# 16REG_2a.net
KiCad netlist of a schematic drawn in EAGLE
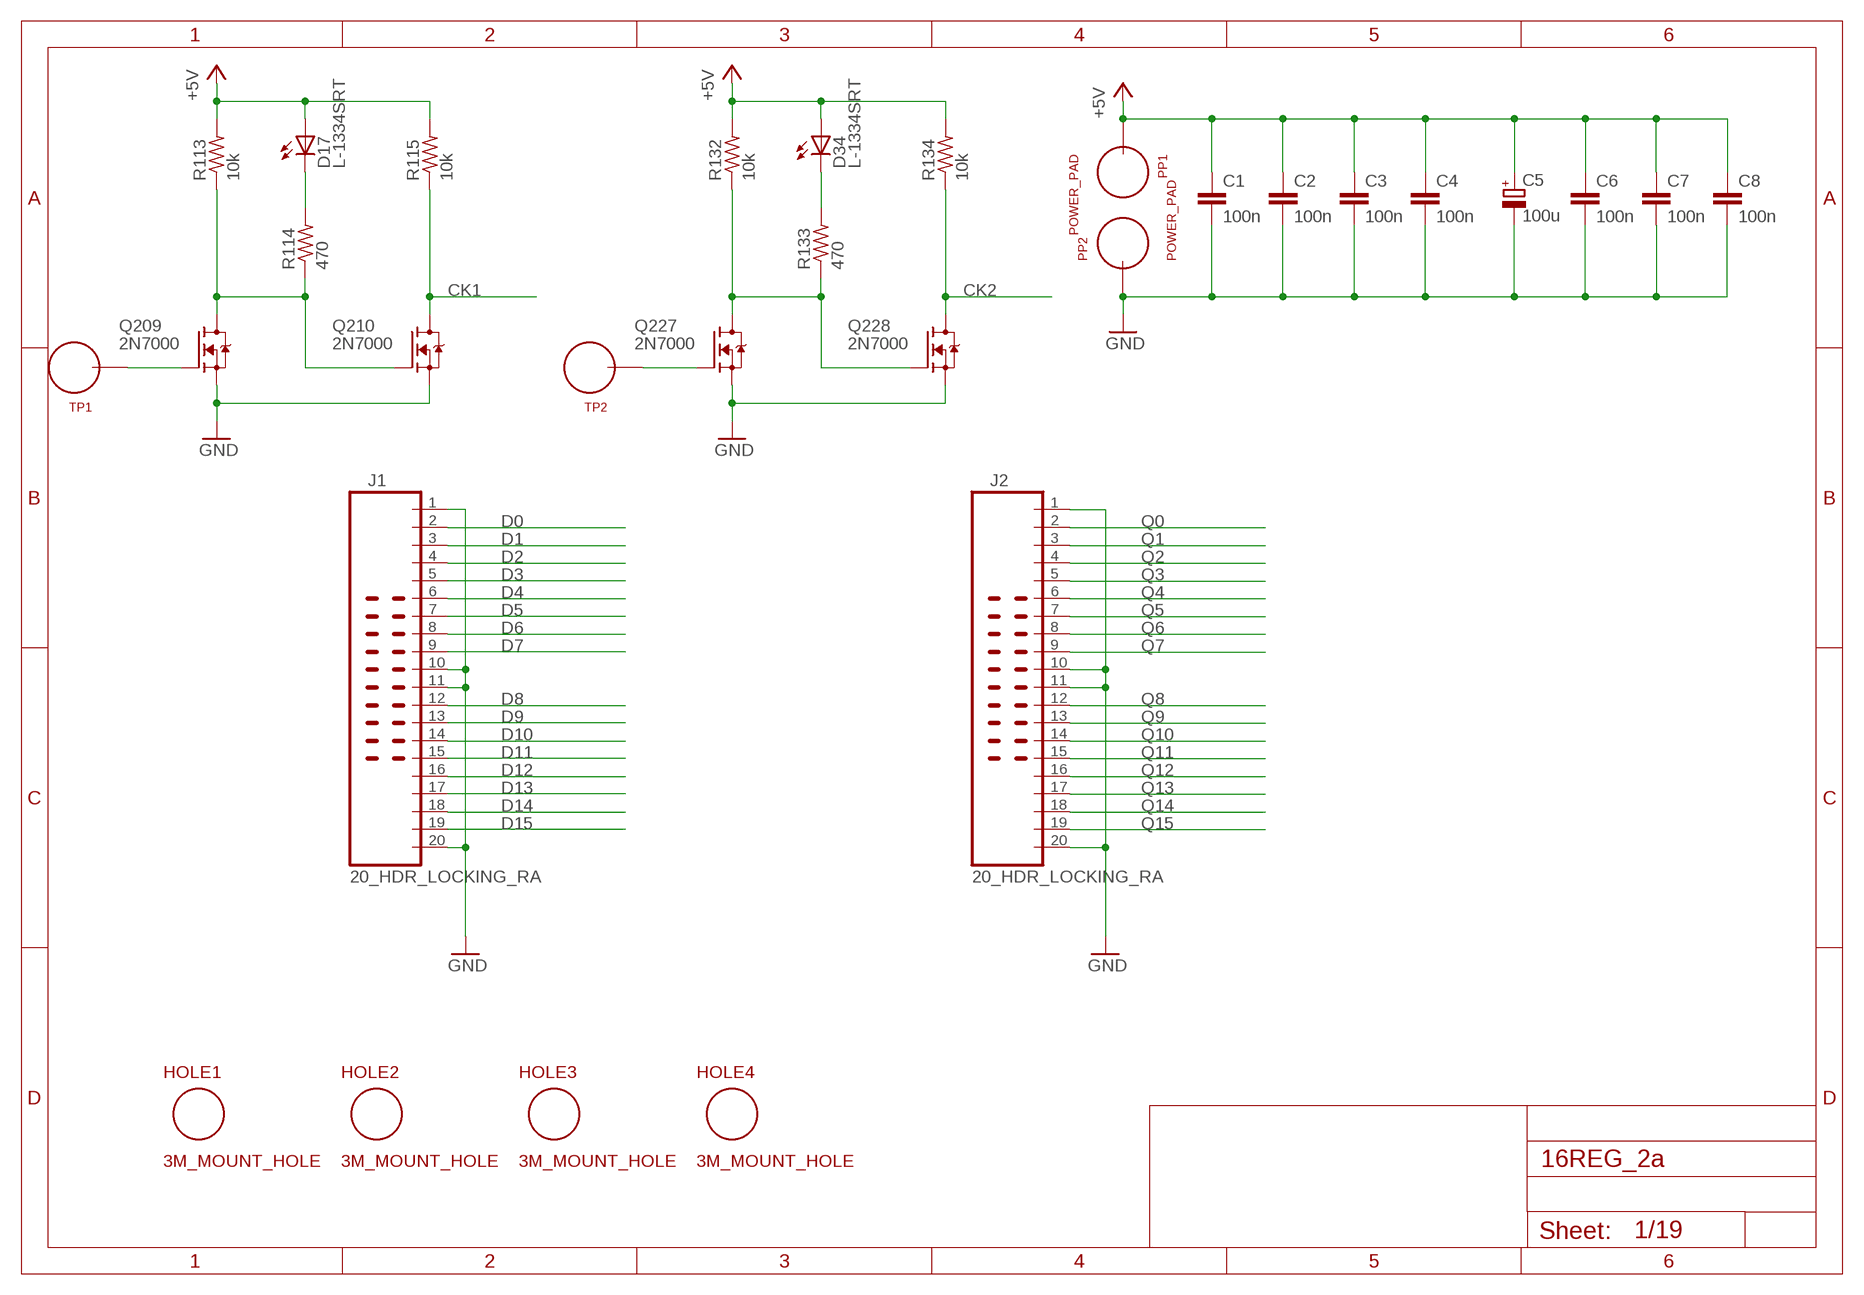
[diagram p0: schematic, sheet 1]
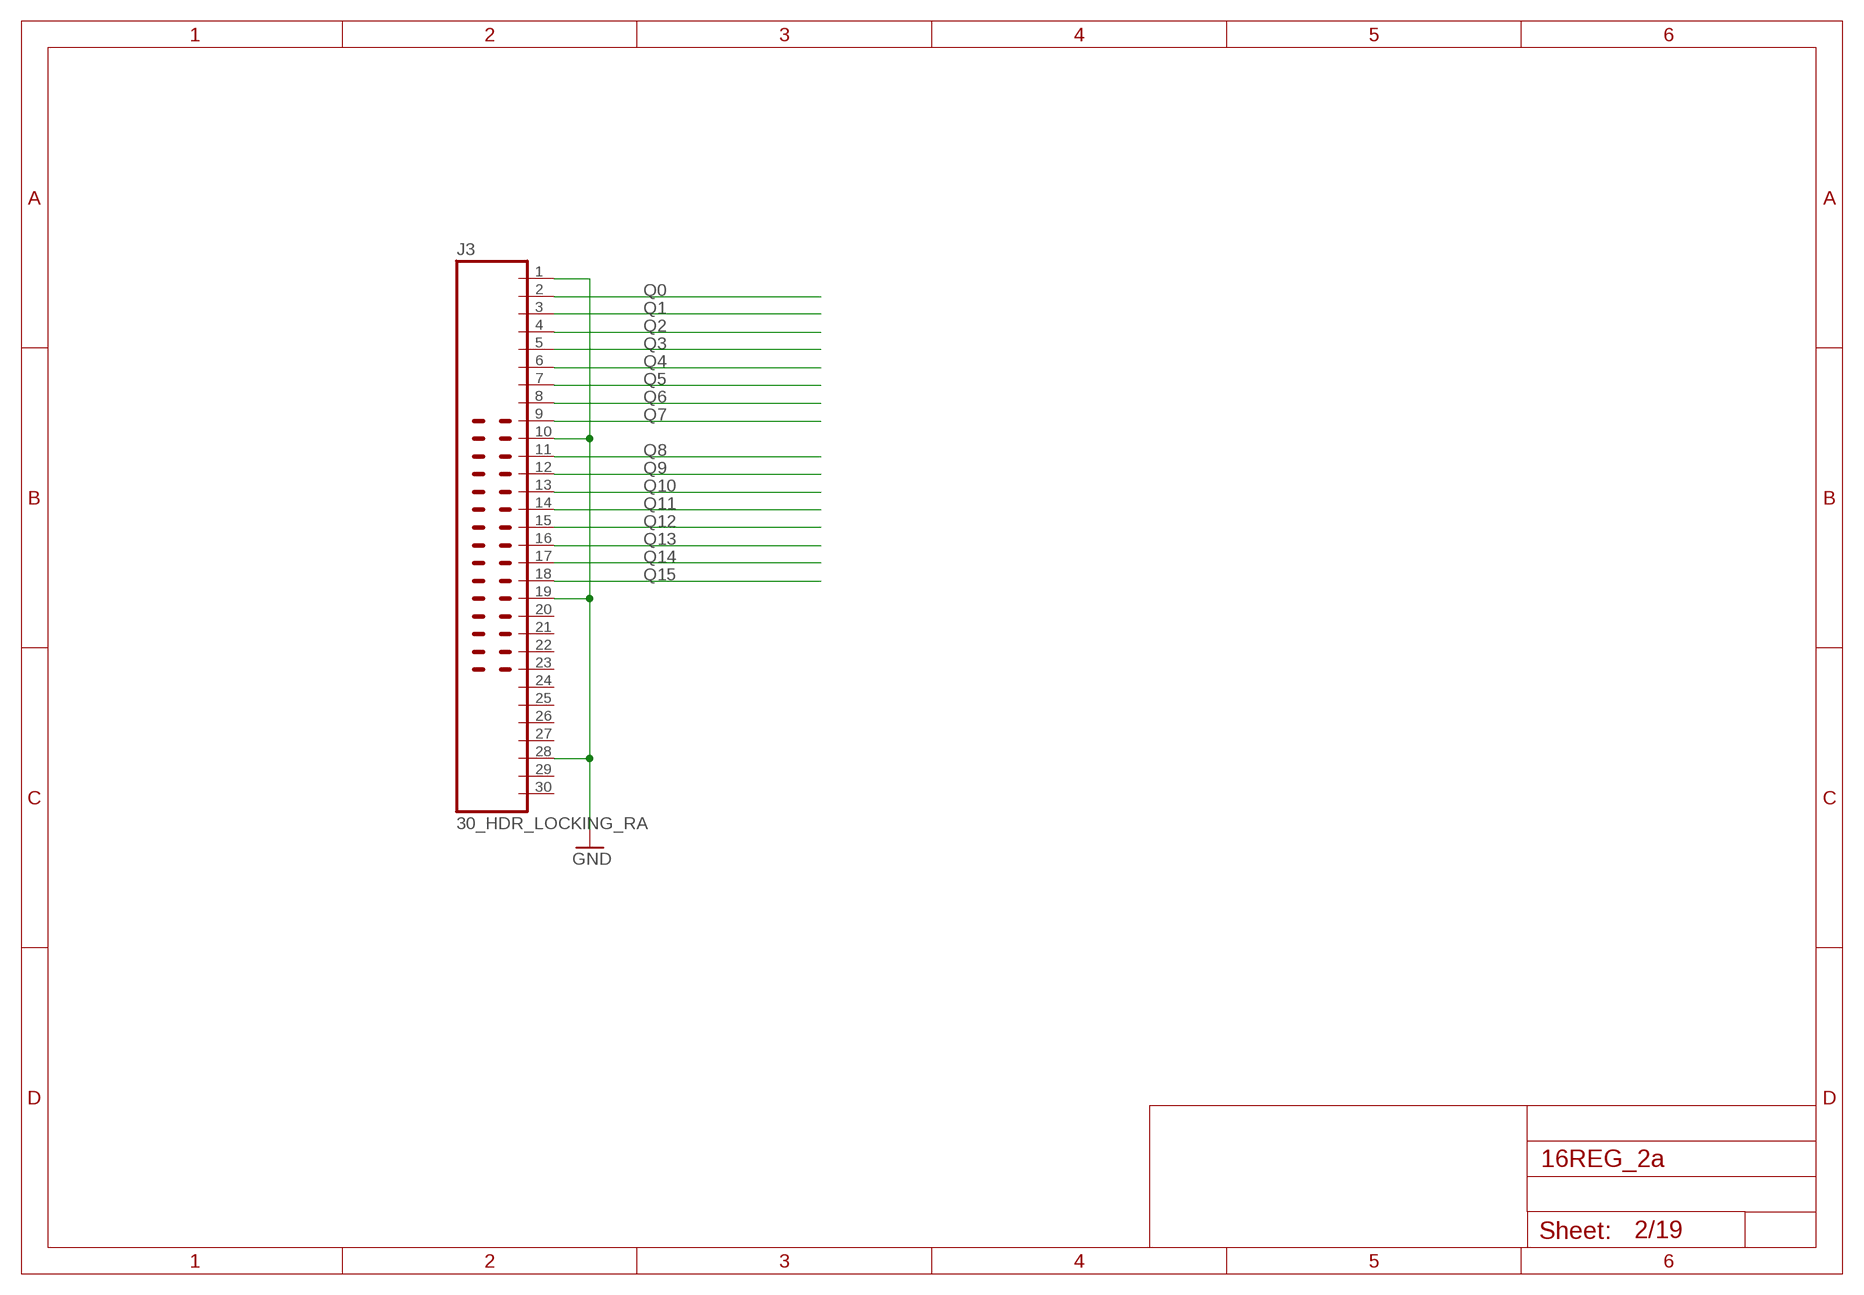
[diagram p1: schematic, sheet 2]
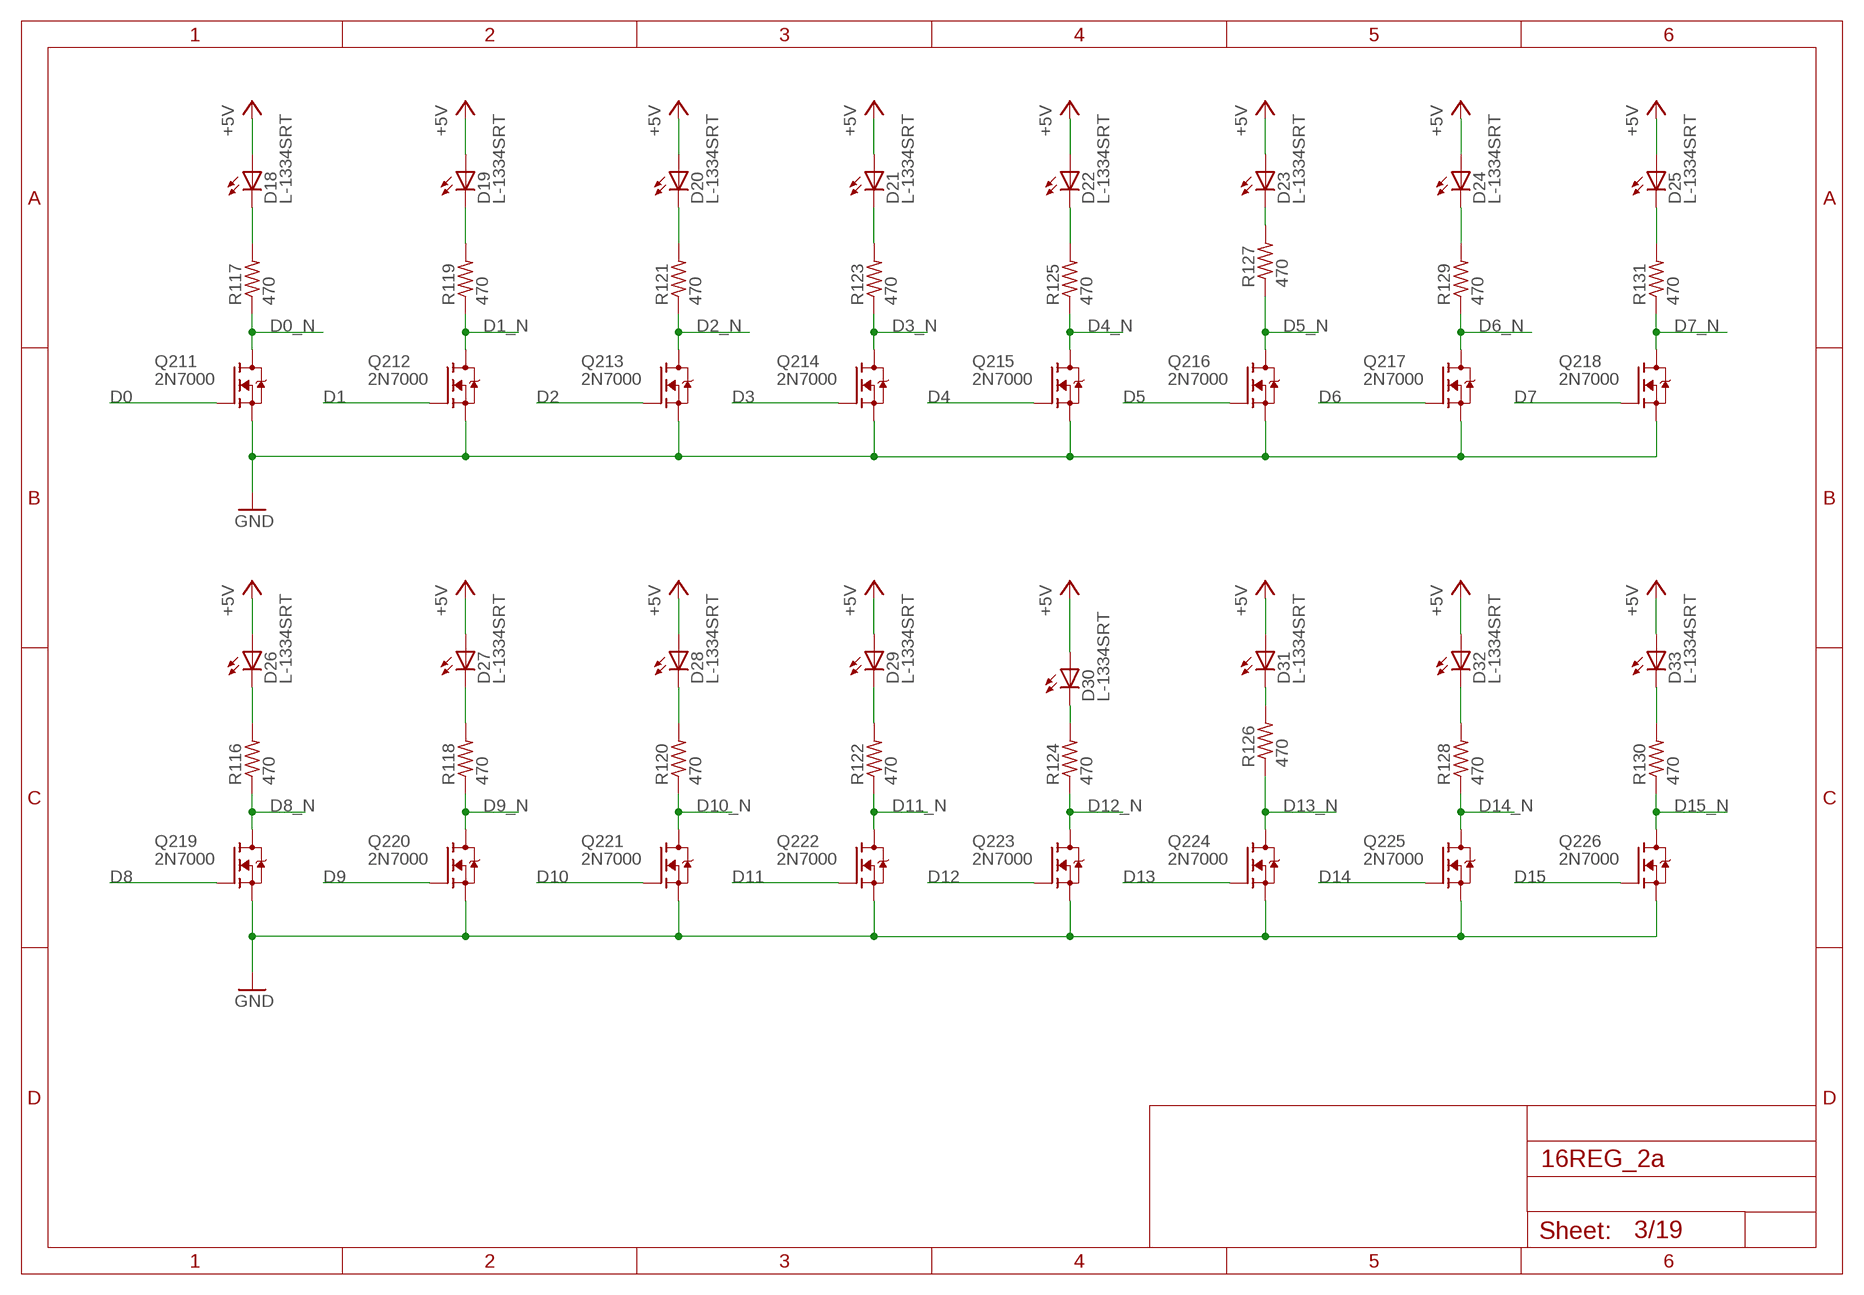
[diagram p2: schematic, sheet 3]
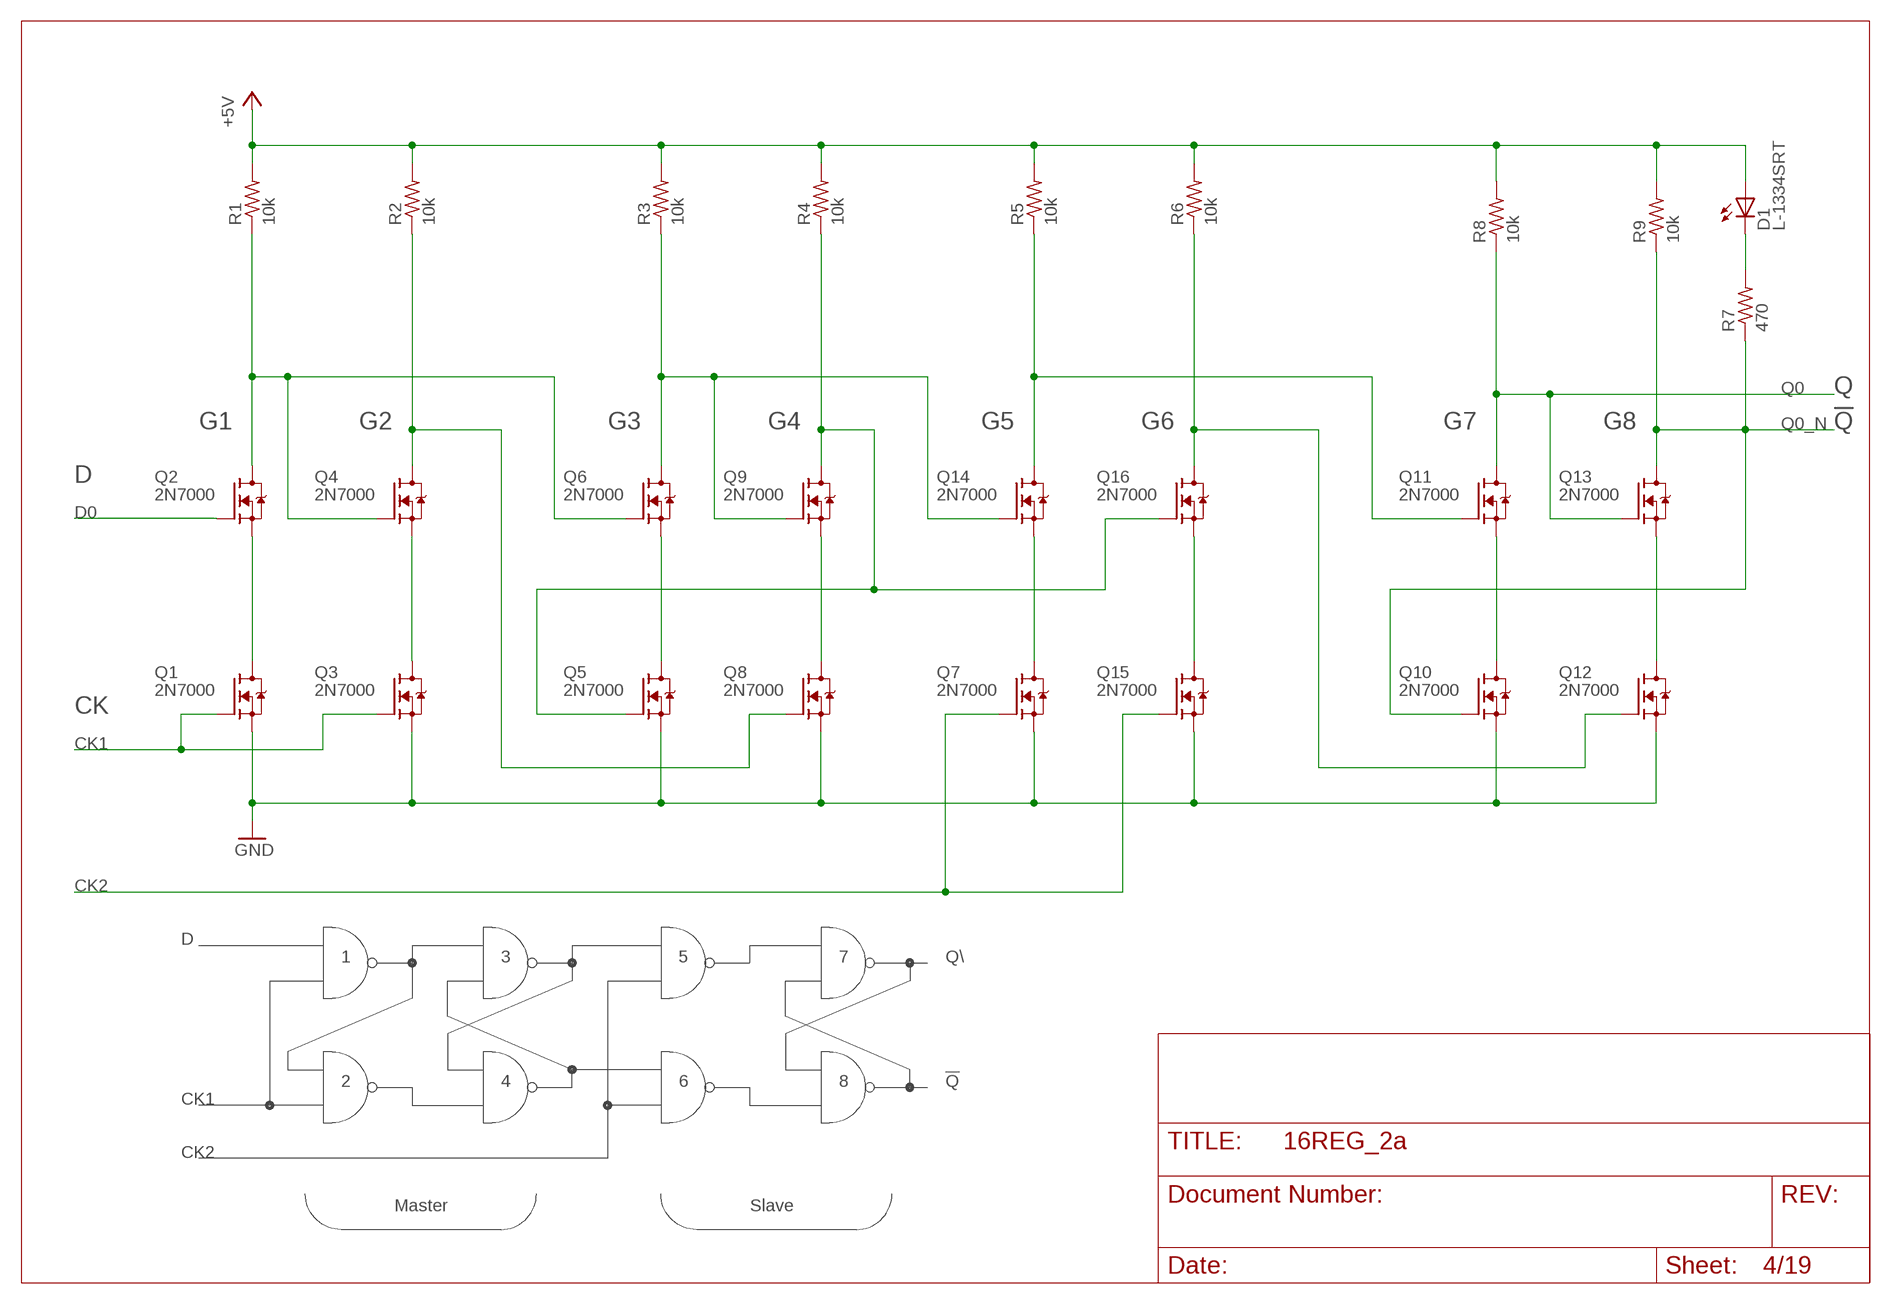
[diagram p3: schematic, sheet 4]
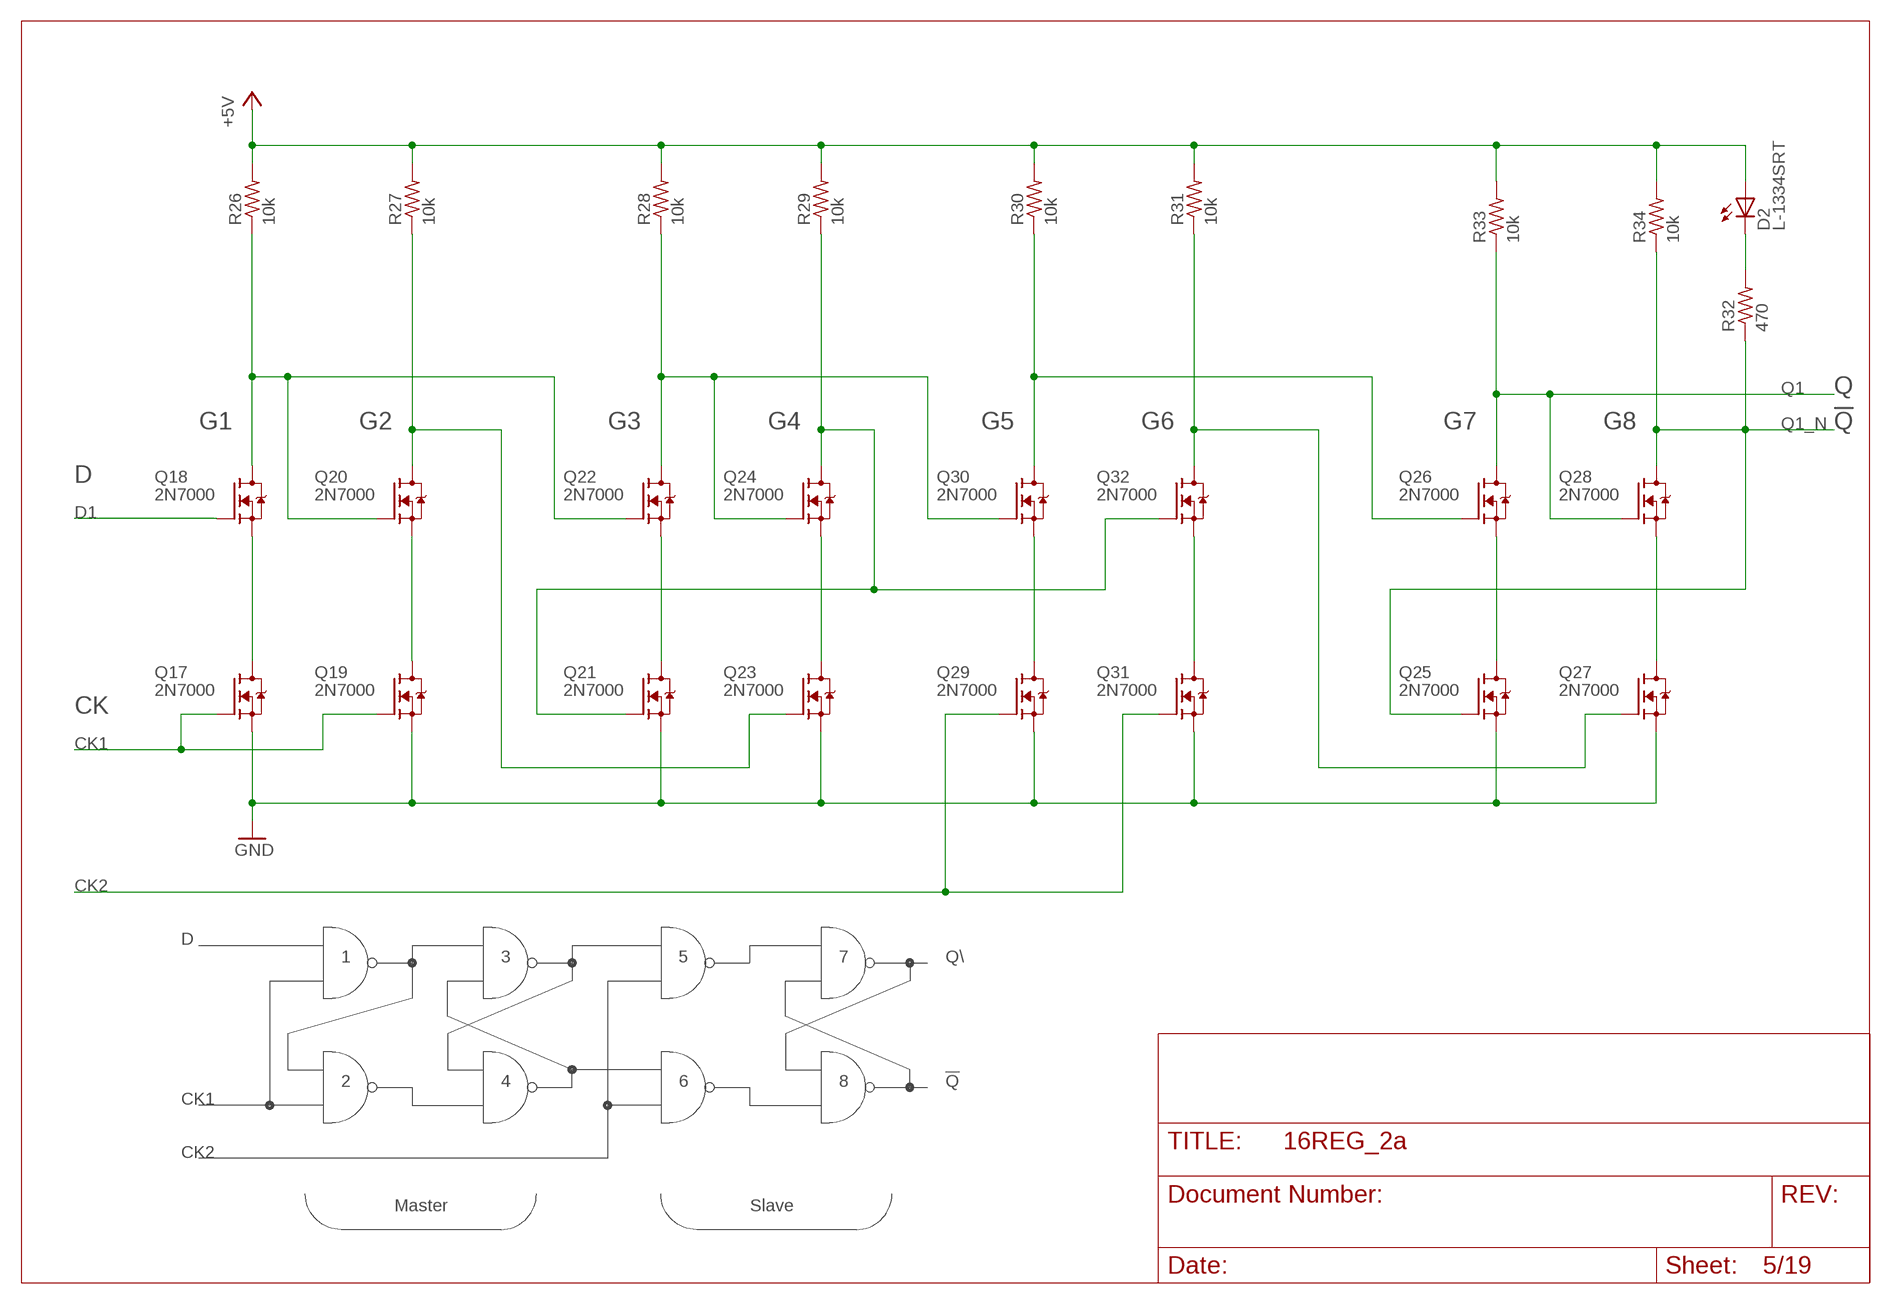
[diagram p4: schematic, sheet 5]
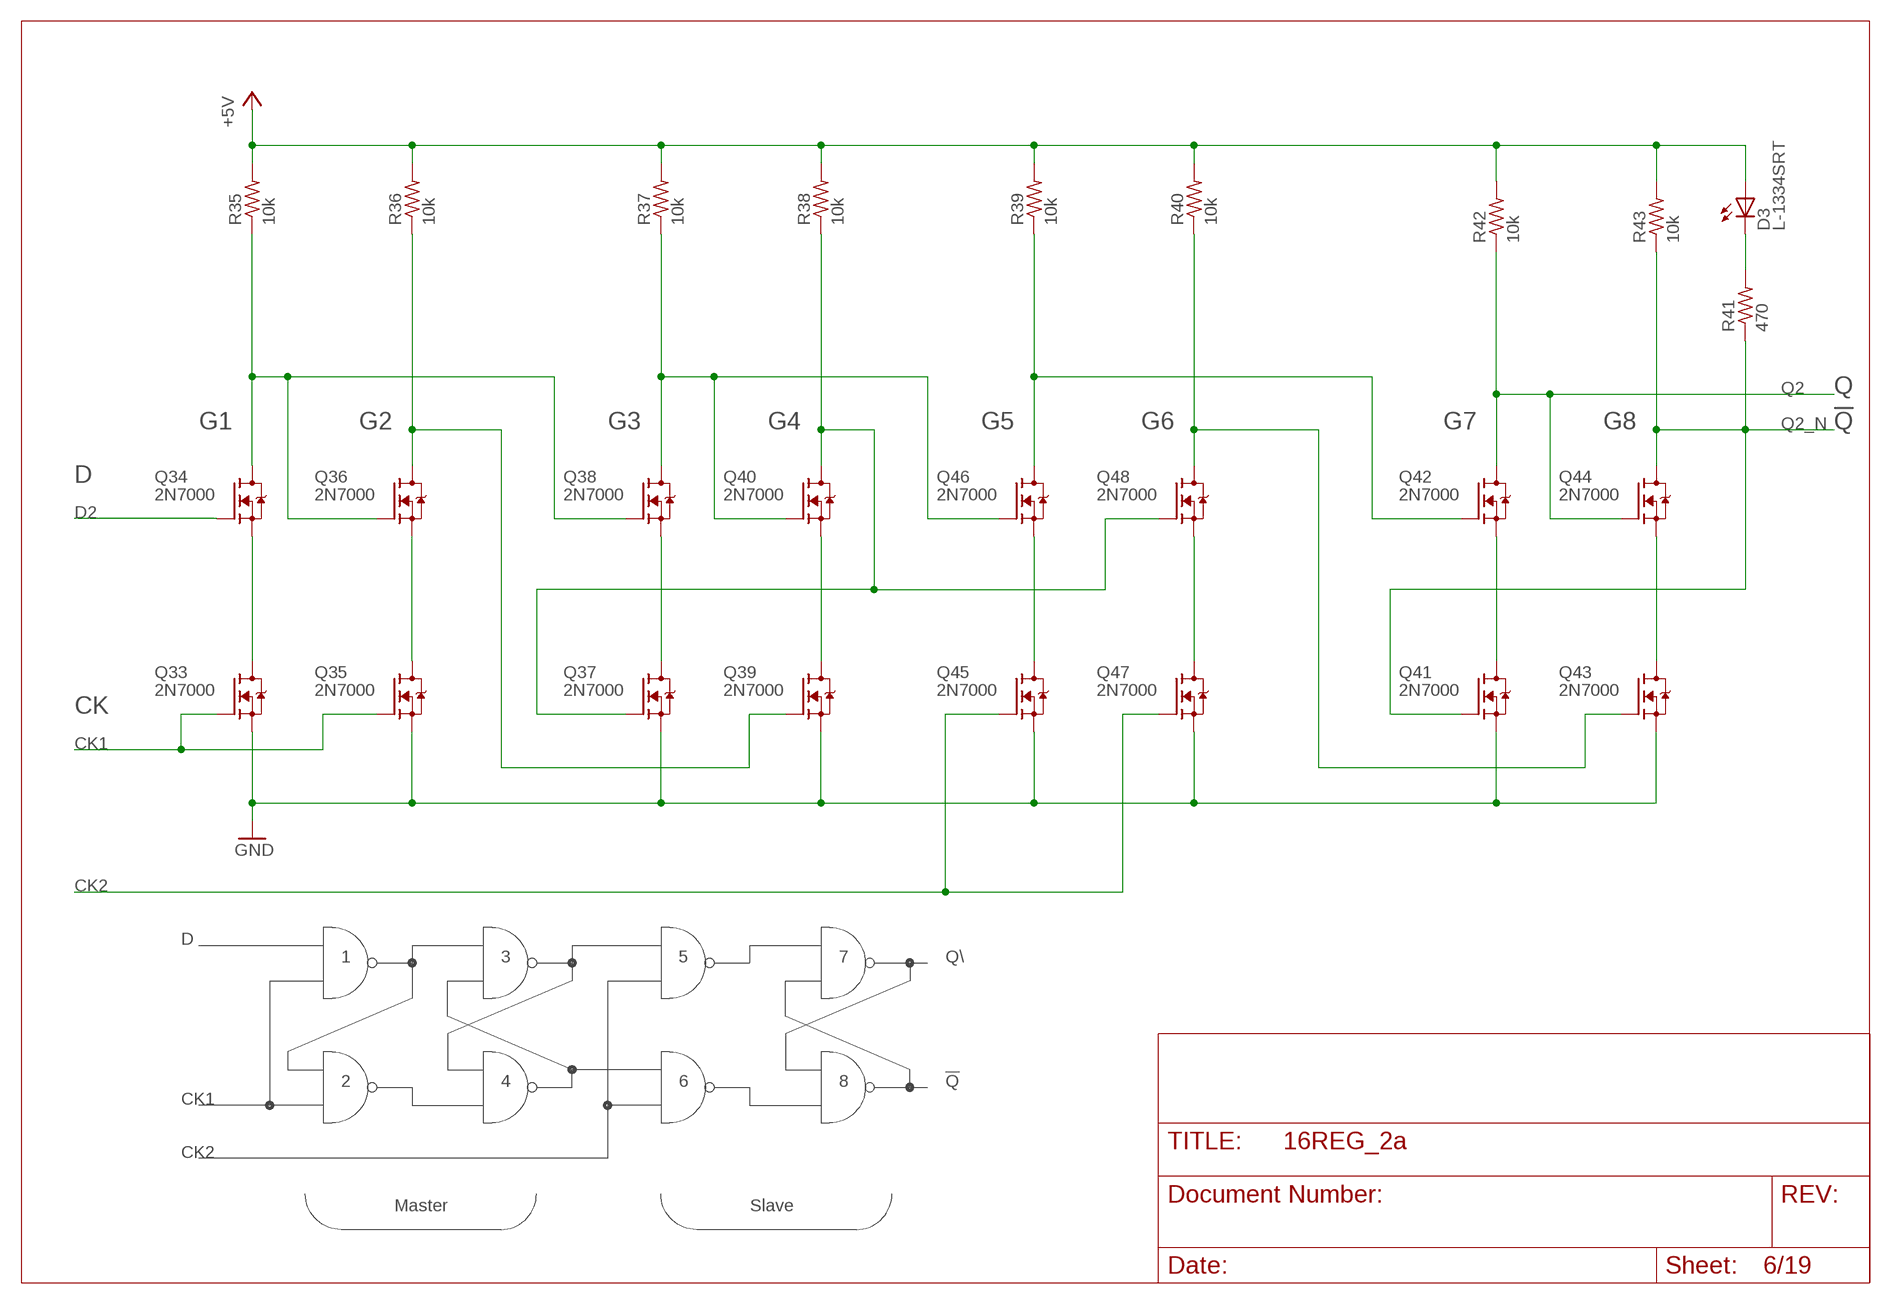
[diagram p5: schematic, sheet 6]
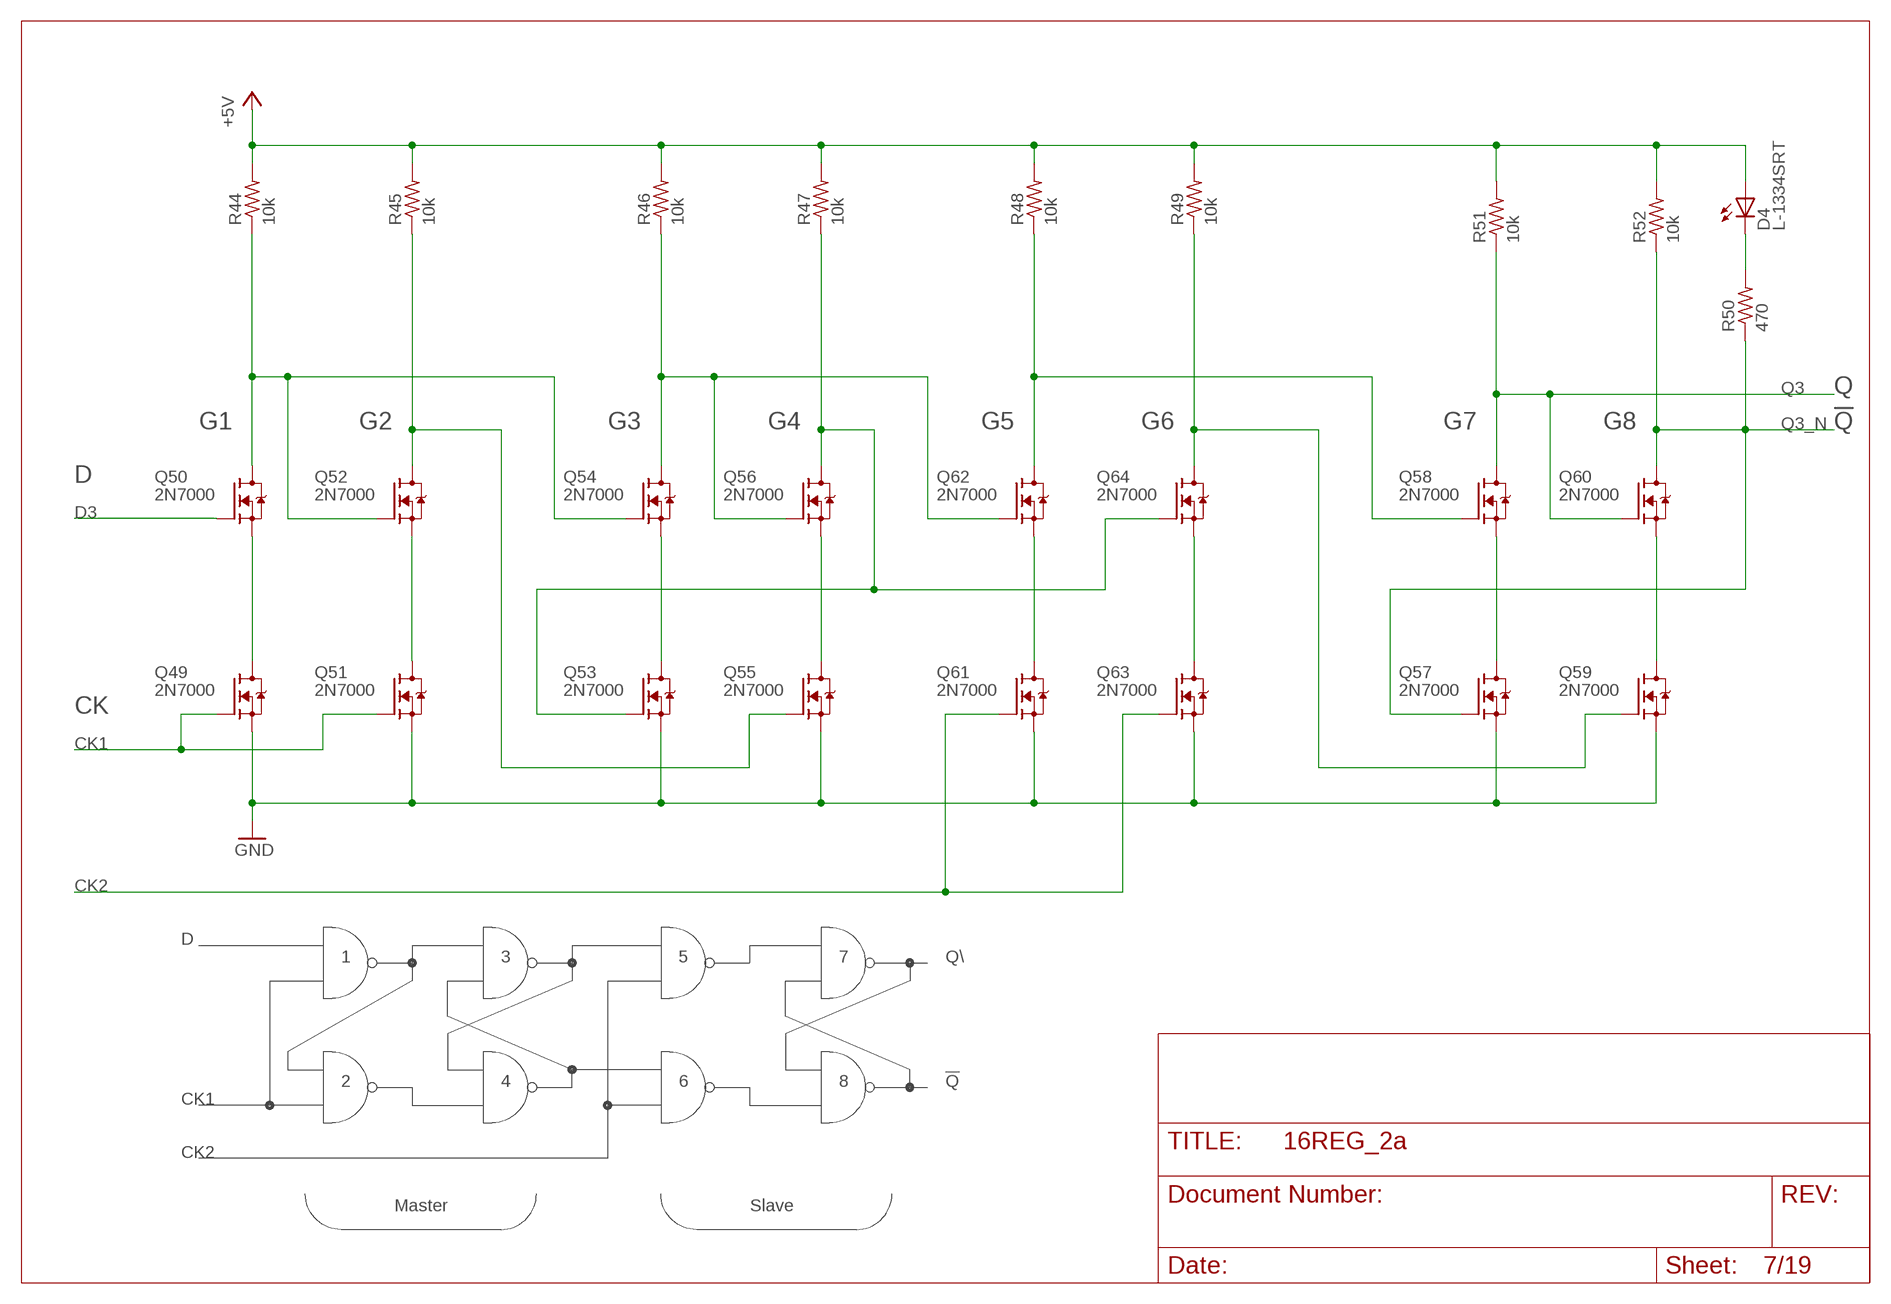
[diagram p6: schematic, sheet 7]
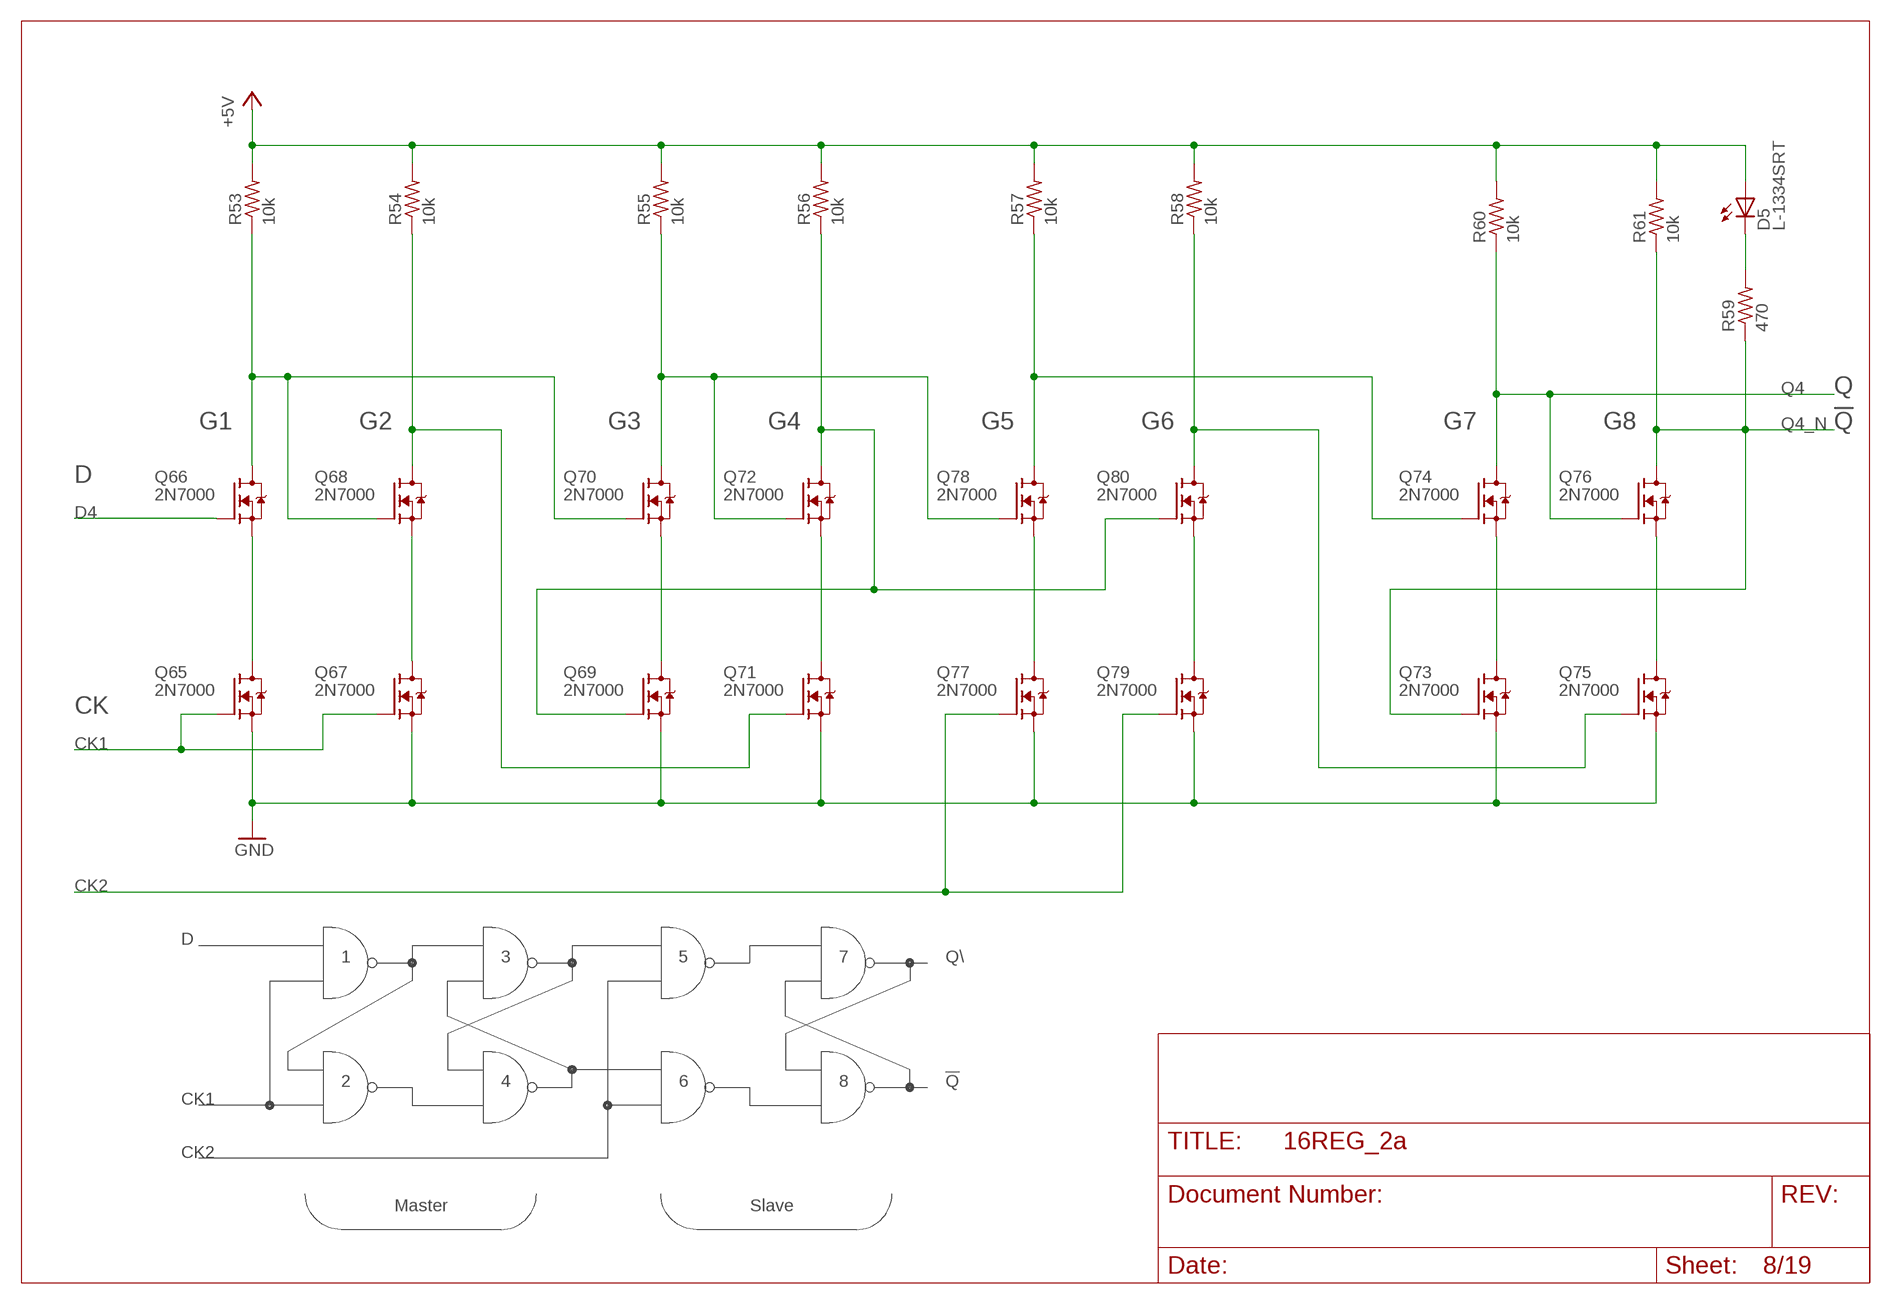
[diagram p7: schematic, sheet 8]
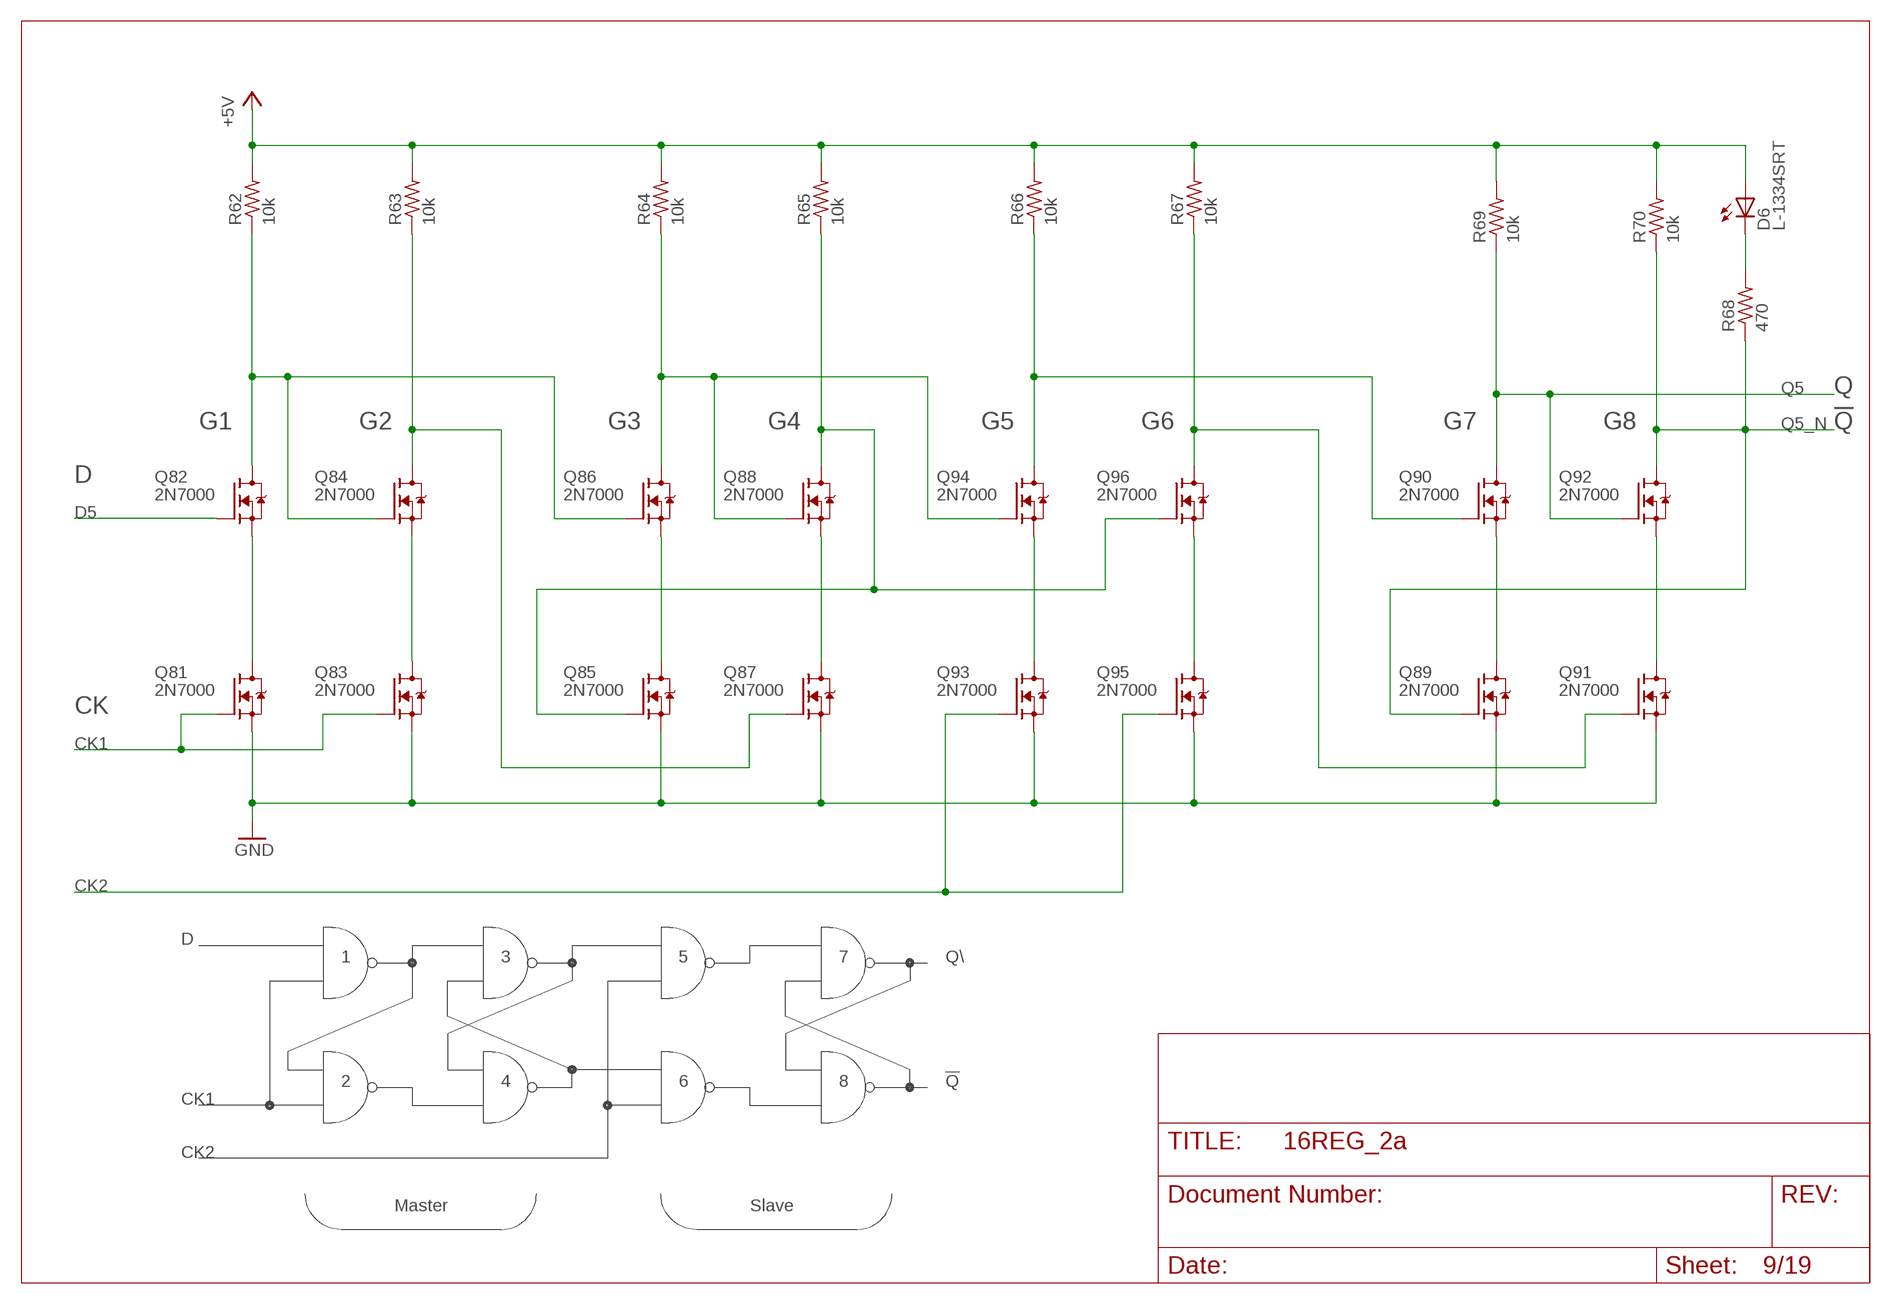
[diagram p8: schematic, sheet 9]
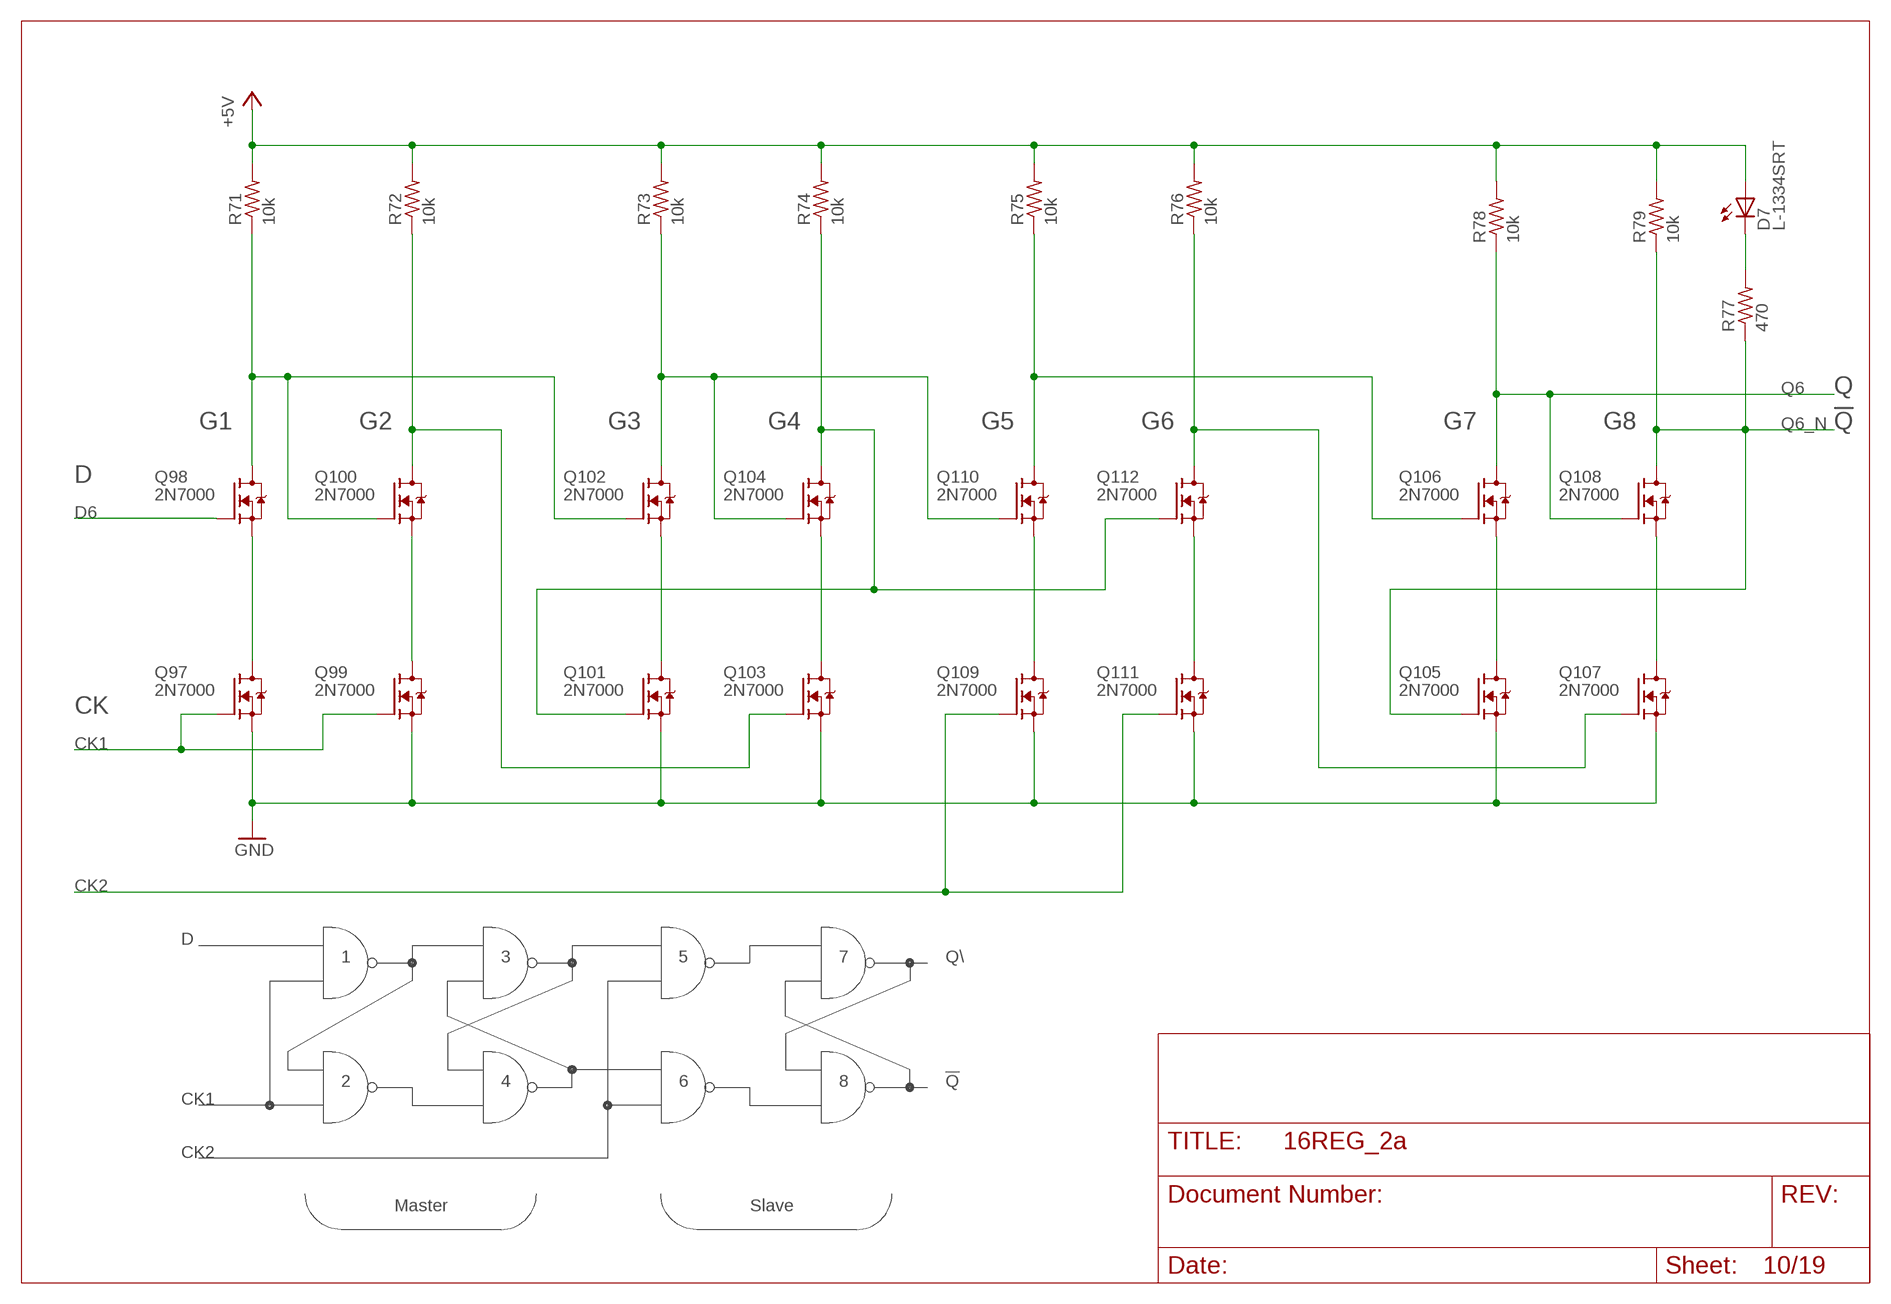
[diagram p9: schematic, sheet 10]
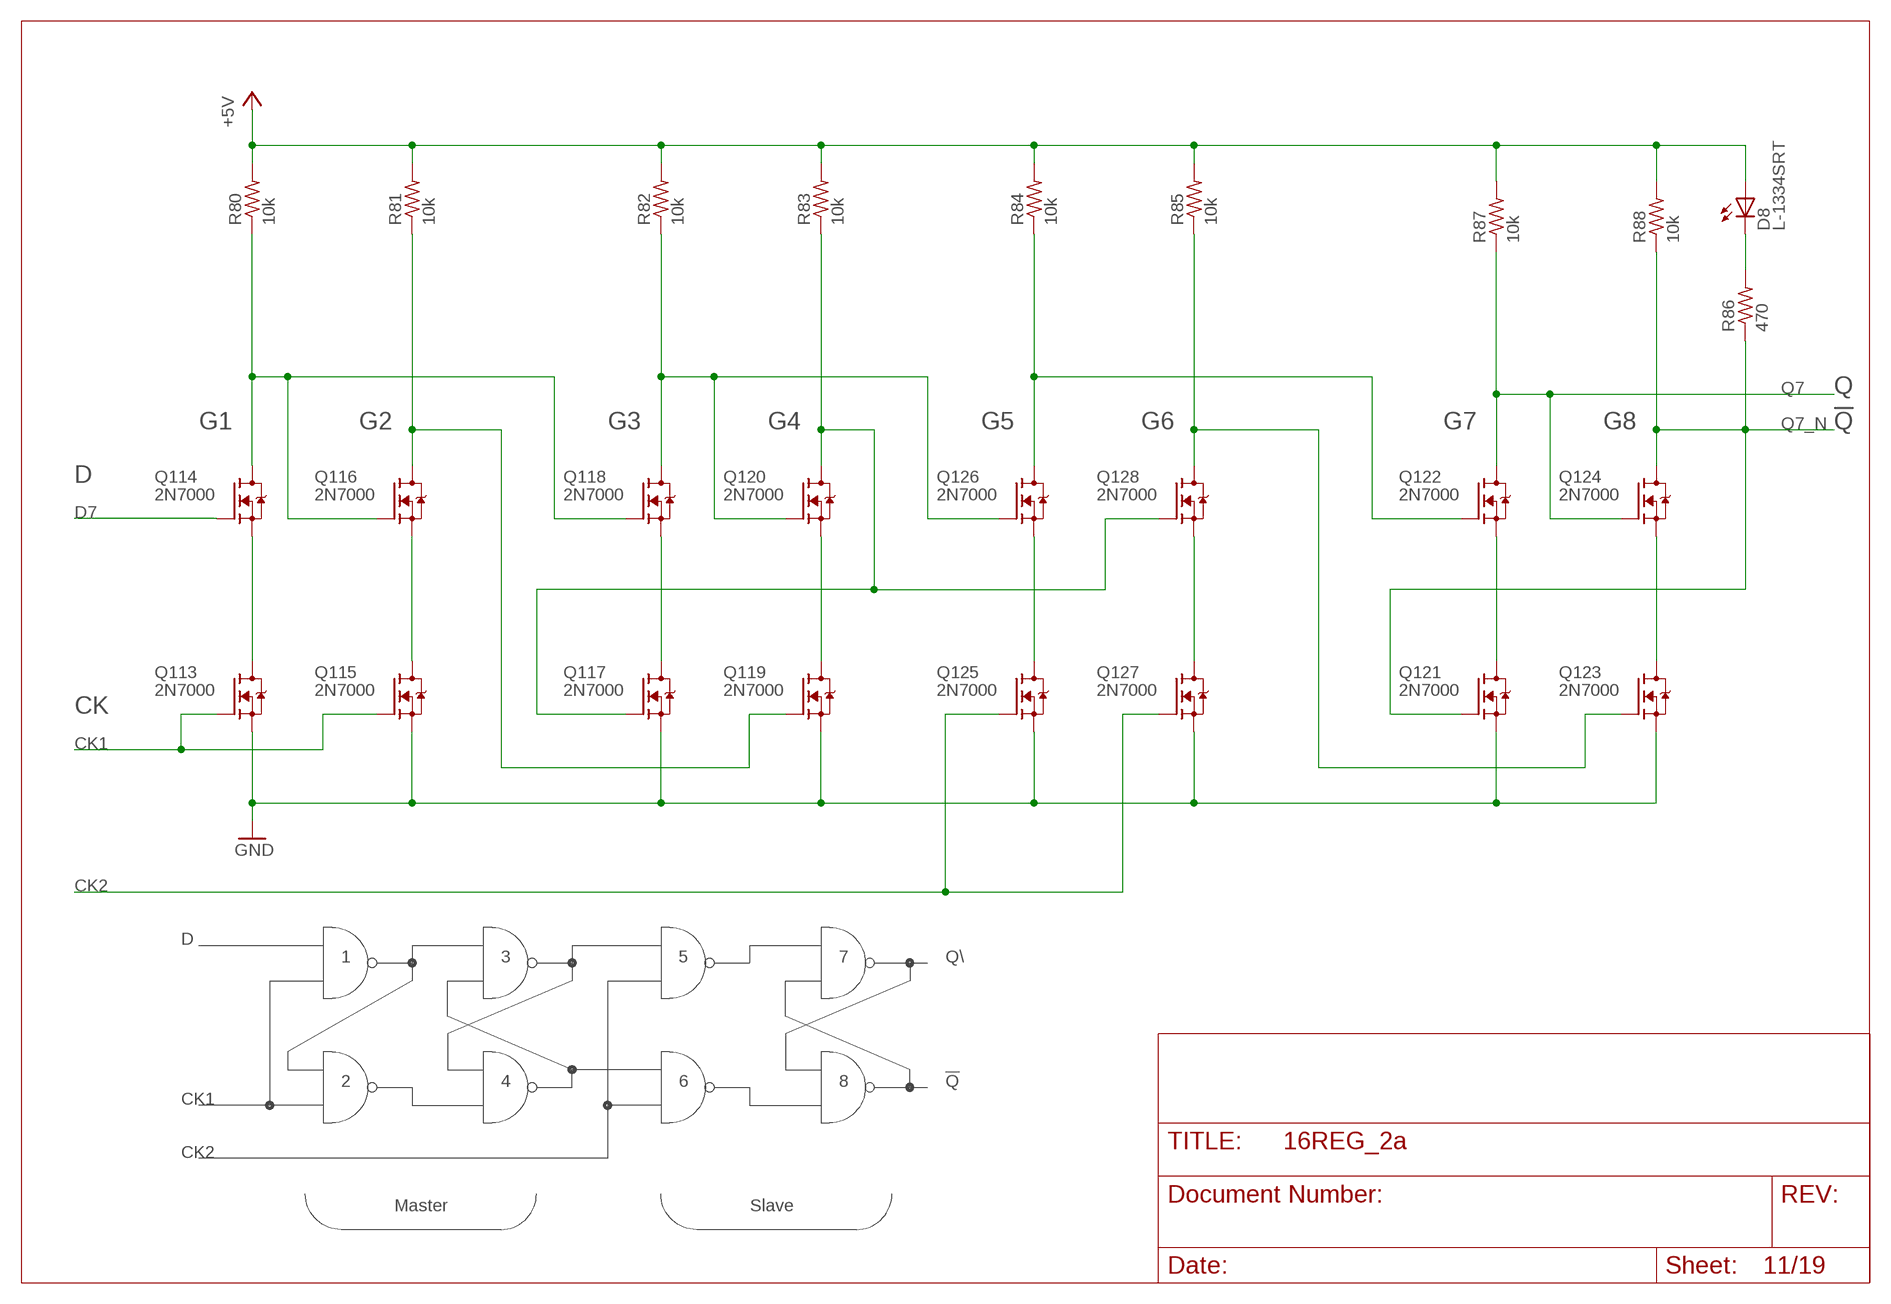
[diagram p10: schematic, sheet 11]
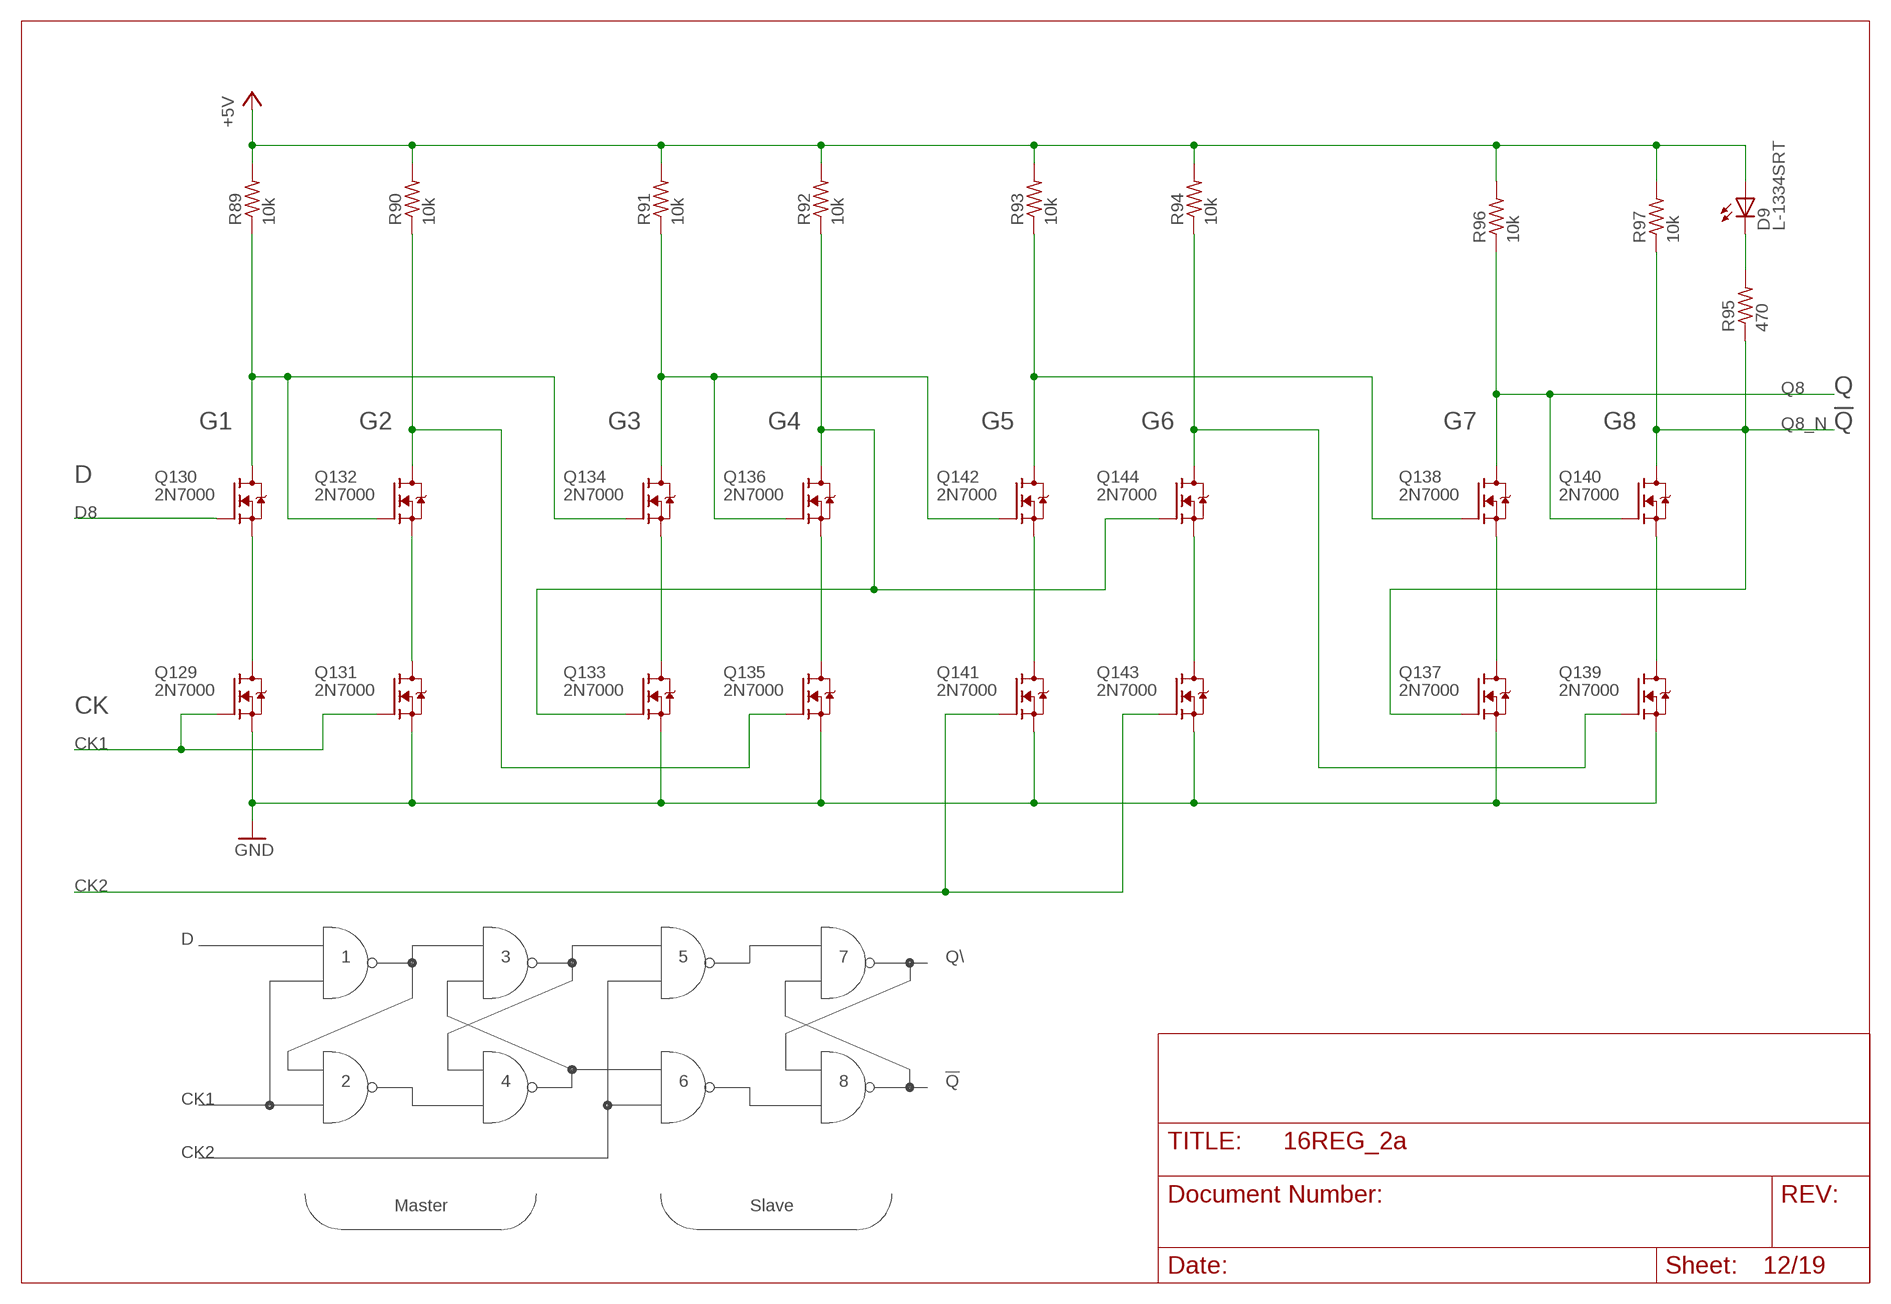
[diagram p11: schematic, sheet 12]
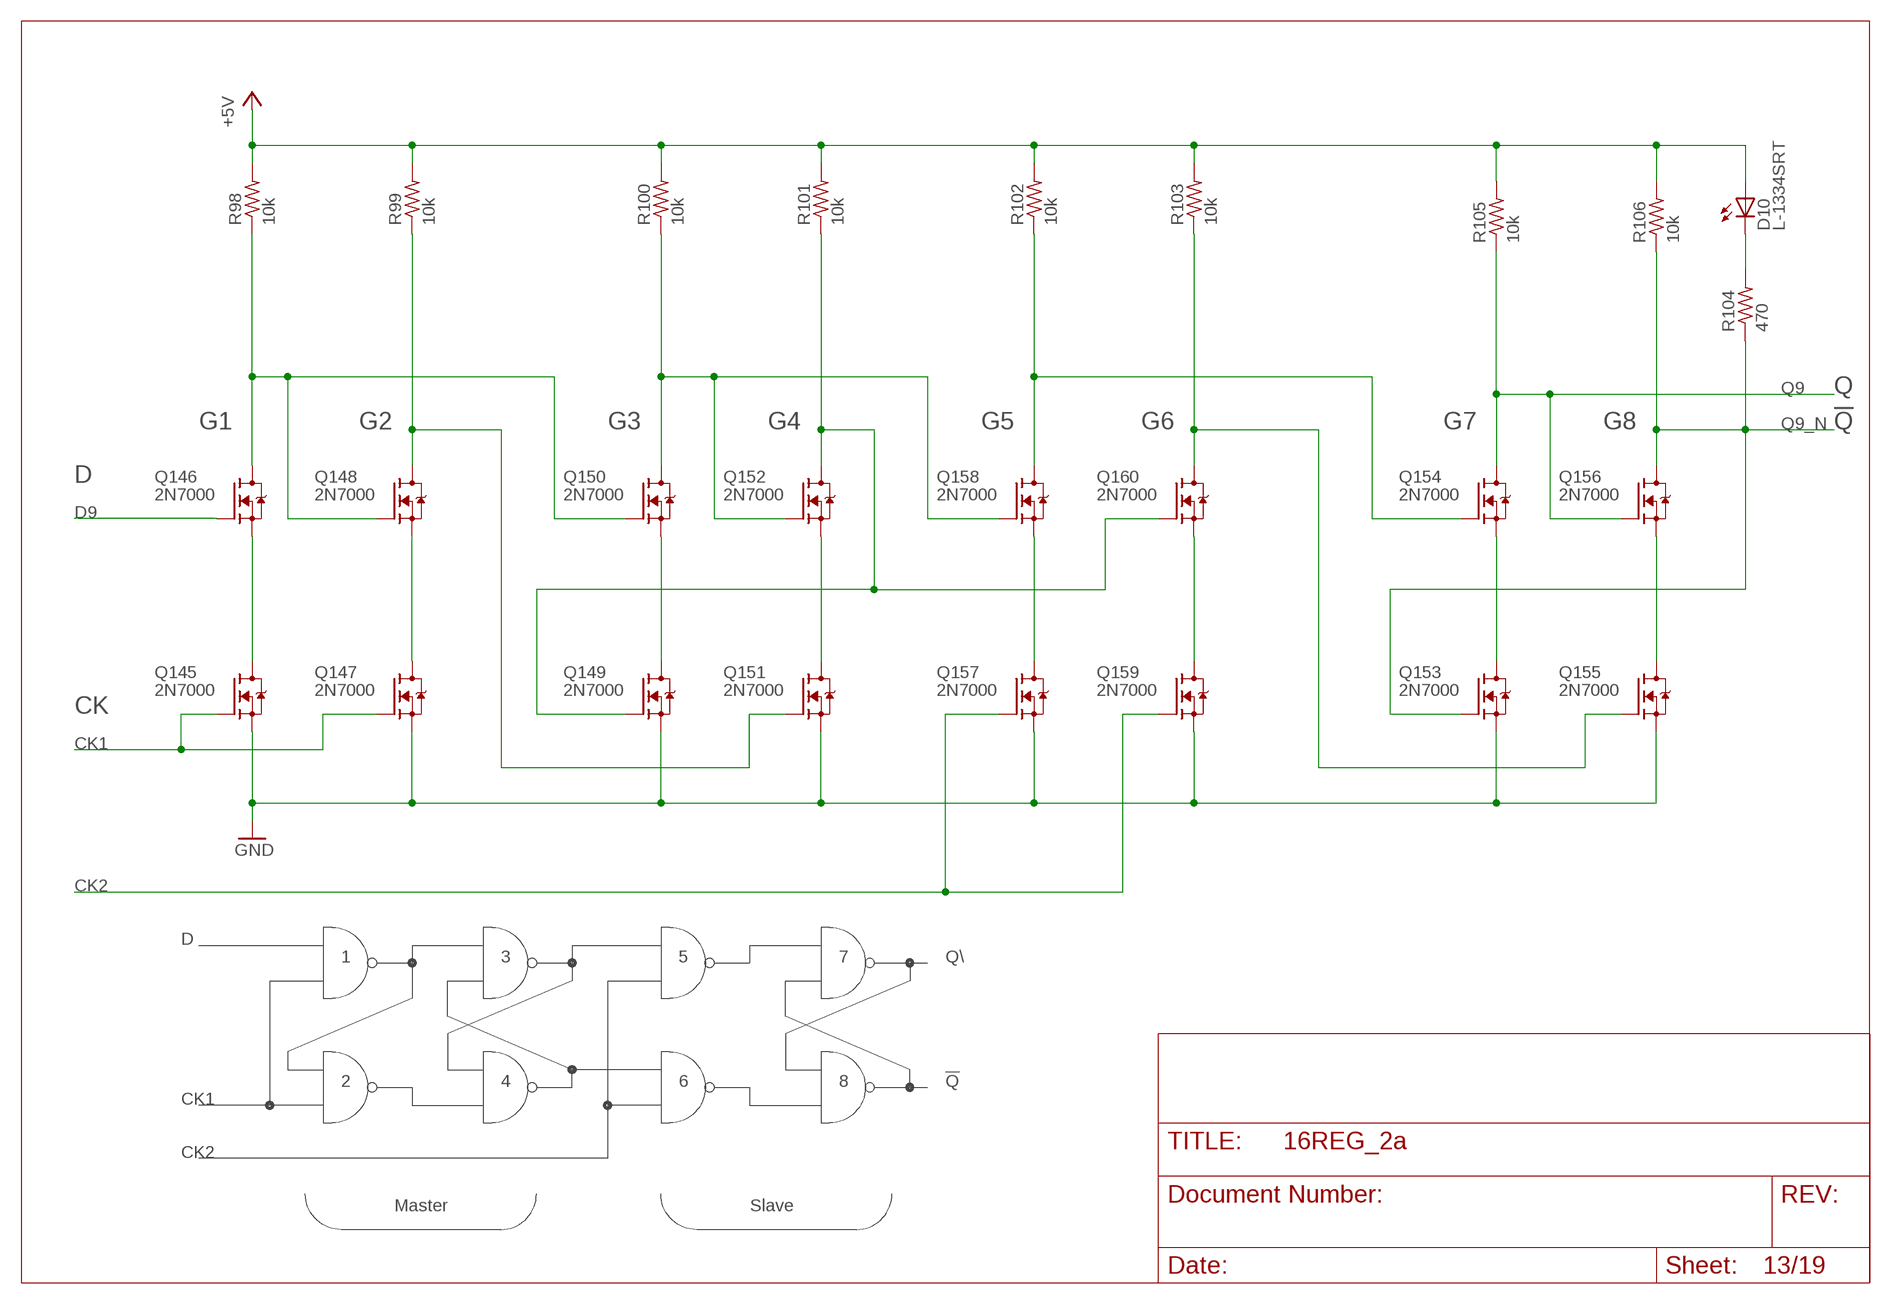
[diagram p12: schematic, sheet 13]
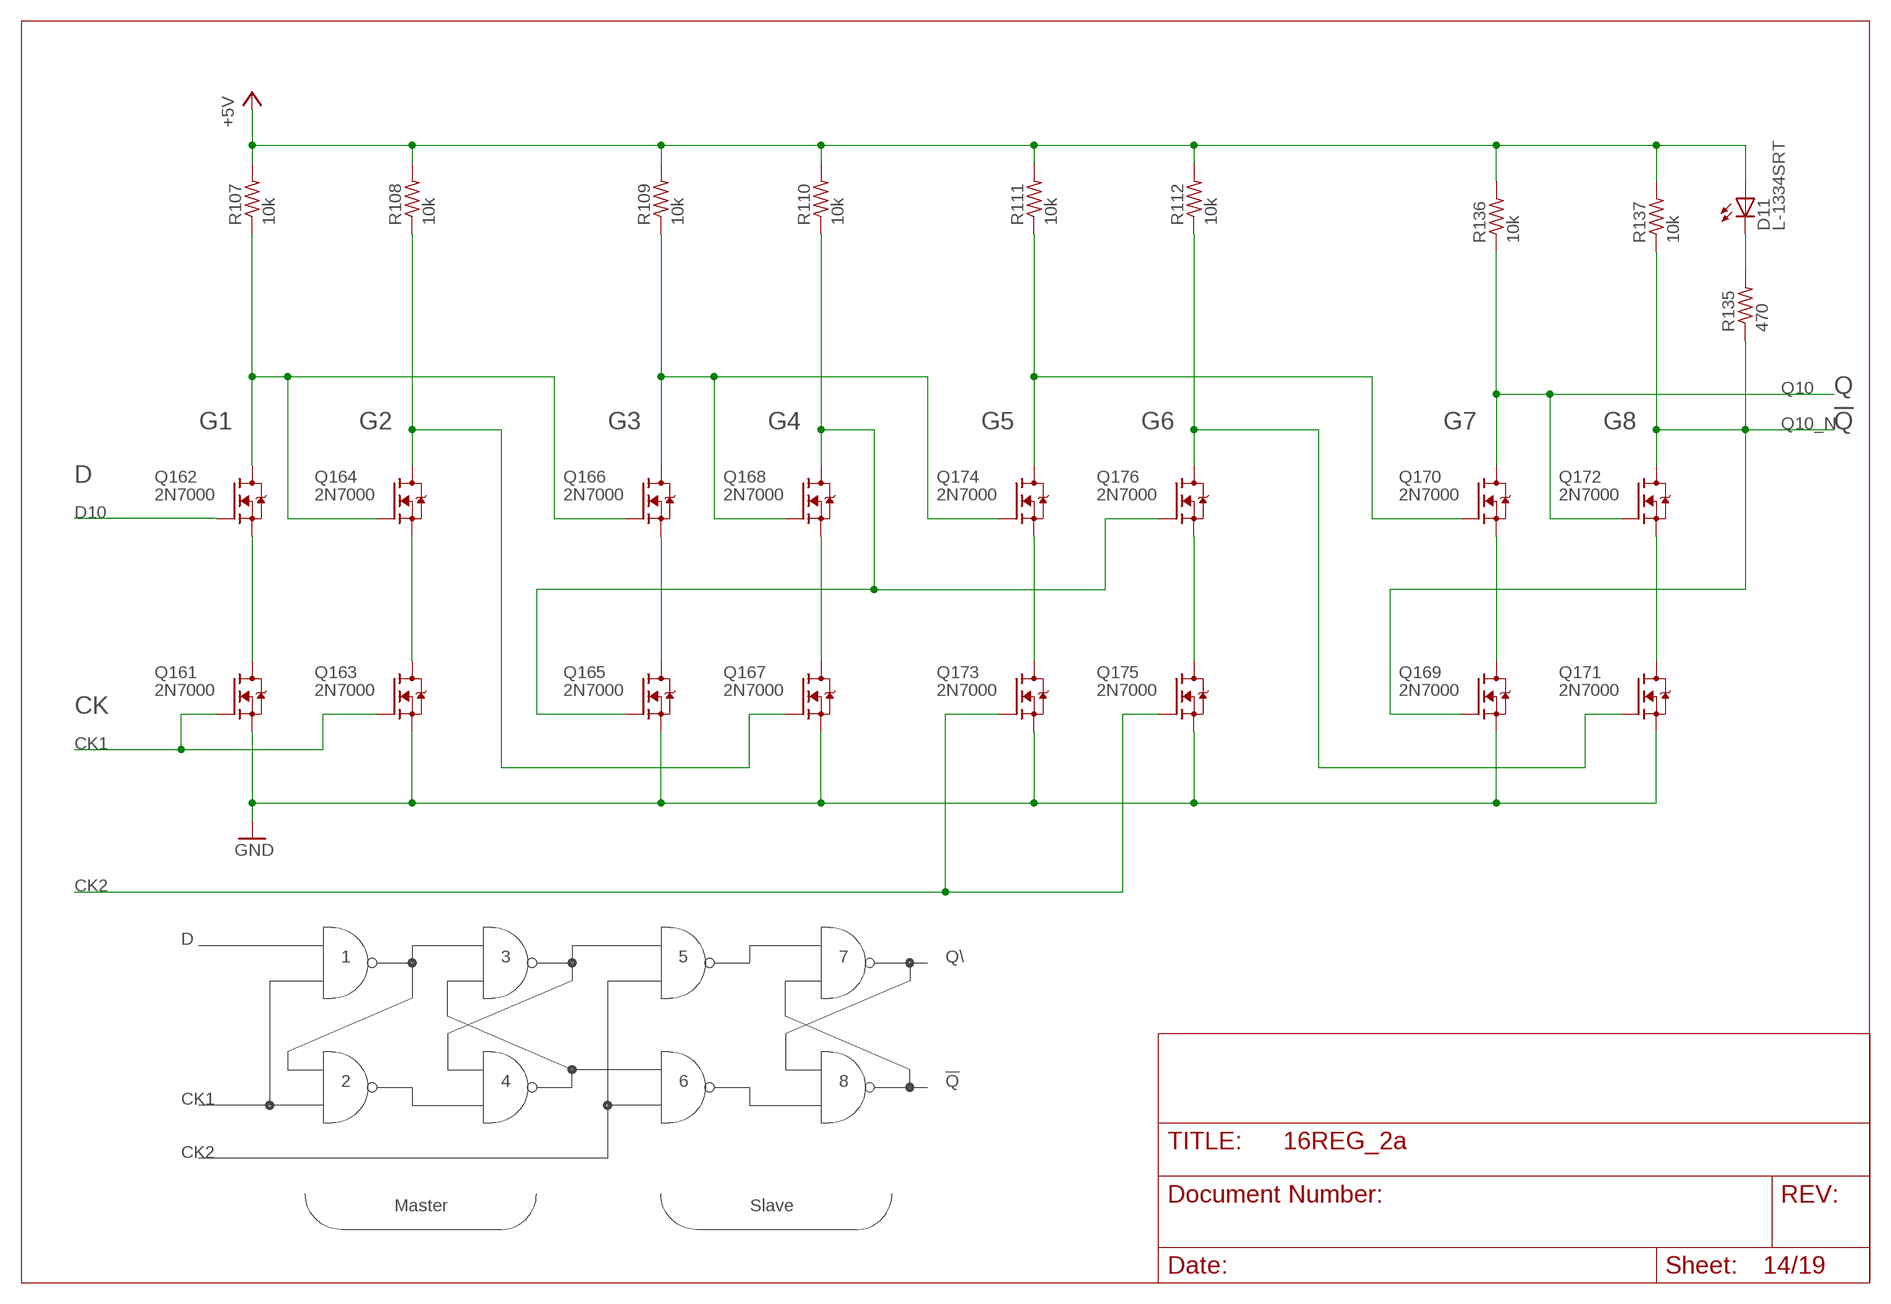
[diagram p13: schematic, sheet 14]
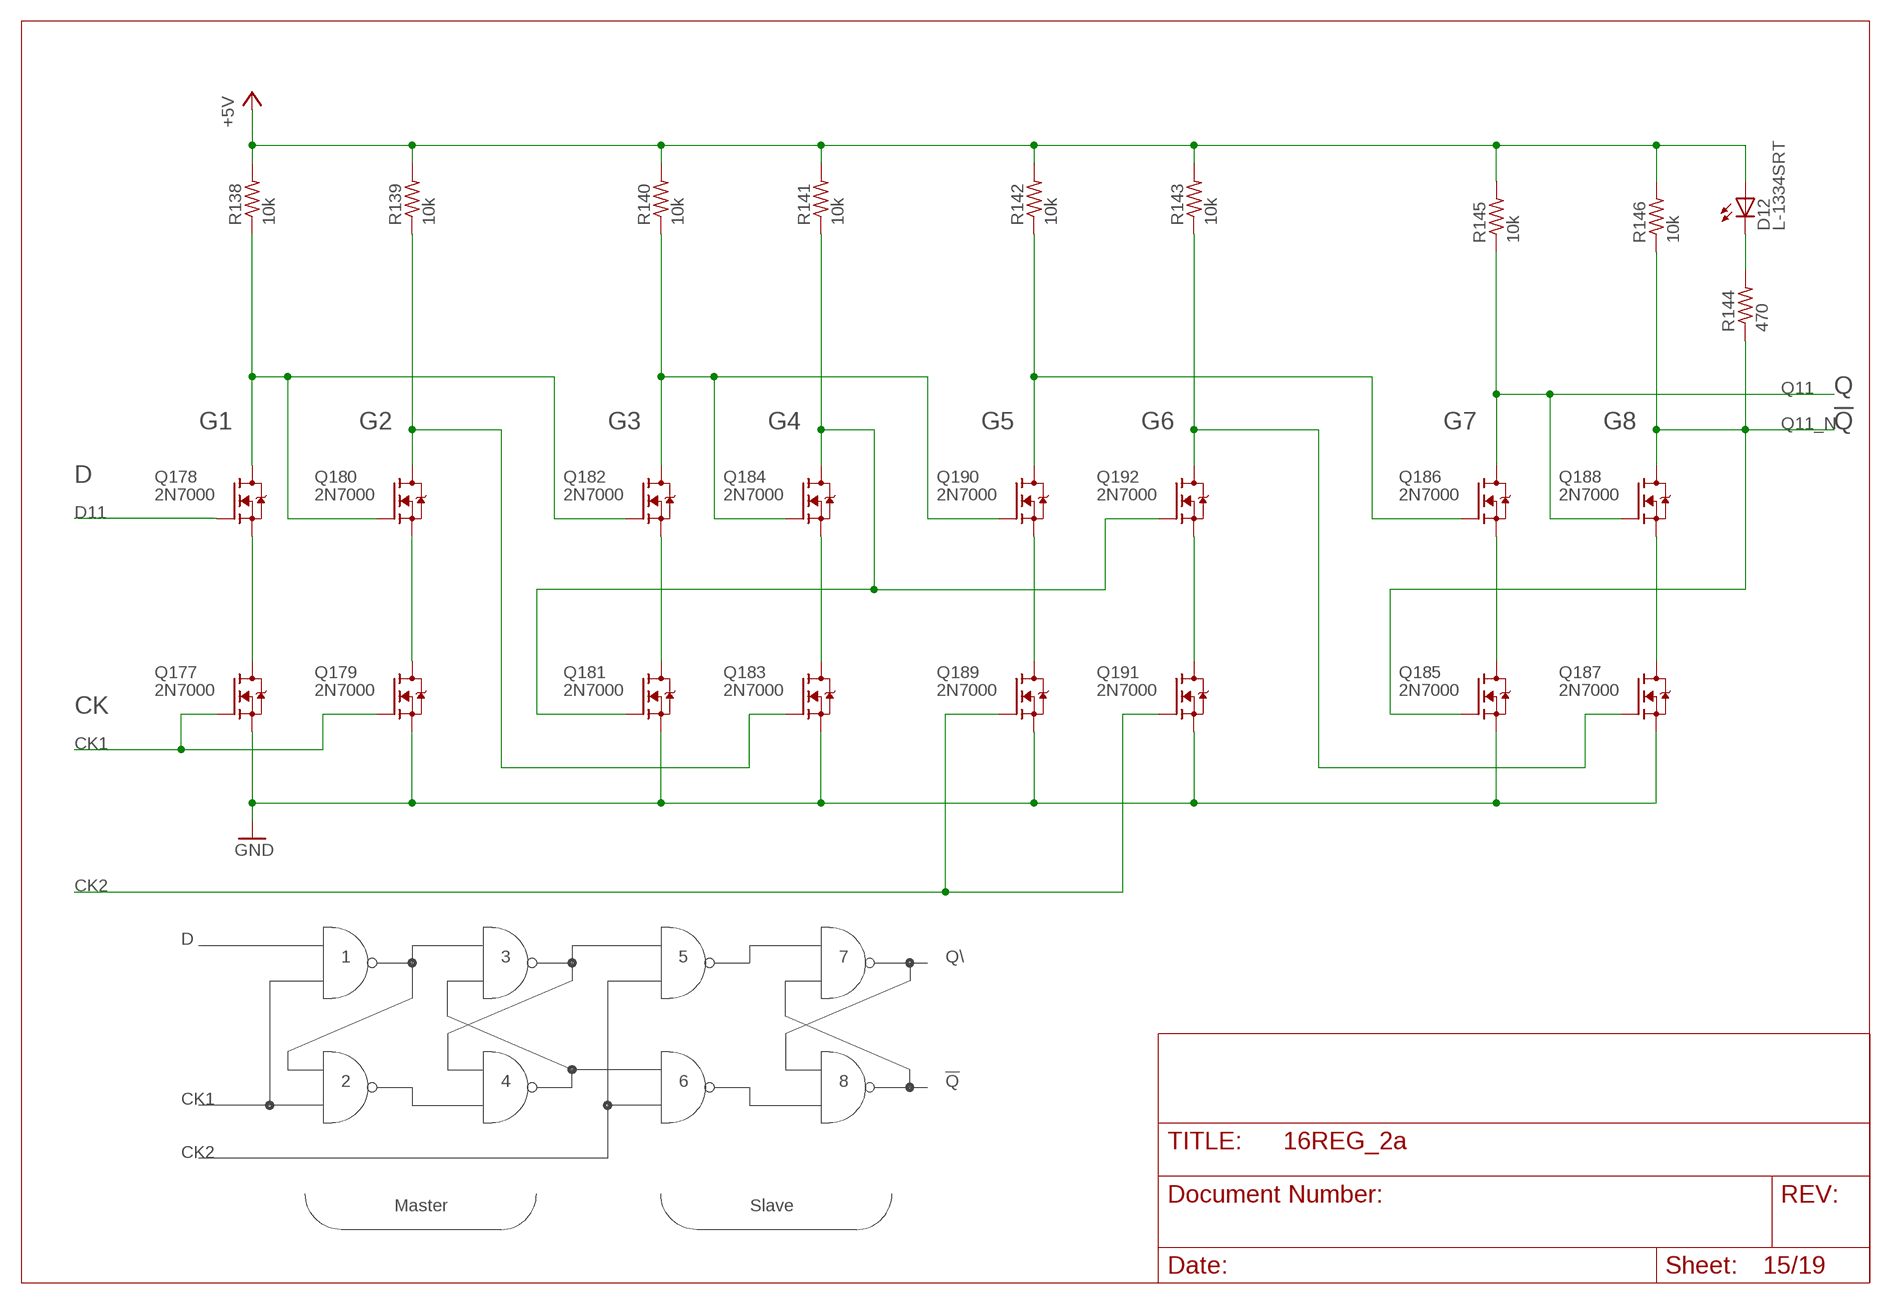
[diagram p14: schematic, sheet 15]
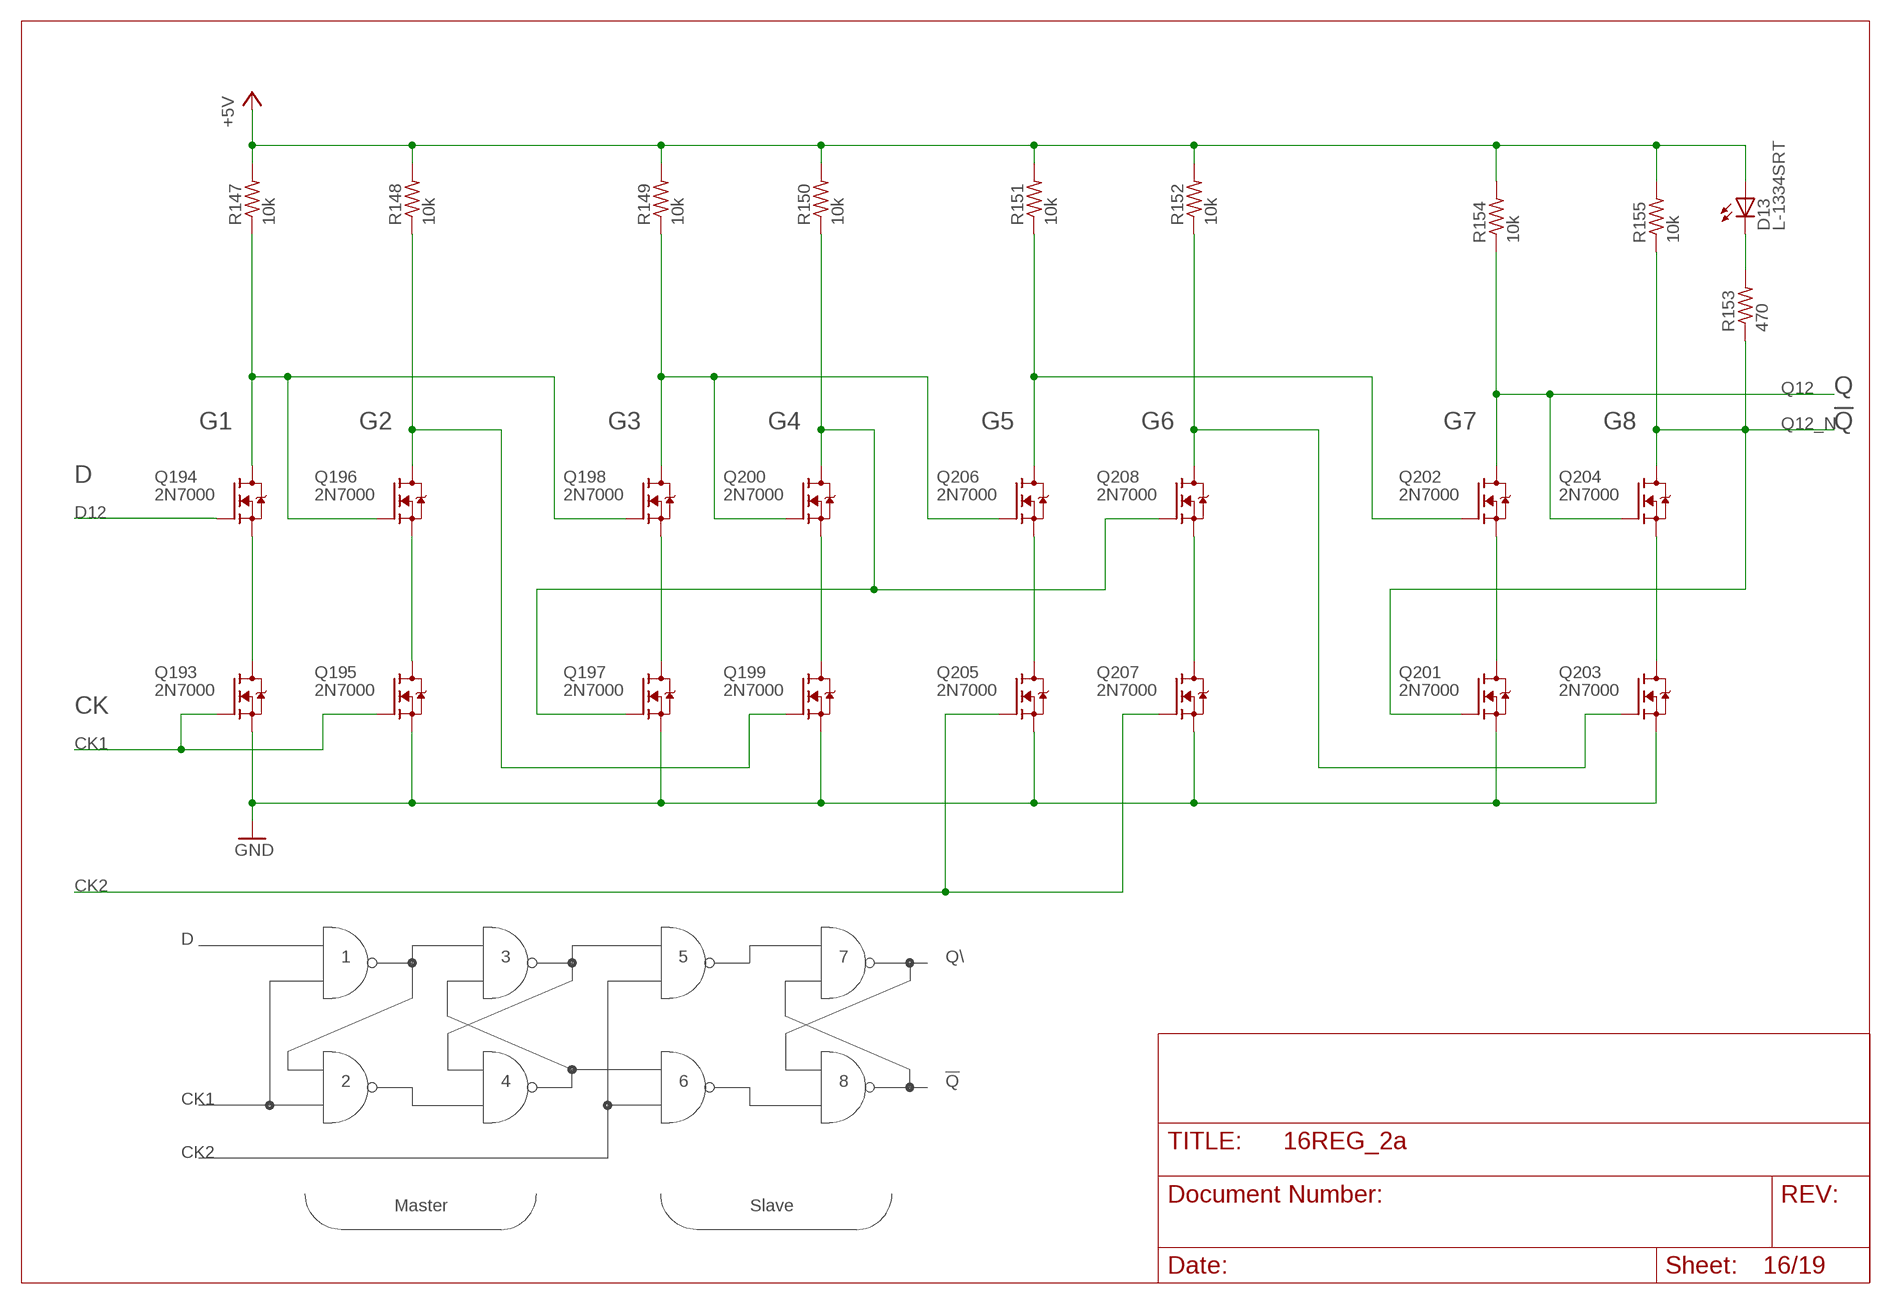
[diagram p15: schematic, sheet 16]
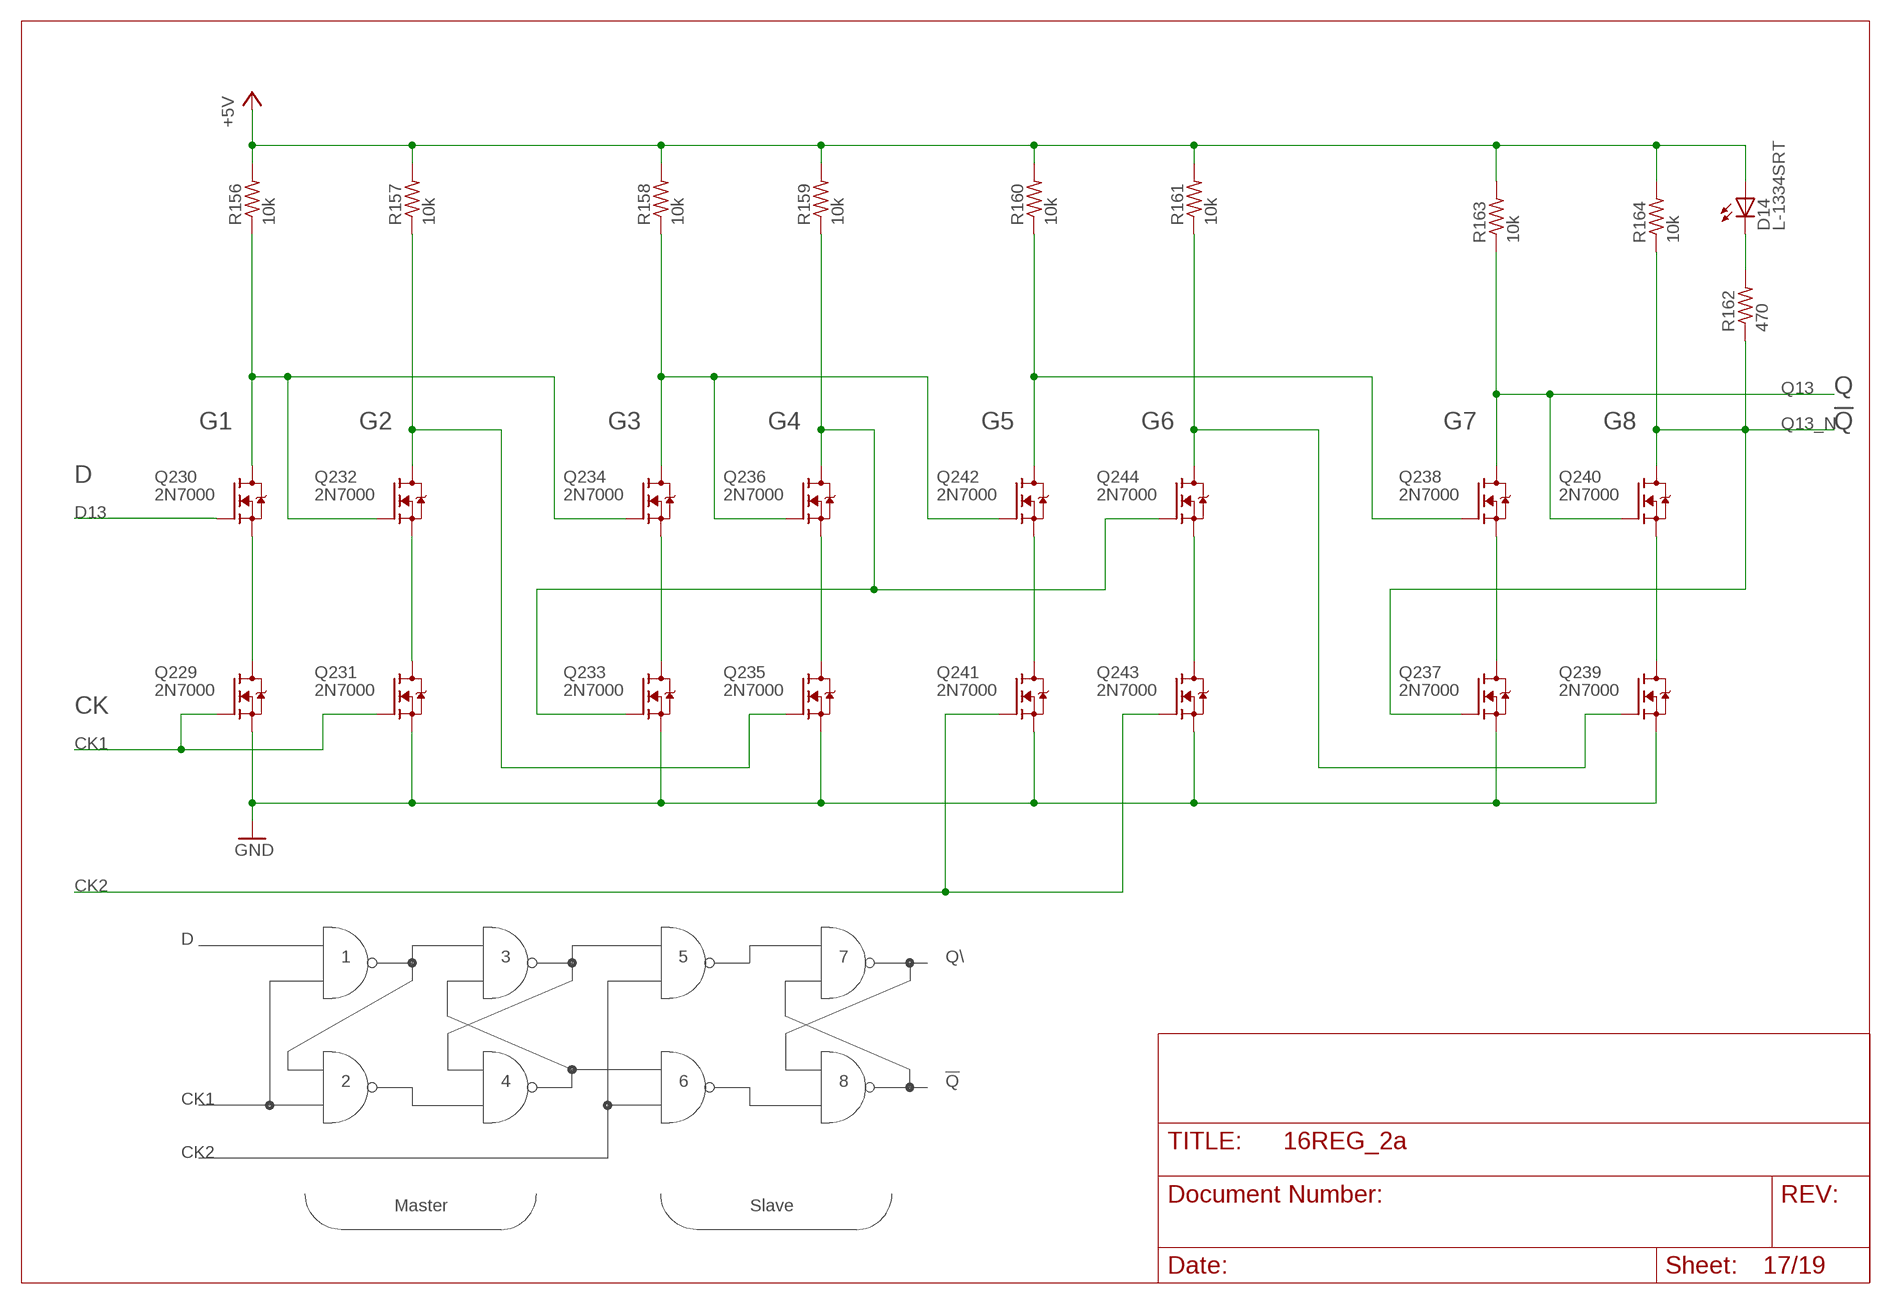
[diagram p16: schematic, sheet 17]
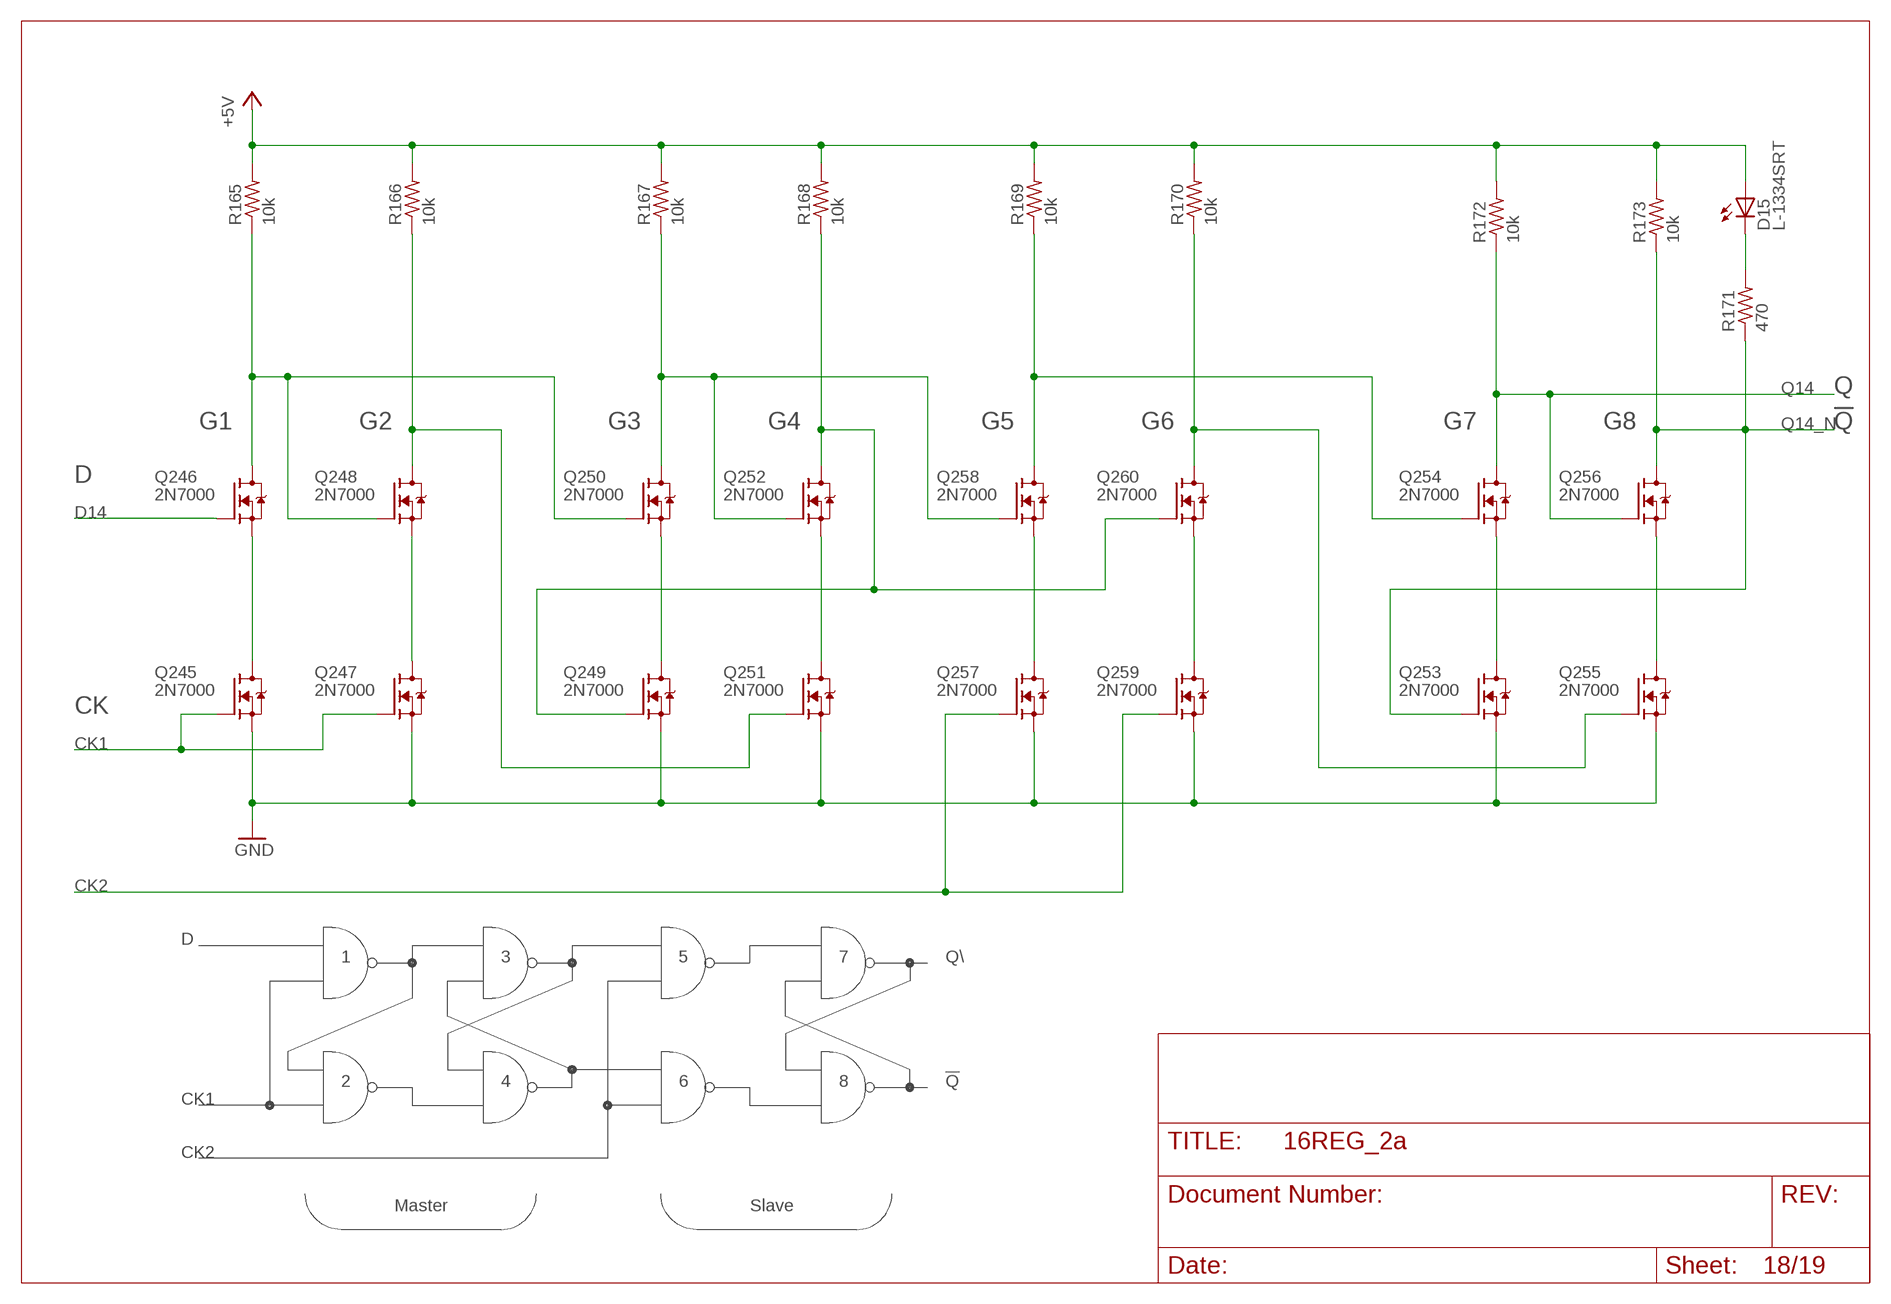
[diagram p17: schematic, sheet 18]
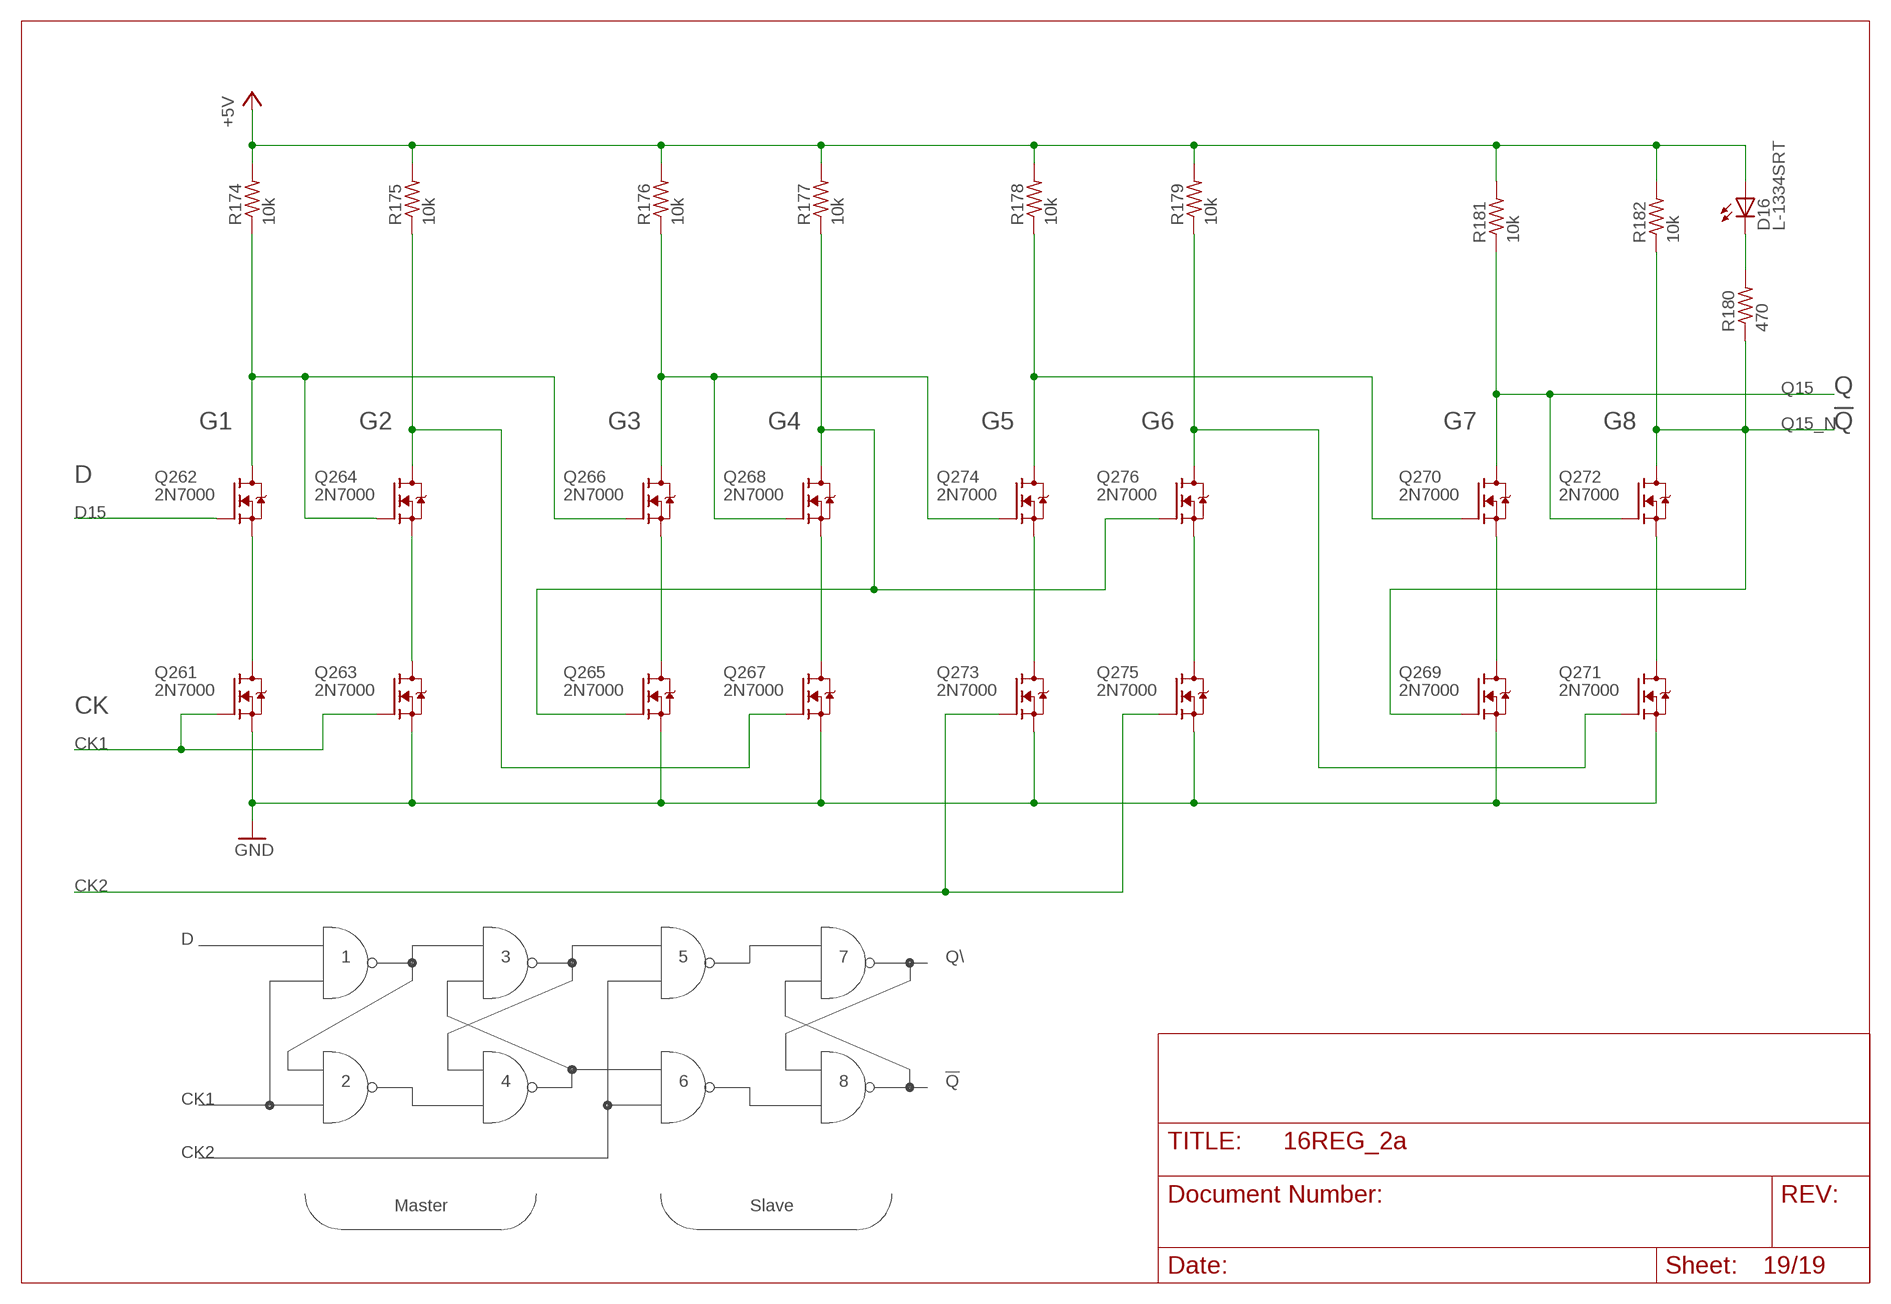
[diagram p18: schematic, sheet 19]

(export (version "E")
  (design (tool "Eeschema 10.0.6"))
  (components
    (comp (ref "D2")
      (value "L-1334SRT")
      (footprint "eagle-import:LED3MM")
      (libsource (lib "eagle-import") (part "L-1334SRT"))
    )
    (comp (ref "Q17")
      (value "2N7000")
      (footprint "eagle-import:TO92-DGS")
      (libsource (lib "eagle-import") (part "2N7000"))
    )
    (comp (ref "Q18")
      (value "2N7000")
      (footprint "eagle-import:TO92-DGS")
      (libsource (lib "eagle-import") (part "2N7000"))
    )
    (comp (ref "Q19")
      (value "2N7000")
      (footprint "eagle-import:TO92-DGS")
      (libsource (lib "eagle-import") (part "2N7000"))
    )
    (comp (ref "Q20")
      (value "2N7000")
      (footprint "eagle-import:TO92-DGS")
      (libsource (lib "eagle-import") (part "2N7000"))
    )
    (comp (ref "Q21")
      (value "2N7000")
      (footprint "eagle-import:TO92-DGS")
      (libsource (lib "eagle-import") (part "2N7000"))
    )
    (comp (ref "Q22")
      (value "2N7000")
      (footprint "eagle-import:TO92-DGS")
      (libsource (lib "eagle-import") (part "2N7000"))
    )
    (comp (ref "Q23")
      (value "2N7000")
      (footprint "eagle-import:TO92-DGS")
      (libsource (lib "eagle-import") (part "2N7000"))
    )
    (comp (ref "Q24")
      (value "2N7000")
      (footprint "eagle-import:TO92-DGS")
      (libsource (lib "eagle-import") (part "2N7000"))
    )
    (comp (ref "Q25")
      (value "2N7000")
      (footprint "eagle-import:TO92-DGS")
      (libsource (lib "eagle-import") (part "2N7000"))
    )
    (comp (ref "Q26")
      (value "2N7000")
      (footprint "eagle-import:TO92-DGS")
      (libsource (lib "eagle-import") (part "2N7000"))
    )
    (comp (ref "Q27")
      (value "2N7000")
      (footprint "eagle-import:TO92-DGS")
      (libsource (lib "eagle-import") (part "2N7000"))
    )
    (comp (ref "Q28")
      (value "2N7000")
      (footprint "eagle-import:TO92-DGS")
      (libsource (lib "eagle-import") (part "2N7000"))
    )
    (comp (ref "Q29")
      (value "2N7000")
      (footprint "eagle-import:TO92-DGS")
      (libsource (lib "eagle-import") (part "2N7000"))
    )
    (comp (ref "Q30")
      (value "2N7000")
      (footprint "eagle-import:TO92-DGS")
      (libsource (lib "eagle-import") (part "2N7000"))
    )
    (comp (ref "Q31")
      (value "2N7000")
      (footprint "eagle-import:TO92-DGS")
      (libsource (lib "eagle-import") (part "2N7000"))
    )
    (comp (ref "Q32")
      (value "2N7000")
      (footprint "eagle-import:TO92-DGS")
      (libsource (lib "eagle-import") (part "2N7000"))
    )
    (comp (ref "R26")
      (value "10k")
      (footprint "eagle-import:R_P2INCH")
      (libsource (lib "eagle-import") (part "R_P2INCH"))
    )
    (comp (ref "R27")
      (value "10k")
      (footprint "eagle-import:R_P2INCH")
      (libsource (lib "eagle-import") (part "R_P2INCH"))
    )
    (comp (ref "R28")
      (value "10k")
      (footprint "eagle-import:R_P2INCH")
      (libsource (lib "eagle-import") (part "R_P2INCH"))
    )
    (comp (ref "R29")
      (value "10k")
      (footprint "eagle-import:R_P2INCH")
      (libsource (lib "eagle-import") (part "R_P2INCH"))
    )
    (comp (ref "R30")
      (value "10k")
      (footprint "eagle-import:R_P2INCH")
      (libsource (lib "eagle-import") (part "R_P2INCH"))
    )
    (comp (ref "R31")
      (value "10k")
      (footprint "eagle-import:R_P2INCH")
      (libsource (lib "eagle-import") (part "R_P2INCH"))
    )
    (comp (ref "R32")
      (value "470")
      (footprint "eagle-import:R_P2INCH")
      (libsource (lib "eagle-import") (part "R_P2INCH"))
    )
    (comp (ref "R33")
      (value "10k")
      (footprint "eagle-import:R_P2INCH")
      (libsource (lib "eagle-import") (part "R_P2INCH"))
    )
    (comp (ref "R34")
      (value "10k")
      (footprint "eagle-import:R_P2INCH")
      (libsource (lib "eagle-import") (part "R_P2INCH"))
    )
    (comp (ref "D6")
      (value "L-1334SRT")
      (footprint "eagle-import:LED3MM")
      (libsource (lib "eagle-import") (part "L-1334SRT"))
    )
    (comp (ref "Q81")
      (value "2N7000")
      (footprint "eagle-import:TO92-DGS")
      (libsource (lib "eagle-import") (part "2N7000"))
    )
    (comp (ref "Q82")
      (value "2N7000")
      (footprint "eagle-import:TO92-DGS")
      (libsource (lib "eagle-import") (part "2N7000"))
    )
    (comp (ref "Q83")
      (value "2N7000")
      (footprint "eagle-import:TO92-DGS")
      (libsource (lib "eagle-import") (part "2N7000"))
    )
    (comp (ref "Q84")
      (value "2N7000")
      (footprint "eagle-import:TO92-DGS")
      (libsource (lib "eagle-import") (part "2N7000"))
    )
    (comp (ref "Q85")
      (value "2N7000")
      (footprint "eagle-import:TO92-DGS")
      (libsource (lib "eagle-import") (part "2N7000"))
    )
    (comp (ref "Q86")
      (value "2N7000")
      (footprint "eagle-import:TO92-DGS")
      (libsource (lib "eagle-import") (part "2N7000"))
    )
    (comp (ref "Q87")
      (value "2N7000")
      (footprint "eagle-import:TO92-DGS")
      (libsource (lib "eagle-import") (part "2N7000"))
    )
    (comp (ref "Q88")
      (value "2N7000")
      (footprint "eagle-import:TO92-DGS")
      (libsource (lib "eagle-import") (part "2N7000"))
    )
    (comp (ref "Q89")
      (value "2N7000")
      (footprint "eagle-import:TO92-DGS")
      (libsource (lib "eagle-import") (part "2N7000"))
    )
    (comp (ref "Q90")
      (value "2N7000")
      (footprint "eagle-import:TO92-DGS")
      (libsource (lib "eagle-import") (part "2N7000"))
    )
    (comp (ref "Q91")
      (value "2N7000")
      (footprint "eagle-import:TO92-DGS")
      (libsource (lib "eagle-import") (part "2N7000"))
    )
    (comp (ref "Q92")
      (value "2N7000")
      (footprint "eagle-import:TO92-DGS")
      (libsource (lib "eagle-import") (part "2N7000"))
    )
    (comp (ref "Q93")
      (value "2N7000")
      (footprint "eagle-import:TO92-DGS")
      (libsource (lib "eagle-import") (part "2N7000"))
    )
    (comp (ref "Q94")
      (value "2N7000")
      (footprint "eagle-import:TO92-DGS")
      (libsource (lib "eagle-import") (part "2N7000"))
    )
    (comp (ref "Q95")
      (value "2N7000")
      (footprint "eagle-import:TO92-DGS")
      (libsource (lib "eagle-import") (part "2N7000"))
    )
    (comp (ref "Q96")
      (value "2N7000")
      (footprint "eagle-import:TO92-DGS")
      (libsource (lib "eagle-import") (part "2N7000"))
    )
    (comp (ref "R62")
      (value "10k")
      (footprint "eagle-import:R_P2INCH")
      (libsource (lib "eagle-import") (part "R_P2INCH"))
    )
    (comp (ref "R63")
      (value "10k")
      (footprint "eagle-import:R_P2INCH")
      (libsource (lib "eagle-import") (part "R_P2INCH"))
    )
    (comp (ref "R64")
      (value "10k")
      (footprint "eagle-import:R_P2INCH")
      (libsource (lib "eagle-import") (part "R_P2INCH"))
    )
    (comp (ref "R65")
      (value "10k")
      (footprint "eagle-import:R_P2INCH")
      (libsource (lib "eagle-import") (part "R_P2INCH"))
    )
    (comp (ref "R66")
      (value "10k")
      (footprint "eagle-import:R_P2INCH")
      (libsource (lib "eagle-import") (part "R_P2INCH"))
    )
    (comp (ref "R67")
      (value "10k")
      (footprint "eagle-import:R_P2INCH")
      (libsource (lib "eagle-import") (part "R_P2INCH"))
    )
    (comp (ref "R68")
      (value "470")
      (footprint "eagle-import:R_P2INCH")
      (libsource (lib "eagle-import") (part "R_P2INCH"))
    )
    (comp (ref "R69")
      (value "10k")
      (footprint "eagle-import:R_P2INCH")
      (libsource (lib "eagle-import") (part "R_P2INCH"))
    )
    (comp (ref "R70")
      (value "10k")
      (footprint "eagle-import:R_P2INCH")
      (libsource (lib "eagle-import") (part "R_P2INCH"))
    )
    (comp (ref "D1")
      (value "L-1334SRT")
      (footprint "eagle-import:LED3MM")
      (libsource (lib "eagle-import") (part "L-1334SRT"))
    )
    (comp (ref "Q1")
      (value "2N7000")
      (footprint "eagle-import:TO92-DGS")
      (libsource (lib "eagle-import") (part "2N7000"))
    )
    (comp (ref "Q2")
      (value "2N7000")
      (footprint "eagle-import:TO92-DGS")
      (libsource (lib "eagle-import") (part "2N7000"))
    )
    (comp (ref "Q3")
      (value "2N7000")
      (footprint "eagle-import:TO92-DGS")
      (libsource (lib "eagle-import") (part "2N7000"))
    )
    (comp (ref "Q4")
      (value "2N7000")
      (footprint "eagle-import:TO92-DGS")
      (libsource (lib "eagle-import") (part "2N7000"))
    )
    (comp (ref "Q5")
      (value "2N7000")
      (footprint "eagle-import:TO92-DGS")
      (libsource (lib "eagle-import") (part "2N7000"))
    )
    (comp (ref "Q6")
      (value "2N7000")
      (footprint "eagle-import:TO92-DGS")
      (libsource (lib "eagle-import") (part "2N7000"))
    )
    (comp (ref "Q7")
      (value "2N7000")
      (footprint "eagle-import:TO92-DGS")
      (libsource (lib "eagle-import") (part "2N7000"))
    )
    (comp (ref "Q8")
      (value "2N7000")
      (footprint "eagle-import:TO92-DGS")
      (libsource (lib "eagle-import") (part "2N7000"))
    )
    (comp (ref "Q9")
      (value "2N7000")
      (footprint "eagle-import:TO92-DGS")
      (libsource (lib "eagle-import") (part "2N7000"))
    )
    (comp (ref "Q10")
      (value "2N7000")
      (footprint "eagle-import:TO92-DGS")
      (libsource (lib "eagle-import") (part "2N7000"))
    )
    (comp (ref "Q11")
      (value "2N7000")
      (footprint "eagle-import:TO92-DGS")
      (libsource (lib "eagle-import") (part "2N7000"))
    )
    (comp (ref "Q12")
      (value "2N7000")
      (footprint "eagle-import:TO92-DGS")
      (libsource (lib "eagle-import") (part "2N7000"))
    )
    (comp (ref "Q13")
      (value "2N7000")
      (footprint "eagle-import:TO92-DGS")
      (libsource (lib "eagle-import") (part "2N7000"))
    )
    (comp (ref "Q14")
      (value "2N7000")
      (footprint "eagle-import:TO92-DGS")
      (libsource (lib "eagle-import") (part "2N7000"))
    )
    (comp (ref "Q15")
      (value "2N7000")
      (footprint "eagle-import:TO92-DGS")
      (libsource (lib "eagle-import") (part "2N7000"))
    )
    (comp (ref "Q16")
      (value "2N7000")
      (footprint "eagle-import:TO92-DGS")
      (libsource (lib "eagle-import") (part "2N7000"))
    )
    (comp (ref "R1")
      (value "10k")
      (footprint "eagle-import:R_P2INCH")
      (libsource (lib "eagle-import") (part "R_P2INCH"))
    )
    (comp (ref "R2")
      (value "10k")
      (footprint "eagle-import:R_P2INCH")
      (libsource (lib "eagle-import") (part "R_P2INCH"))
    )
    (comp (ref "R3")
      (value "10k")
      (footprint "eagle-import:R_P2INCH")
      (libsource (lib "eagle-import") (part "R_P2INCH"))
    )
    (comp (ref "R4")
      (value "10k")
      (footprint "eagle-import:R_P2INCH")
      (libsource (lib "eagle-import") (part "R_P2INCH"))
    )
    (comp (ref "R5")
      (value "10k")
      (footprint "eagle-import:R_P2INCH")
      (libsource (lib "eagle-import") (part "R_P2INCH"))
    )
    (comp (ref "R6")
      (value "10k")
      (footprint "eagle-import:R_P2INCH")
      (libsource (lib "eagle-import") (part "R_P2INCH"))
    )
    (comp (ref "R7")
      (value "470")
      (footprint "eagle-import:R_P2INCH")
      (libsource (lib "eagle-import") (part "R_P2INCH"))
    )
    (comp (ref "R8")
      (value "10k")
      (footprint "eagle-import:R_P2INCH")
      (libsource (lib "eagle-import") (part "R_P2INCH"))
    )
    (comp (ref "R9")
      (value "10k")
      (footprint "eagle-import:R_P2INCH")
      (libsource (lib "eagle-import") (part "R_P2INCH"))
    )
    (comp (ref "D11")
      (value "L-1334SRT")
      (footprint "eagle-import:LED3MM")
      (libsource (lib "eagle-import") (part "L-1334SRT"))
    )
    (comp (ref "Q161")
      (value "2N7000")
      (footprint "eagle-import:TO92-DGS")
      (libsource (lib "eagle-import") (part "2N7000"))
    )
    (comp (ref "Q162")
      (value "2N7000")
      (footprint "eagle-import:TO92-DGS")
      (libsource (lib "eagle-import") (part "2N7000"))
    )
    (comp (ref "Q163")
      (value "2N7000")
      (footprint "eagle-import:TO92-DGS")
      (libsource (lib "eagle-import") (part "2N7000"))
    )
    (comp (ref "Q164")
      (value "2N7000")
      (footprint "eagle-import:TO92-DGS")
      (libsource (lib "eagle-import") (part "2N7000"))
    )
    (comp (ref "Q165")
      (value "2N7000")
      (footprint "eagle-import:TO92-DGS")
      (libsource (lib "eagle-import") (part "2N7000"))
    )
    (comp (ref "Q166")
      (value "2N7000")
      (footprint "eagle-import:TO92-DGS")
      (libsource (lib "eagle-import") (part "2N7000"))
    )
    (comp (ref "Q167")
      (value "2N7000")
      (footprint "eagle-import:TO92-DGS")
      (libsource (lib "eagle-import") (part "2N7000"))
    )
    (comp (ref "Q168")
      (value "2N7000")
      (footprint "eagle-import:TO92-DGS")
      (libsource (lib "eagle-import") (part "2N7000"))
    )
    (comp (ref "Q169")
      (value "2N7000")
      (footprint "eagle-import:TO92-DGS")
      (libsource (lib "eagle-import") (part "2N7000"))
    )
    (comp (ref "Q170")
      (value "2N7000")
      (footprint "eagle-import:TO92-DGS")
      (libsource (lib "eagle-import") (part "2N7000"))
    )
    (comp (ref "Q171")
      (value "2N7000")
      (footprint "eagle-import:TO92-DGS")
      (libsource (lib "eagle-import") (part "2N7000"))
    )
    (comp (ref "Q172")
      (value "2N7000")
      (footprint "eagle-import:TO92-DGS")
      (libsource (lib "eagle-import") (part "2N7000"))
    )
    (comp (ref "Q173")
      (value "2N7000")
      (footprint "eagle-import:TO92-DGS")
      (libsource (lib "eagle-import") (part "2N7000"))
    )
    (comp (ref "Q174")
      (value "2N7000")
      (footprint "eagle-import:TO92-DGS")
      (libsource (lib "eagle-import") (part "2N7000"))
    )
    (comp (ref "Q175")
      (value "2N7000")
      (footprint "eagle-import:TO92-DGS")
      (libsource (lib "eagle-import") (part "2N7000"))
    )
    (comp (ref "Q176")
      (value "2N7000")
      (footprint "eagle-import:TO92-DGS")
      (libsource (lib "eagle-import") (part "2N7000"))
    )
    (comp (ref "R107")
      (value "10k")
      (footprint "eagle-import:R_P2INCH")
      (libsource (lib "eagle-import") (part "R_P2INCH"))
    )
    (comp (ref "R108")
      (value "10k")
      (footprint "eagle-import:R_P2INCH")
      (libsource (lib "eagle-import") (part "R_P2INCH"))
    )
    (comp (ref "R109")
      (value "10k")
      (footprint "eagle-import:R_P2INCH")
      (libsource (lib "eagle-import") (part "R_P2INCH"))
    )
    (comp (ref "R110")
      (value "10k")
      (footprint "eagle-import:R_P2INCH")
      (libsource (lib "eagle-import") (part "R_P2INCH"))
    )
    (comp (ref "R111")
      (value "10k")
      (footprint "eagle-import:R_P2INCH")
      (libsource (lib "eagle-import") (part "R_P2INCH"))
    )
    (comp (ref "R112")
      (value "10k")
      (footprint "eagle-import:R_P2INCH")
      (libsource (lib "eagle-import") (part "R_P2INCH"))
    )
    (comp (ref "R135")
      (value "470")
      (footprint "eagle-import:R_P2INCH")
      (libsource (lib "eagle-import") (part "R_P2INCH"))
    )
    (comp (ref "R136")
      (value "10k")
      (footprint "eagle-import:R_P2INCH")
      (libsource (lib "eagle-import") (part "R_P2INCH"))
    )
    (comp (ref "R137")
      (value "10k")
      (footprint "eagle-import:R_P2INCH")
      (libsource (lib "eagle-import") (part "R_P2INCH"))
    )
    (comp (ref "D8")
      (value "L-1334SRT")
      (footprint "eagle-import:LED3MM")
      (libsource (lib "eagle-import") (part "L-1334SRT"))
    )
    (comp (ref "Q113")
      (value "2N7000")
      (footprint "eagle-import:TO92-DGS")
      (libsource (lib "eagle-import") (part "2N7000"))
    )
    (comp (ref "Q114")
      (value "2N7000")
      (footprint "eagle-import:TO92-DGS")
      (libsource (lib "eagle-import") (part "2N7000"))
    )
    (comp (ref "Q115")
      (value "2N7000")
      (footprint "eagle-import:TO92-DGS")
      (libsource (lib "eagle-import") (part "2N7000"))
    )
    (comp (ref "Q116")
      (value "2N7000")
      (footprint "eagle-import:TO92-DGS")
      (libsource (lib "eagle-import") (part "2N7000"))
    )
    (comp (ref "Q117")
      (value "2N7000")
      (footprint "eagle-import:TO92-DGS")
      (libsource (lib "eagle-import") (part "2N7000"))
    )
    (comp (ref "Q118")
      (value "2N7000")
      (footprint "eagle-import:TO92-DGS")
      (libsource (lib "eagle-import") (part "2N7000"))
    )
    (comp (ref "Q119")
      (value "2N7000")
      (footprint "eagle-import:TO92-DGS")
      (libsource (lib "eagle-import") (part "2N7000"))
    )
    (comp (ref "Q120")
      (value "2N7000")
      (footprint "eagle-import:TO92-DGS")
      (libsource (lib "eagle-import") (part "2N7000"))
    )
    (comp (ref "Q121")
      (value "2N7000")
      (footprint "eagle-import:TO92-DGS")
      (libsource (lib "eagle-import") (part "2N7000"))
    )
    (comp (ref "Q122")
      (value "2N7000")
      (footprint "eagle-import:TO92-DGS")
      (libsource (lib "eagle-import") (part "2N7000"))
    )
    (comp (ref "Q123")
      (value "2N7000")
      (footprint "eagle-import:TO92-DGS")
      (libsource (lib "eagle-import") (part "2N7000"))
    )
    (comp (ref "Q124")
      (value "2N7000")
      (footprint "eagle-import:TO92-DGS")
      (libsource (lib "eagle-import") (part "2N7000"))
    )
    (comp (ref "Q125")
      (value "2N7000")
      (footprint "eagle-import:TO92-DGS")
      (libsource (lib "eagle-import") (part "2N7000"))
    )
    (comp (ref "Q126")
      (value "2N7000")
      (footprint "eagle-import:TO92-DGS")
      (libsource (lib "eagle-import") (part "2N7000"))
    )
    (comp (ref "Q127")
      (value "2N7000")
      (footprint "eagle-import:TO92-DGS")
      (libsource (lib "eagle-import") (part "2N7000"))
    )
    (comp (ref "Q128")
      (value "2N7000")
      (footprint "eagle-import:TO92-DGS")
      (libsource (lib "eagle-import") (part "2N7000"))
    )
    (comp (ref "R80")
      (value "10k")
      (footprint "eagle-import:R_P2INCH")
      (libsource (lib "eagle-import") (part "R_P2INCH"))
    )
    (comp (ref "R81")
      (value "10k")
      (footprint "eagle-import:R_P2INCH")
      (libsource (lib "eagle-import") (part "R_P2INCH"))
    )
    (comp (ref "R82")
      (value "10k")
      (footprint "eagle-import:R_P2INCH")
      (libsource (lib "eagle-import") (part "R_P2INCH"))
    )
    (comp (ref "R83")
      (value "10k")
      (footprint "eagle-import:R_P2INCH")
      (libsource (lib "eagle-import") (part "R_P2INCH"))
    )
    (comp (ref "R84")
      (value "10k")
      (footprint "eagle-import:R_P2INCH")
      (libsource (lib "eagle-import") (part "R_P2INCH"))
    )
    (comp (ref "R85")
      (value "10k")
      (footprint "eagle-import:R_P2INCH")
      (libsource (lib "eagle-import") (part "R_P2INCH"))
    )
    (comp (ref "R86")
      (value "470")
      (footprint "eagle-import:R_P2INCH")
      (libsource (lib "eagle-import") (part "R_P2INCH"))
    )
    (comp (ref "R87")
      (value "10k")
      (footprint "eagle-import:R_P2INCH")
      (libsource (lib "eagle-import") (part "R_P2INCH"))
    )
    (comp (ref "R88")
      (value "10k")
      (footprint "eagle-import:R_P2INCH")
      (libsource (lib "eagle-import") (part "R_P2INCH"))
    )
    (comp (ref "D3")
      (value "L-1334SRT")
      (footprint "eagle-import:LED3MM")
      (libsource (lib "eagle-import") (part "L-1334SRT"))
    )
    (comp (ref "Q33")
      (value "2N7000")
      (footprint "eagle-import:TO92-DGS")
      (libsource (lib "eagle-import") (part "2N7000"))
    )
    (comp (ref "Q34")
      (value "2N7000")
      (footprint "eagle-import:TO92-DGS")
      (libsource (lib "eagle-import") (part "2N7000"))
    )
    (comp (ref "Q35")
      (value "2N7000")
      (footprint "eagle-import:TO92-DGS")
      (libsource (lib "eagle-import") (part "2N7000"))
    )
    (comp (ref "Q36")
      (value "2N7000")
      (footprint "eagle-import:TO92-DGS")
      (libsource (lib "eagle-import") (part "2N7000"))
    )
    (comp (ref "Q37")
      (value "2N7000")
      (footprint "eagle-import:TO92-DGS")
      (libsource (lib "eagle-import") (part "2N7000"))
    )
    (comp (ref "Q38")
      (value "2N7000")
      (footprint "eagle-import:TO92-DGS")
      (libsource (lib "eagle-import") (part "2N7000"))
    )
    (comp (ref "Q39")
      (value "2N7000")
      (footprint "eagle-import:TO92-DGS")
      (libsource (lib "eagle-import") (part "2N7000"))
    )
    (comp (ref "Q40")
      (value "2N7000")
      (footprint "eagle-import:TO92-DGS")
      (libsource (lib "eagle-import") (part "2N7000"))
    )
    (comp (ref "Q41")
      (value "2N7000")
      (footprint "eagle-import:TO92-DGS")
      (libsource (lib "eagle-import") (part "2N7000"))
    )
    (comp (ref "Q42")
      (value "2N7000")
      (footprint "eagle-import:TO92-DGS")
      (libsource (lib "eagle-import") (part "2N7000"))
    )
    (comp (ref "Q43")
      (value "2N7000")
      (footprint "eagle-import:TO92-DGS")
      (libsource (lib "eagle-import") (part "2N7000"))
    )
    (comp (ref "Q44")
      (value "2N7000")
      (footprint "eagle-import:TO92-DGS")
      (libsource (lib "eagle-import") (part "2N7000"))
    )
    (comp (ref "Q45")
      (value "2N7000")
      (footprint "eagle-import:TO92-DGS")
      (libsource (lib "eagle-import") (part "2N7000"))
    )
    (comp (ref "Q46")
      (value "2N7000")
      (footprint "eagle-import:TO92-DGS")
      (libsource (lib "eagle-import") (part "2N7000"))
    )
    (comp (ref "Q47")
      (value "2N7000")
      (footprint "eagle-import:TO92-DGS")
      (libsource (lib "eagle-import") (part "2N7000"))
    )
    (comp (ref "Q48")
      (value "2N7000")
      (footprint "eagle-import:TO92-DGS")
      (libsource (lib "eagle-import") (part "2N7000"))
    )
    (comp (ref "R35")
      (value "10k")
      (footprint "eagle-import:R_P2INCH")
      (libsource (lib "eagle-import") (part "R_P2INCH"))
    )
    (comp (ref "R36")
      (value "10k")
      (footprint "eagle-import:R_P2INCH")
      (libsource (lib "eagle-import") (part "R_P2INCH"))
    )
    (comp (ref "R37")
      (value "10k")
      (footprint "eagle-import:R_P2INCH")
      (libsource (lib "eagle-import") (part "R_P2INCH"))
    )
    (comp (ref "R38")
      (value "10k")
      (footprint "eagle-import:R_P2INCH")
      (libsource (lib "eagle-import") (part "R_P2INCH"))
    )
    (comp (ref "R39")
      (value "10k")
      (footprint "eagle-import:R_P2INCH")
      (libsource (lib "eagle-import") (part "R_P2INCH"))
    )
    (comp (ref "R40")
      (value "10k")
      (footprint "eagle-import:R_P2INCH")
      (libsource (lib "eagle-import") (part "R_P2INCH"))
    )
    (comp (ref "R41")
      (value "470")
      (footprint "eagle-import:R_P2INCH")
      (libsource (lib "eagle-import") (part "R_P2INCH"))
    )
    (comp (ref "R42")
      (value "10k")
      (footprint "eagle-import:R_P2INCH")
      (libsource (lib "eagle-import") (part "R_P2INCH"))
    )
    (comp (ref "R43")
      (value "10k")
      (footprint "eagle-import:R_P2INCH")
      (libsource (lib "eagle-import") (part "R_P2INCH"))
    )
    (comp (ref "C1")
      (value "100n")
      (footprint "eagle-import:CAP_P2INCH")
      (libsource (lib "eagle-import") (part "C_P2INCH"))
    )
    (comp (ref "C2")
      (value "100n")
      (footprint "eagle-import:CAP_P2INCH")
      (libsource (lib "eagle-import") (part "C_P2INCH"))
    )
    (comp (ref "C3")
      (value "100n")
      (footprint "eagle-import:CAP_P2INCH")
      (libsource (lib "eagle-import") (part "C_P2INCH"))
    )
    (comp (ref "C4")
      (value "100n")
      (footprint "eagle-import:CAP_P2INCH")
      (libsource (lib "eagle-import") (part "C_P2INCH"))
    )
    (comp (ref "C5")
      (value "100u")
      (footprint "eagle-import:POLARISED_CAP_2P5")
      (libsource (lib "eagle-import") (part "POLARISED_CAP_2P5"))
    )
    (comp (ref "C6")
      (value "100n")
      (footprint "eagle-import:CAP_P2INCH")
      (libsource (lib "eagle-import") (part "C_P2INCH"))
    )
    (comp (ref "C7")
      (value "100n")
      (footprint "eagle-import:CAP_P2INCH")
      (libsource (lib "eagle-import") (part "C_P2INCH"))
    )
    (comp (ref "C8")
      (value "100n")
      (footprint "eagle-import:CAP_P2INCH")
      (libsource (lib "eagle-import") (part "C_P2INCH"))
    )
    (comp (ref "D17")
      (value "L-1334SRT")
      (footprint "eagle-import:LED3MM")
      (libsource (lib "eagle-import") (part "L-1334SRT"))
    )
    (comp (ref "D34")
      (value "L-1334SRT")
      (footprint "eagle-import:LED3MM")
      (libsource (lib "eagle-import") (part "L-1334SRT"))
    )
    (comp (ref "HOLE1")
      (value "3M_MOUNT_HOLE")
      (footprint "eagle-import:3M_HOLE")
      (libsource (lib "eagle-import") (part "3M_MOUNT_HOLE"))
    )
    (comp (ref "HOLE2")
      (value "3M_MOUNT_HOLE")
      (footprint "eagle-import:3M_HOLE")
      (libsource (lib "eagle-import") (part "3M_MOUNT_HOLE"))
    )
    (comp (ref "HOLE3")
      (value "3M_MOUNT_HOLE")
      (footprint "eagle-import:3M_HOLE")
      (libsource (lib "eagle-import") (part "3M_MOUNT_HOLE"))
    )
    (comp (ref "HOLE4")
      (value "3M_MOUNT_HOLE")
      (footprint "eagle-import:3M_HOLE")
      (libsource (lib "eagle-import") (part "3M_MOUNT_HOLE"))
    )
    (comp (ref "J1")
      (value "20_HDR_LOCKING_RA")
      (footprint "eagle-import:20_HDR_LOCKING_RA")
      (libsource (lib "eagle-import") (part "20_HDR_LOCKING_RA"))
    )
    (comp (ref "J2")
      (value "20_HDR_LOCKING_RA")
      (footprint "eagle-import:20_HDR_LOCKING_RA")
      (libsource (lib "eagle-import") (part "20_HDR_LOCKING_RA"))
    )
    (comp (ref "PP1")
      (value "POWER_PAD")
      (footprint "eagle-import:POWER_PAD")
      (libsource (lib "eagle-import") (part "POWER_PAD"))
    )
    (comp (ref "PP2")
      (value "POWER_PAD")
      (footprint "eagle-import:POWER_PAD")
      (libsource (lib "eagle-import") (part "POWER_PAD"))
    )
    (comp (ref "Q209")
      (value "2N7000")
      (footprint "eagle-import:TO92-DGS")
      (libsource (lib "eagle-import") (part "2N7000"))
    )
    (comp (ref "Q210")
      (value "2N7000")
      (footprint "eagle-import:TO92-DGS")
      (libsource (lib "eagle-import") (part "2N7000"))
    )
    (comp (ref "Q227")
      (value "2N7000")
      (footprint "eagle-import:TO92-DGS")
      (libsource (lib "eagle-import") (part "2N7000"))
    )
    (comp (ref "Q228")
      (value "2N7000")
      (footprint "eagle-import:TO92-DGS")
      (libsource (lib "eagle-import") (part "2N7000"))
    )
    (comp (ref "R113")
      (value "10k")
      (footprint "eagle-import:R_P2INCH")
      (libsource (lib "eagle-import") (part "R_P2INCH"))
    )
    (comp (ref "R114")
      (value "470")
      (footprint "eagle-import:R_P2INCH")
      (libsource (lib "eagle-import") (part "R_P2INCH"))
    )
    (comp (ref "R115")
      (value "10k")
      (footprint "eagle-import:R_P2INCH")
      (libsource (lib "eagle-import") (part "R_P2INCH"))
    )
    (comp (ref "R132")
      (value "10k")
      (footprint "eagle-import:R_P2INCH")
      (libsource (lib "eagle-import") (part "R_P2INCH"))
    )
    (comp (ref "R133")
      (value "470")
      (footprint "eagle-import:R_P2INCH")
      (libsource (lib "eagle-import") (part "R_P2INCH"))
    )
    (comp (ref "R134")
      (value "10k")
      (footprint "eagle-import:R_P2INCH")
      (libsource (lib "eagle-import") (part "R_P2INCH"))
    )
    (comp (ref "TP1")
      (value "TEST_LOOP")
      (footprint "eagle-import:TEST_LOOP")
      (libsource (lib "eagle-import") (part "TEST_LOOP"))
    )
    (comp (ref "TP2")
      (value "TEST_LOOP")
      (footprint "eagle-import:TEST_LOOP")
      (libsource (lib "eagle-import") (part "TEST_LOOP"))
    )
    (comp (ref "D10")
      (value "L-1334SRT")
      (footprint "eagle-import:LED3MM")
      (libsource (lib "eagle-import") (part "L-1334SRT"))
    )
    (comp (ref "Q145")
      (value "2N7000")
      (footprint "eagle-import:TO92-DGS")
      (libsource (lib "eagle-import") (part "2N7000"))
    )
    (comp (ref "Q146")
      (value "2N7000")
      (footprint "eagle-import:TO92-DGS")
      (libsource (lib "eagle-import") (part "2N7000"))
    )
    (comp (ref "Q147")
      (value "2N7000")
      (footprint "eagle-import:TO92-DGS")
      (libsource (lib "eagle-import") (part "2N7000"))
    )
    (comp (ref "Q148")
      (value "2N7000")
      (footprint "eagle-import:TO92-DGS")
      (libsource (lib "eagle-import") (part "2N7000"))
    )
    (comp (ref "Q149")
      (value "2N7000")
      (footprint "eagle-import:TO92-DGS")
      (libsource (lib "eagle-import") (part "2N7000"))
    )
    (comp (ref "Q150")
      (value "2N7000")
      (footprint "eagle-import:TO92-DGS")
      (libsource (lib "eagle-import") (part "2N7000"))
    )
    (comp (ref "Q151")
      (value "2N7000")
      (footprint "eagle-import:TO92-DGS")
      (libsource (lib "eagle-import") (part "2N7000"))
    )
    (comp (ref "Q152")
      (value "2N7000")
      (footprint "eagle-import:TO92-DGS")
      (libsource (lib "eagle-import") (part "2N7000"))
    )
    (comp (ref "Q153")
      (value "2N7000")
      (footprint "eagle-import:TO92-DGS")
      (libsource (lib "eagle-import") (part "2N7000"))
    )
    (comp (ref "Q154")
      (value "2N7000")
      (footprint "eagle-import:TO92-DGS")
      (libsource (lib "eagle-import") (part "2N7000"))
    )
    (comp (ref "Q155")
      (value "2N7000")
      (footprint "eagle-import:TO92-DGS")
      (libsource (lib "eagle-import") (part "2N7000"))
    )
    (comp (ref "Q156")
      (value "2N7000")
      (footprint "eagle-import:TO92-DGS")
      (libsource (lib "eagle-import") (part "2N7000"))
    )
    (comp (ref "Q157")
      (value "2N7000")
      (footprint "eagle-import:TO92-DGS")
      (libsource (lib "eagle-import") (part "2N7000"))
    )
    (comp (ref "Q158")
      (value "2N7000")
      (footprint "eagle-import:TO92-DGS")
      (libsource (lib "eagle-import") (part "2N7000"))
    )
    (comp (ref "Q159")
      (value "2N7000")
      (footprint "eagle-import:TO92-DGS")
      (libsource (lib "eagle-import") (part "2N7000"))
    )
    (comp (ref "Q160")
      (value "2N7000")
      (footprint "eagle-import:TO92-DGS")
      (libsource (lib "eagle-import") (part "2N7000"))
    )
    (comp (ref "R98")
      (value "10k")
      (footprint "eagle-import:R_P2INCH")
      (libsource (lib "eagle-import") (part "R_P2INCH"))
    )
    (comp (ref "R99")
      (value "10k")
      (footprint "eagle-import:R_P2INCH")
      (libsource (lib "eagle-import") (part "R_P2INCH"))
    )
    (comp (ref "R100")
      (value "10k")
      (footprint "eagle-import:R_P2INCH")
      (libsource (lib "eagle-import") (part "R_P2INCH"))
    )
    (comp (ref "R101")
      (value "10k")
      (footprint "eagle-import:R_P2INCH")
      (libsource (lib "eagle-import") (part "R_P2INCH"))
    )
    (comp (ref "R102")
      (value "10k")
      (footprint "eagle-import:R_P2INCH")
      (libsource (lib "eagle-import") (part "R_P2INCH"))
    )
    (comp (ref "R103")
      (value "10k")
      (footprint "eagle-import:R_P2INCH")
      (libsource (lib "eagle-import") (part "R_P2INCH"))
    )
    (comp (ref "R104")
      (value "470")
      (footprint "eagle-import:R_P2INCH")
      (libsource (lib "eagle-import") (part "R_P2INCH"))
    )
    (comp (ref "R105")
      (value "10k")
      (footprint "eagle-import:R_P2INCH")
      (libsource (lib "eagle-import") (part "R_P2INCH"))
    )
    (comp (ref "R106")
      (value "10k")
      (footprint "eagle-import:R_P2INCH")
      (libsource (lib "eagle-import") (part "R_P2INCH"))
    )
    (comp (ref "D7")
      (value "L-1334SRT")
      (footprint "eagle-import:LED3MM")
      (libsource (lib "eagle-import") (part "L-1334SRT"))
    )
    (comp (ref "Q97")
      (value "2N7000")
      (footprint "eagle-import:TO92-DGS")
      (libsource (lib "eagle-import") (part "2N7000"))
    )
    (comp (ref "Q98")
      (value "2N7000")
      (footprint "eagle-import:TO92-DGS")
      (libsource (lib "eagle-import") (part "2N7000"))
    )
    (comp (ref "Q99")
      (value "2N7000")
      (footprint "eagle-import:TO92-DGS")
      (libsource (lib "eagle-import") (part "2N7000"))
    )
    (comp (ref "Q100")
      (value "2N7000")
      (footprint "eagle-import:TO92-DGS")
      (libsource (lib "eagle-import") (part "2N7000"))
    )
    (comp (ref "Q101")
      (value "2N7000")
      (footprint "eagle-import:TO92-DGS")
      (libsource (lib "eagle-import") (part "2N7000"))
    )
    (comp (ref "Q102")
      (value "2N7000")
      (footprint "eagle-import:TO92-DGS")
      (libsource (lib "eagle-import") (part "2N7000"))
    )
    (comp (ref "Q103")
      (value "2N7000")
      (footprint "eagle-import:TO92-DGS")
      (libsource (lib "eagle-import") (part "2N7000"))
    )
    (comp (ref "Q104")
      (value "2N7000")
      (footprint "eagle-import:TO92-DGS")
      (libsource (lib "eagle-import") (part "2N7000"))
    )
    (comp (ref "Q105")
      (value "2N7000")
      (footprint "eagle-import:TO92-DGS")
      (libsource (lib "eagle-import") (part "2N7000"))
    )
    (comp (ref "Q106")
      (value "2N7000")
      (footprint "eagle-import:TO92-DGS")
      (libsource (lib "eagle-import") (part "2N7000"))
    )
    (comp (ref "Q107")
      (value "2N7000")
      (footprint "eagle-import:TO92-DGS")
      (libsource (lib "eagle-import") (part "2N7000"))
    )
    (comp (ref "Q108")
      (value "2N7000")
      (footprint "eagle-import:TO92-DGS")
      (libsource (lib "eagle-import") (part "2N7000"))
    )
    (comp (ref "Q109")
      (value "2N7000")
      (footprint "eagle-import:TO92-DGS")
      (libsource (lib "eagle-import") (part "2N7000"))
    )
    (comp (ref "Q110")
      (value "2N7000")
      (footprint "eagle-import:TO92-DGS")
      (libsource (lib "eagle-import") (part "2N7000"))
    )
    (comp (ref "Q111")
      (value "2N7000")
      (footprint "eagle-import:TO92-DGS")
      (libsource (lib "eagle-import") (part "2N7000"))
    )
    (comp (ref "Q112")
      (value "2N7000")
      (footprint "eagle-import:TO92-DGS")
      (libsource (lib "eagle-import") (part "2N7000"))
    )
    (comp (ref "R71")
      (value "10k")
      (footprint "eagle-import:R_P2INCH")
      (libsource (lib "eagle-import") (part "R_P2INCH"))
    )
    (comp (ref "R72")
      (value "10k")
      (footprint "eagle-import:R_P2INCH")
      (libsource (lib "eagle-import") (part "R_P2INCH"))
    )
    (comp (ref "R73")
      (value "10k")
      (footprint "eagle-import:R_P2INCH")
      (libsource (lib "eagle-import") (part "R_P2INCH"))
    )
    (comp (ref "R74")
      (value "10k")
      (footprint "eagle-import:R_P2INCH")
      (libsource (lib "eagle-import") (part "R_P2INCH"))
    )
    (comp (ref "R75")
      (value "10k")
      (footprint "eagle-import:R_P2INCH")
      (libsource (lib "eagle-import") (part "R_P2INCH"))
    )
    (comp (ref "R76")
      (value "10k")
      (footprint "eagle-import:R_P2INCH")
      (libsource (lib "eagle-import") (part "R_P2INCH"))
    )
    (comp (ref "R77")
      (value "470")
      (footprint "eagle-import:R_P2INCH")
      (libsource (lib "eagle-import") (part "R_P2INCH"))
    )
    (comp (ref "R78")
      (value "10k")
      (footprint "eagle-import:R_P2INCH")
      (libsource (lib "eagle-import") (part "R_P2INCH"))
    )
    (comp (ref "R79")
      (value "10k")
      (footprint "eagle-import:R_P2INCH")
      (libsource (lib "eagle-import") (part "R_P2INCH"))
    )
    (comp (ref "D16")
      (value "L-1334SRT")
      (footprint "eagle-import:LED3MM")
      (libsource (lib "eagle-import") (part "L-1334SRT"))
    )
    (comp (ref "Q261")
      (value "2N7000")
      (footprint "eagle-import:TO92-DGS")
      (libsource (lib "eagle-import") (part "2N7000"))
    )
    (comp (ref "Q262")
      (value "2N7000")
      (footprint "eagle-import:TO92-DGS")
      (libsource (lib "eagle-import") (part "2N7000"))
    )
    (comp (ref "Q263")
      (value "2N7000")
      (footprint "eagle-import:TO92-DGS")
      (libsource (lib "eagle-import") (part "2N7000"))
    )
    (comp (ref "Q264")
      (value "2N7000")
      (footprint "eagle-import:TO92-DGS")
      (libsource (lib "eagle-import") (part "2N7000"))
    )
    (comp (ref "Q265")
      (value "2N7000")
      (footprint "eagle-import:TO92-DGS")
      (libsource (lib "eagle-import") (part "2N7000"))
    )
    (comp (ref "Q266")
      (value "2N7000")
      (footprint "eagle-import:TO92-DGS")
      (libsource (lib "eagle-import") (part "2N7000"))
    )
    (comp (ref "Q267")
      (value "2N7000")
      (footprint "eagle-import:TO92-DGS")
      (libsource (lib "eagle-import") (part "2N7000"))
    )
    (comp (ref "Q268")
      (value "2N7000")
      (footprint "eagle-import:TO92-DGS")
      (libsource (lib "eagle-import") (part "2N7000"))
    )
    (comp (ref "Q269")
      (value "2N7000")
      (footprint "eagle-import:TO92-DGS")
      (libsource (lib "eagle-import") (part "2N7000"))
    )
    (comp (ref "Q270")
      (value "2N7000")
      (footprint "eagle-import:TO92-DGS")
      (libsource (lib "eagle-import") (part "2N7000"))
    )
    (comp (ref "Q271")
      (value "2N7000")
      (footprint "eagle-import:TO92-DGS")
      (libsource (lib "eagle-import") (part "2N7000"))
    )
    (comp (ref "Q272")
      (value "2N7000")
      (footprint "eagle-import:TO92-DGS")
      (libsource (lib "eagle-import") (part "2N7000"))
    )
    (comp (ref "Q273")
      (value "2N7000")
      (footprint "eagle-import:TO92-DGS")
      (libsource (lib "eagle-import") (part "2N7000"))
    )
    (comp (ref "Q274")
      (value "2N7000")
      (footprint "eagle-import:TO92-DGS")
      (libsource (lib "eagle-import") (part "2N7000"))
    )
    (comp (ref "Q275")
      (value "2N7000")
      (footprint "eagle-import:TO92-DGS")
      (libsource (lib "eagle-import") (part "2N7000"))
    )
    (comp (ref "Q276")
      (value "2N7000")
      (footprint "eagle-import:TO92-DGS")
      (libsource (lib "eagle-import") (part "2N7000"))
    )
    (comp (ref "R174")
      (value "10k")
      (footprint "eagle-import:R_P2INCH")
      (libsource (lib "eagle-import") (part "R_P2INCH"))
    )
    (comp (ref "R175")
      (value "10k")
      (footprint "eagle-import:R_P2INCH")
      (libsource (lib "eagle-import") (part "R_P2INCH"))
    )
    (comp (ref "R176")
      (value "10k")
      (footprint "eagle-import:R_P2INCH")
      (libsource (lib "eagle-import") (part "R_P2INCH"))
    )
    (comp (ref "R177")
      (value "10k")
      (footprint "eagle-import:R_P2INCH")
      (libsource (lib "eagle-import") (part "R_P2INCH"))
    )
    (comp (ref "R178")
      (value "10k")
      (footprint "eagle-import:R_P2INCH")
      (libsource (lib "eagle-import") (part "R_P2INCH"))
    )
    (comp (ref "R179")
      (value "10k")
      (footprint "eagle-import:R_P2INCH")
      (libsource (lib "eagle-import") (part "R_P2INCH"))
    )
    (comp (ref "R180")
      (value "470")
      (footprint "eagle-import:R_P2INCH")
      (libsource (lib "eagle-import") (part "R_P2INCH"))
    )
    (comp (ref "R181")
      (value "10k")
      (footprint "eagle-import:R_P2INCH")
      (libsource (lib "eagle-import") (part "R_P2INCH"))
    )
    (comp (ref "R182")
      (value "10k")
      (footprint "eagle-import:R_P2INCH")
      (libsource (lib "eagle-import") (part "R_P2INCH"))
    )
    (comp (ref "D18")
      (value "L-1334SRT")
      (footprint "eagle-import:LED3MM")
      (libsource (lib "eagle-import") (part "L-1334SRT"))
    )
    (comp (ref "D19")
      (value "L-1334SRT")
      (footprint "eagle-import:LED3MM")
      (libsource (lib "eagle-import") (part "L-1334SRT"))
    )
    (comp (ref "D20")
      (value "L-1334SRT")
      (footprint "eagle-import:LED3MM")
      (libsource (lib "eagle-import") (part "L-1334SRT"))
    )
    (comp (ref "D21")
      (value "L-1334SRT")
      (footprint "eagle-import:LED3MM")
      (libsource (lib "eagle-import") (part "L-1334SRT"))
    )
    (comp (ref "D22")
      (value "L-1334SRT")
      (footprint "eagle-import:LED3MM")
      (libsource (lib "eagle-import") (part "L-1334SRT"))
    )
    (comp (ref "D23")
      (value "L-1334SRT")
      (footprint "eagle-import:LED3MM")
      (libsource (lib "eagle-import") (part "L-1334SRT"))
    )
    (comp (ref "D24")
      (value "L-1334SRT")
      (footprint "eagle-import:LED3MM")
      (libsource (lib "eagle-import") (part "L-1334SRT"))
    )
    (comp (ref "D25")
      (value "L-1334SRT")
      (footprint "eagle-import:LED3MM")
      (libsource (lib "eagle-import") (part "L-1334SRT"))
    )
    (comp (ref "D26")
      (value "L-1334SRT")
      (footprint "eagle-import:LED3MM")
      (libsource (lib "eagle-import") (part "L-1334SRT"))
    )
    (comp (ref "D27")
      (value "L-1334SRT")
      (footprint "eagle-import:LED3MM")
      (libsource (lib "eagle-import") (part "L-1334SRT"))
    )
    (comp (ref "D28")
      (value "L-1334SRT")
      (footprint "eagle-import:LED3MM")
      (libsource (lib "eagle-import") (part "L-1334SRT"))
    )
    (comp (ref "D29")
      (value "L-1334SRT")
      (footprint "eagle-import:LED3MM")
      (libsource (lib "eagle-import") (part "L-1334SRT"))
    )
    (comp (ref "D30")
      (value "L-1334SRT")
      (footprint "eagle-import:LED3MM")
      (libsource (lib "eagle-import") (part "L-1334SRT"))
    )
    (comp (ref "D31")
      (value "L-1334SRT")
      (footprint "eagle-import:LED3MM")
      (libsource (lib "eagle-import") (part "L-1334SRT"))
    )
    (comp (ref "D32")
      (value "L-1334SRT")
      (footprint "eagle-import:LED3MM")
      (libsource (lib "eagle-import") (part "L-1334SRT"))
    )
    (comp (ref "D33")
      (value "L-1334SRT")
      (footprint "eagle-import:LED3MM")
      (libsource (lib "eagle-import") (part "L-1334SRT"))
    )
    (comp (ref "Q211")
      (value "2N7000")
      (footprint "eagle-import:TO92-DGS")
      (libsource (lib "eagle-import") (part "2N7000"))
    )
    (comp (ref "Q212")
      (value "2N7000")
      (footprint "eagle-import:TO92-DGS")
      (libsource (lib "eagle-import") (part "2N7000"))
    )
    (comp (ref "Q213")
      (value "2N7000")
      (footprint "eagle-import:TO92-DGS")
      (libsource (lib "eagle-import") (part "2N7000"))
    )
    (comp (ref "Q214")
      (value "2N7000")
      (footprint "eagle-import:TO92-DGS")
      (libsource (lib "eagle-import") (part "2N7000"))
    )
    (comp (ref "Q215")
      (value "2N7000")
      (footprint "eagle-import:TO92-DGS")
      (libsource (lib "eagle-import") (part "2N7000"))
    )
    (comp (ref "Q216")
      (value "2N7000")
      (footprint "eagle-import:TO92-DGS")
      (libsource (lib "eagle-import") (part "2N7000"))
    )
    (comp (ref "Q217")
      (value "2N7000")
      (footprint "eagle-import:TO92-DGS")
      (libsource (lib "eagle-import") (part "2N7000"))
    )
    (comp (ref "Q218")
      (value "2N7000")
      (footprint "eagle-import:TO92-DGS")
      (libsource (lib "eagle-import") (part "2N7000"))
    )
    (comp (ref "Q219")
      (value "2N7000")
      (footprint "eagle-import:TO92-DGS")
      (libsource (lib "eagle-import") (part "2N7000"))
    )
    (comp (ref "Q220")
      (value "2N7000")
      (footprint "eagle-import:TO92-DGS")
      (libsource (lib "eagle-import") (part "2N7000"))
    )
    (comp (ref "Q221")
      (value "2N7000")
      (footprint "eagle-import:TO92-DGS")
      (libsource (lib "eagle-import") (part "2N7000"))
    )
    (comp (ref "Q222")
      (value "2N7000")
      (footprint "eagle-import:TO92-DGS")
      (libsource (lib "eagle-import") (part "2N7000"))
    )
    (comp (ref "Q223")
      (value "2N7000")
      (footprint "eagle-import:TO92-DGS")
      (libsource (lib "eagle-import") (part "2N7000"))
    )
    (comp (ref "Q224")
      (value "2N7000")
      (footprint "eagle-import:TO92-DGS")
      (libsource (lib "eagle-import") (part "2N7000"))
    )
    (comp (ref "Q225")
      (value "2N7000")
      (footprint "eagle-import:TO92-DGS")
      (libsource (lib "eagle-import") (part "2N7000"))
    )
    (comp (ref "Q226")
      (value "2N7000")
      (footprint "eagle-import:TO92-DGS")
      (libsource (lib "eagle-import") (part "2N7000"))
    )
    (comp (ref "R116")
      (value "470")
      (footprint "eagle-import:R_P2INCH")
      (libsource (lib "eagle-import") (part "R_P2INCH"))
    )
    (comp (ref "R117")
      (value "470")
      (footprint "eagle-import:R_P2INCH")
      (libsource (lib "eagle-import") (part "R_P2INCH"))
    )
    (comp (ref "R118")
      (value "470")
      (footprint "eagle-import:R_P2INCH")
      (libsource (lib "eagle-import") (part "R_P2INCH"))
    )
    (comp (ref "R119")
      (value "470")
      (footprint "eagle-import:R_P2INCH")
      (libsource (lib "eagle-import") (part "R_P2INCH"))
    )
    (comp (ref "R120")
      (value "470")
      (footprint "eagle-import:R_P2INCH")
      (libsource (lib "eagle-import") (part "R_P2INCH"))
    )
    (comp (ref "R121")
      (value "470")
      (footprint "eagle-import:R_P2INCH")
      (libsource (lib "eagle-import") (part "R_P2INCH"))
    )
    (comp (ref "R122")
      (value "470")
      (footprint "eagle-import:R_P2INCH")
      (libsource (lib "eagle-import") (part "R_P2INCH"))
    )
    (comp (ref "R123")
      (value "470")
      (footprint "eagle-import:R_P2INCH")
      (libsource (lib "eagle-import") (part "R_P2INCH"))
    )
    (comp (ref "R124")
      (value "470")
      (footprint "eagle-import:R_P2INCH")
      (libsource (lib "eagle-import") (part "R_P2INCH"))
    )
    (comp (ref "R125")
      (value "470")
      (footprint "eagle-import:R_P2INCH")
      (libsource (lib "eagle-import") (part "R_P2INCH"))
    )
    (comp (ref "R126")
      (value "470")
      (footprint "eagle-import:R_P2INCH")
      (libsource (lib "eagle-import") (part "R_P2INCH"))
    )
    (comp (ref "R127")
      (value "470")
      (footprint "eagle-import:R_P2INCH")
      (libsource (lib "eagle-import") (part "R_P2INCH"))
    )
    (comp (ref "R128")
      (value "470")
      (footprint "eagle-import:R_P2INCH")
      (libsource (lib "eagle-import") (part "R_P2INCH"))
    )
    (comp (ref "R129")
      (value "470")
      (footprint "eagle-import:R_P2INCH")
      (libsource (lib "eagle-import") (part "R_P2INCH"))
    )
    (comp (ref "R130")
      (value "470")
      (footprint "eagle-import:R_P2INCH")
      (libsource (lib "eagle-import") (part "R_P2INCH"))
    )
    (comp (ref "R131")
      (value "470")
      (footprint "eagle-import:R_P2INCH")
      (libsource (lib "eagle-import") (part "R_P2INCH"))
    )
    (comp (ref "D13")
      (value "L-1334SRT")
      (footprint "eagle-import:LED3MM")
      (libsource (lib "eagle-import") (part "L-1334SRT"))
    )
    (comp (ref "Q193")
      (value "2N7000")
      (footprint "eagle-import:TO92-DGS")
      (libsource (lib "eagle-import") (part "2N7000"))
    )
    (comp (ref "Q194")
      (value "2N7000")
      (footprint "eagle-import:TO92-DGS")
      (libsource (lib "eagle-import") (part "2N7000"))
    )
    (comp (ref "Q195")
      (value "2N7000")
      (footprint "eagle-import:TO92-DGS")
      (libsource (lib "eagle-import") (part "2N7000"))
    )
    (comp (ref "Q196")
      (value "2N7000")
      (footprint "eagle-import:TO92-DGS")
      (libsource (lib "eagle-import") (part "2N7000"))
    )
    (comp (ref "Q197")
      (value "2N7000")
      (footprint "eagle-import:TO92-DGS")
      (libsource (lib "eagle-import") (part "2N7000"))
    )
    (comp (ref "Q198")
      (value "2N7000")
      (footprint "eagle-import:TO92-DGS")
      (libsource (lib "eagle-import") (part "2N7000"))
    )
    (comp (ref "Q199")
      (value "2N7000")
      (footprint "eagle-import:TO92-DGS")
      (libsource (lib "eagle-import") (part "2N7000"))
    )
    (comp (ref "Q200")
      (value "2N7000")
      (footprint "eagle-import:TO92-DGS")
      (libsource (lib "eagle-import") (part "2N7000"))
    )
    (comp (ref "Q201")
      (value "2N7000")
      (footprint "eagle-import:TO92-DGS")
      (libsource (lib "eagle-import") (part "2N7000"))
    )
    (comp (ref "Q202")
      (value "2N7000")
      (footprint "eagle-import:TO92-DGS")
      (libsource (lib "eagle-import") (part "2N7000"))
    )
    (comp (ref "Q203")
      (value "2N7000")
      (footprint "eagle-import:TO92-DGS")
      (libsource (lib "eagle-import") (part "2N7000"))
    )
    (comp (ref "Q204")
      (value "2N7000")
      (footprint "eagle-import:TO92-DGS")
      (libsource (lib "eagle-import") (part "2N7000"))
    )
    (comp (ref "Q205")
      (value "2N7000")
      (footprint "eagle-import:TO92-DGS")
      (libsource (lib "eagle-import") (part "2N7000"))
    )
    (comp (ref "Q206")
      (value "2N7000")
      (footprint "eagle-import:TO92-DGS")
      (libsource (lib "eagle-import") (part "2N7000"))
    )
    (comp (ref "Q207")
      (value "2N7000")
      (footprint "eagle-import:TO92-DGS")
      (libsource (lib "eagle-import") (part "2N7000"))
    )
    (comp (ref "Q208")
      (value "2N7000")
      (footprint "eagle-import:TO92-DGS")
      (libsource (lib "eagle-import") (part "2N7000"))
    )
    (comp (ref "R147")
      (value "10k")
      (footprint "eagle-import:R_P2INCH")
      (libsource (lib "eagle-import") (part "R_P2INCH"))
    )
    (comp (ref "R148")
      (value "10k")
      (footprint "eagle-import:R_P2INCH")
      (libsource (lib "eagle-import") (part "R_P2INCH"))
    )
    (comp (ref "R149")
      (value "10k")
      (footprint "eagle-import:R_P2INCH")
      (libsource (lib "eagle-import") (part "R_P2INCH"))
    )
    (comp (ref "R150")
      (value "10k")
      (footprint "eagle-import:R_P2INCH")
      (libsource (lib "eagle-import") (part "R_P2INCH"))
    )
    (comp (ref "R151")
      (value "10k")
      (footprint "eagle-import:R_P2INCH")
      (libsource (lib "eagle-import") (part "R_P2INCH"))
    )
    (comp (ref "R152")
      (value "10k")
      (footprint "eagle-import:R_P2INCH")
      (libsource (lib "eagle-import") (part "R_P2INCH"))
    )
    (comp (ref "R153")
      (value "470")
      (footprint "eagle-import:R_P2INCH")
      (libsource (lib "eagle-import") (part "R_P2INCH"))
    )
    (comp (ref "R154")
      (value "10k")
      (footprint "eagle-import:R_P2INCH")
      (libsource (lib "eagle-import") (part "R_P2INCH"))
    )
    (comp (ref "R155")
      (value "10k")
      (footprint "eagle-import:R_P2INCH")
      (libsource (lib "eagle-import") (part "R_P2INCH"))
    )
    (comp (ref "D12")
      (value "L-1334SRT")
      (footprint "eagle-import:LED3MM")
      (libsource (lib "eagle-import") (part "L-1334SRT"))
    )
    (comp (ref "Q177")
      (value "2N7000")
      (footprint "eagle-import:TO92-DGS")
      (libsource (lib "eagle-import") (part "2N7000"))
    )
    (comp (ref "Q178")
      (value "2N7000")
      (footprint "eagle-import:TO92-DGS")
      (libsource (lib "eagle-import") (part "2N7000"))
    )
    (comp (ref "Q179")
      (value "2N7000")
      (footprint "eagle-import:TO92-DGS")
      (libsource (lib "eagle-import") (part "2N7000"))
    )
    (comp (ref "Q180")
      (value "2N7000")
      (footprint "eagle-import:TO92-DGS")
      (libsource (lib "eagle-import") (part "2N7000"))
    )
    (comp (ref "Q181")
      (value "2N7000")
      (footprint "eagle-import:TO92-DGS")
      (libsource (lib "eagle-import") (part "2N7000"))
    )
    (comp (ref "Q182")
      (value "2N7000")
      (footprint "eagle-import:TO92-DGS")
      (libsource (lib "eagle-import") (part "2N7000"))
    )
    (comp (ref "Q183")
      (value "2N7000")
      (footprint "eagle-import:TO92-DGS")
      (libsource (lib "eagle-import") (part "2N7000"))
    )
    (comp (ref "Q184")
      (value "2N7000")
      (footprint "eagle-import:TO92-DGS")
      (libsource (lib "eagle-import") (part "2N7000"))
    )
    (comp (ref "Q185")
      (value "2N7000")
      (footprint "eagle-import:TO92-DGS")
      (libsource (lib "eagle-import") (part "2N7000"))
    )
    (comp (ref "Q186")
      (value "2N7000")
      (footprint "eagle-import:TO92-DGS")
      (libsource (lib "eagle-import") (part "2N7000"))
    )
    (comp (ref "Q187")
      (value "2N7000")
      (footprint "eagle-import:TO92-DGS")
      (libsource (lib "eagle-import") (part "2N7000"))
    )
    (comp (ref "Q188")
      (value "2N7000")
      (footprint "eagle-import:TO92-DGS")
      (libsource (lib "eagle-import") (part "2N7000"))
    )
    (comp (ref "Q189")
      (value "2N7000")
      (footprint "eagle-import:TO92-DGS")
      (libsource (lib "eagle-import") (part "2N7000"))
    )
    (comp (ref "Q190")
      (value "2N7000")
      (footprint "eagle-import:TO92-DGS")
      (libsource (lib "eagle-import") (part "2N7000"))
    )
    (comp (ref "Q191")
      (value "2N7000")
      (footprint "eagle-import:TO92-DGS")
      (libsource (lib "eagle-import") (part "2N7000"))
    )
    (comp (ref "Q192")
      (value "2N7000")
      (footprint "eagle-import:TO92-DGS")
      (libsource (lib "eagle-import") (part "2N7000"))
    )
    (comp (ref "R138")
      (value "10k")
      (footprint "eagle-import:R_P2INCH")
      (libsource (lib "eagle-import") (part "R_P2INCH"))
    )
    (comp (ref "R139")
      (value "10k")
      (footprint "eagle-import:R_P2INCH")
      (libsource (lib "eagle-import") (part "R_P2INCH"))
    )
    (comp (ref "R140")
      (value "10k")
      (footprint "eagle-import:R_P2INCH")
      (libsource (lib "eagle-import") (part "R_P2INCH"))
    )
    (comp (ref "R141")
      (value "10k")
      (footprint "eagle-import:R_P2INCH")
      (libsource (lib "eagle-import") (part "R_P2INCH"))
    )
    (comp (ref "R142")
      (value "10k")
      (footprint "eagle-import:R_P2INCH")
      (libsource (lib "eagle-import") (part "R_P2INCH"))
    )
    (comp (ref "R143")
      (value "10k")
      (footprint "eagle-import:R_P2INCH")
      (libsource (lib "eagle-import") (part "R_P2INCH"))
    )
    (comp (ref "R144")
      (value "470")
      (footprint "eagle-import:R_P2INCH")
      (libsource (lib "eagle-import") (part "R_P2INCH"))
    )
    (comp (ref "R145")
      (value "10k")
      (footprint "eagle-import:R_P2INCH")
      (libsource (lib "eagle-import") (part "R_P2INCH"))
    )
    (comp (ref "R146")
      (value "10k")
      (footprint "eagle-import:R_P2INCH")
      (libsource (lib "eagle-import") (part "R_P2INCH"))
    )
    (comp (ref "D9")
      (value "L-1334SRT")
      (footprint "eagle-import:LED3MM")
      (libsource (lib "eagle-import") (part "L-1334SRT"))
    )
    (comp (ref "Q129")
      (value "2N7000")
      (footprint "eagle-import:TO92-DGS")
      (libsource (lib "eagle-import") (part "2N7000"))
    )
    (comp (ref "Q130")
      (value "2N7000")
      (footprint "eagle-import:TO92-DGS")
      (libsource (lib "eagle-import") (part "2N7000"))
    )
    (comp (ref "Q131")
      (value "2N7000")
      (footprint "eagle-import:TO92-DGS")
      (libsource (lib "eagle-import") (part "2N7000"))
    )
    (comp (ref "Q132")
      (value "2N7000")
      (footprint "eagle-import:TO92-DGS")
      (libsource (lib "eagle-import") (part "2N7000"))
    )
    (comp (ref "Q133")
      (value "2N7000")
      (footprint "eagle-import:TO92-DGS")
      (libsource (lib "eagle-import") (part "2N7000"))
    )
    (comp (ref "Q134")
      (value "2N7000")
      (footprint "eagle-import:TO92-DGS")
      (libsource (lib "eagle-import") (part "2N7000"))
    )
    (comp (ref "Q135")
      (value "2N7000")
      (footprint "eagle-import:TO92-DGS")
      (libsource (lib "eagle-import") (part "2N7000"))
    )
    (comp (ref "Q136")
      (value "2N7000")
      (footprint "eagle-import:TO92-DGS")
      (libsource (lib "eagle-import") (part "2N7000"))
    )
    (comp (ref "Q137")
      (value "2N7000")
      (footprint "eagle-import:TO92-DGS")
      (libsource (lib "eagle-import") (part "2N7000"))
    )
    (comp (ref "Q138")
      (value "2N7000")
      (footprint "eagle-import:TO92-DGS")
      (libsource (lib "eagle-import") (part "2N7000"))
    )
    (comp (ref "Q139")
      (value "2N7000")
      (footprint "eagle-import:TO92-DGS")
      (libsource (lib "eagle-import") (part "2N7000"))
    )
    (comp (ref "Q140")
      (value "2N7000")
      (footprint "eagle-import:TO92-DGS")
      (libsource (lib "eagle-import") (part "2N7000"))
    )
    (comp (ref "Q141")
      (value "2N7000")
      (footprint "eagle-import:TO92-DGS")
      (libsource (lib "eagle-import") (part "2N7000"))
    )
    (comp (ref "Q142")
      (value "2N7000")
      (footprint "eagle-import:TO92-DGS")
      (libsource (lib "eagle-import") (part "2N7000"))
    )
    (comp (ref "Q143")
      (value "2N7000")
      (footprint "eagle-import:TO92-DGS")
      (libsource (lib "eagle-import") (part "2N7000"))
    )
    (comp (ref "Q144")
      (value "2N7000")
      (footprint "eagle-import:TO92-DGS")
      (libsource (lib "eagle-import") (part "2N7000"))
    )
    (comp (ref "R89")
      (value "10k")
      (footprint "eagle-import:R_P2INCH")
      (libsource (lib "eagle-import") (part "R_P2INCH"))
    )
    (comp (ref "R90")
      (value "10k")
      (footprint "eagle-import:R_P2INCH")
      (libsource (lib "eagle-import") (part "R_P2INCH"))
    )
    (comp (ref "R91")
      (value "10k")
      (footprint "eagle-import:R_P2INCH")
      (libsource (lib "eagle-import") (part "R_P2INCH"))
    )
    (comp (ref "R92")
      (value "10k")
      (footprint "eagle-import:R_P2INCH")
      (libsource (lib "eagle-import") (part "R_P2INCH"))
    )
    (comp (ref "R93")
      (value "10k")
      (footprint "eagle-import:R_P2INCH")
      (libsource (lib "eagle-import") (part "R_P2INCH"))
    )
    (comp (ref "R94")
      (value "10k")
      (footprint "eagle-import:R_P2INCH")
      (libsource (lib "eagle-import") (part "R_P2INCH"))
    )
    (comp (ref "R95")
      (value "470")
      (footprint "eagle-import:R_P2INCH")
      (libsource (lib "eagle-import") (part "R_P2INCH"))
    )
    (comp (ref "R96")
      (value "10k")
      (footprint "eagle-import:R_P2INCH")
      (libsource (lib "eagle-import") (part "R_P2INCH"))
    )
    (comp (ref "R97")
      (value "10k")
      (footprint "eagle-import:R_P2INCH")
      (libsource (lib "eagle-import") (part "R_P2INCH"))
    )
    (comp (ref "D4")
      (value "L-1334SRT")
      (footprint "eagle-import:LED3MM")
      (libsource (lib "eagle-import") (part "L-1334SRT"))
    )
    (comp (ref "Q49")
      (value "2N7000")
      (footprint "eagle-import:TO92-DGS")
      (libsource (lib "eagle-import") (part "2N7000"))
    )
    (comp (ref "Q50")
      (value "2N7000")
      (footprint "eagle-import:TO92-DGS")
      (libsource (lib "eagle-import") (part "2N7000"))
    )
    (comp (ref "Q51")
      (value "2N7000")
      (footprint "eagle-import:TO92-DGS")
      (libsource (lib "eagle-import") (part "2N7000"))
    )
    (comp (ref "Q52")
      (value "2N7000")
      (footprint "eagle-import:TO92-DGS")
      (libsource (lib "eagle-import") (part "2N7000"))
    )
    (comp (ref "Q53")
      (value "2N7000")
      (footprint "eagle-import:TO92-DGS")
      (libsource (lib "eagle-import") (part "2N7000"))
    )
    (comp (ref "Q54")
      (value "2N7000")
      (footprint "eagle-import:TO92-DGS")
      (libsource (lib "eagle-import") (part "2N7000"))
    )
    (comp (ref "Q55")
      (value "2N7000")
      (footprint "eagle-import:TO92-DGS")
      (libsource (lib "eagle-import") (part "2N7000"))
    )
    (comp (ref "Q56")
      (value "2N7000")
      (footprint "eagle-import:TO92-DGS")
      (libsource (lib "eagle-import") (part "2N7000"))
    )
    (comp (ref "Q57")
      (value "2N7000")
      (footprint "eagle-import:TO92-DGS")
      (libsource (lib "eagle-import") (part "2N7000"))
    )
    (comp (ref "Q58")
      (value "2N7000")
      (footprint "eagle-import:TO92-DGS")
      (libsource (lib "eagle-import") (part "2N7000"))
    )
    (comp (ref "Q59")
      (value "2N7000")
      (footprint "eagle-import:TO92-DGS")
      (libsource (lib "eagle-import") (part "2N7000"))
    )
    (comp (ref "Q60")
      (value "2N7000")
      (footprint "eagle-import:TO92-DGS")
      (libsource (lib "eagle-import") (part "2N7000"))
    )
    (comp (ref "Q61")
      (value "2N7000")
      (footprint "eagle-import:TO92-DGS")
      (libsource (lib "eagle-import") (part "2N7000"))
    )
    (comp (ref "Q62")
      (value "2N7000")
      (footprint "eagle-import:TO92-DGS")
      (libsource (lib "eagle-import") (part "2N7000"))
    )
    (comp (ref "Q63")
      (value "2N7000")
      (footprint "eagle-import:TO92-DGS")
      (libsource (lib "eagle-import") (part "2N7000"))
    )
    (comp (ref "Q64")
      (value "2N7000")
      (footprint "eagle-import:TO92-DGS")
      (libsource (lib "eagle-import") (part "2N7000"))
    )
    (comp (ref "R44")
      (value "10k")
      (footprint "eagle-import:R_P2INCH")
      (libsource (lib "eagle-import") (part "R_P2INCH"))
    )
    (comp (ref "R45")
      (value "10k")
      (footprint "eagle-import:R_P2INCH")
      (libsource (lib "eagle-import") (part "R_P2INCH"))
    )
    (comp (ref "R46")
      (value "10k")
      (footprint "eagle-import:R_P2INCH")
      (libsource (lib "eagle-import") (part "R_P2INCH"))
    )
    (comp (ref "R47")
      (value "10k")
      (footprint "eagle-import:R_P2INCH")
      (libsource (lib "eagle-import") (part "R_P2INCH"))
    )
    (comp (ref "R48")
      (value "10k")
      (footprint "eagle-import:R_P2INCH")
      (libsource (lib "eagle-import") (part "R_P2INCH"))
    )
    (comp (ref "R49")
      (value "10k")
      (footprint "eagle-import:R_P2INCH")
      (libsource (lib "eagle-import") (part "R_P2INCH"))
    )
    (comp (ref "R50")
      (value "470")
      (footprint "eagle-import:R_P2INCH")
      (libsource (lib "eagle-import") (part "R_P2INCH"))
    )
    (comp (ref "R51")
      (value "10k")
      (footprint "eagle-import:R_P2INCH")
      (libsource (lib "eagle-import") (part "R_P2INCH"))
    )
    (comp (ref "R52")
      (value "10k")
      (footprint "eagle-import:R_P2INCH")
      (libsource (lib "eagle-import") (part "R_P2INCH"))
    )
    (comp (ref "D15")
      (value "L-1334SRT")
      (footprint "eagle-import:LED3MM")
      (libsource (lib "eagle-import") (part "L-1334SRT"))
    )
    (comp (ref "Q245")
      (value "2N7000")
      (footprint "eagle-import:TO92-DGS")
      (libsource (lib "eagle-import") (part "2N7000"))
    )
    (comp (ref "Q246")
      (value "2N7000")
      (footprint "eagle-import:TO92-DGS")
      (libsource (lib "eagle-import") (part "2N7000"))
    )
    (comp (ref "Q247")
      (value "2N7000")
      (footprint "eagle-import:TO92-DGS")
      (libsource (lib "eagle-import") (part "2N7000"))
    )
    (comp (ref "Q248")
      (value "2N7000")
      (footprint "eagle-import:TO92-DGS")
      (libsource (lib "eagle-import") (part "2N7000"))
    )
    (comp (ref "Q249")
      (value "2N7000")
      (footprint "eagle-import:TO92-DGS")
      (libsource (lib "eagle-import") (part "2N7000"))
    )
    (comp (ref "Q250")
      (value "2N7000")
      (footprint "eagle-import:TO92-DGS")
      (libsource (lib "eagle-import") (part "2N7000"))
    )
    (comp (ref "Q251")
      (value "2N7000")
      (footprint "eagle-import:TO92-DGS")
      (libsource (lib "eagle-import") (part "2N7000"))
    )
    (comp (ref "Q252")
      (value "2N7000")
      (footprint "eagle-import:TO92-DGS")
      (libsource (lib "eagle-import") (part "2N7000"))
    )
    (comp (ref "Q253")
      (value "2N7000")
      (footprint "eagle-import:TO92-DGS")
      (libsource (lib "eagle-import") (part "2N7000"))
    )
    (comp (ref "Q254")
      (value "2N7000")
      (footprint "eagle-import:TO92-DGS")
      (libsource (lib "eagle-import") (part "2N7000"))
    )
    (comp (ref "Q255")
      (value "2N7000")
      (footprint "eagle-import:TO92-DGS")
      (libsource (lib "eagle-import") (part "2N7000"))
    )
    (comp (ref "Q256")
      (value "2N7000")
      (footprint "eagle-import:TO92-DGS")
      (libsource (lib "eagle-import") (part "2N7000"))
    )
    (comp (ref "Q257")
      (value "2N7000")
      (footprint "eagle-import:TO92-DGS")
      (libsource (lib "eagle-import") (part "2N7000"))
    )
    (comp (ref "Q258")
      (value "2N7000")
      (footprint "eagle-import:TO92-DGS")
      (libsource (lib "eagle-import") (part "2N7000"))
    )
    (comp (ref "Q259")
      (value "2N7000")
      (footprint "eagle-import:TO92-DGS")
      (libsource (lib "eagle-import") (part "2N7000"))
    )
    (comp (ref "Q260")
      (value "2N7000")
      (footprint "eagle-import:TO92-DGS")
      (libsource (lib "eagle-import") (part "2N7000"))
    )
    (comp (ref "R165")
      (value "10k")
      (footprint "eagle-import:R_P2INCH")
      (libsource (lib "eagle-import") (part "R_P2INCH"))
    )
    (comp (ref "R166")
      (value "10k")
      (footprint "eagle-import:R_P2INCH")
      (libsource (lib "eagle-import") (part "R_P2INCH"))
    )
    (comp (ref "R167")
      (value "10k")
      (footprint "eagle-import:R_P2INCH")
      (libsource (lib "eagle-import") (part "R_P2INCH"))
    )
    (comp (ref "R168")
      (value "10k")
      (footprint "eagle-import:R_P2INCH")
      (libsource (lib "eagle-import") (part "R_P2INCH"))
    )
    (comp (ref "R169")
      (value "10k")
      (footprint "eagle-import:R_P2INCH")
      (libsource (lib "eagle-import") (part "R_P2INCH"))
    )
    (comp (ref "R170")
      (value "10k")
      (footprint "eagle-import:R_P2INCH")
      (libsource (lib "eagle-import") (part "R_P2INCH"))
    )
    (comp (ref "R171")
      (value "470")
      (footprint "eagle-import:R_P2INCH")
      (libsource (lib "eagle-import") (part "R_P2INCH"))
    )
    (comp (ref "R172")
      (value "10k")
      (footprint "eagle-import:R_P2INCH")
      (libsource (lib "eagle-import") (part "R_P2INCH"))
    )
    (comp (ref "R173")
      (value "10k")
      (footprint "eagle-import:R_P2INCH")
      (libsource (lib "eagle-import") (part "R_P2INCH"))
    )
    (comp (ref "J3")
      (value "30_HDR_LOCKING_RA")
      (footprint "eagle-import:30_HDR_LOCKING_RA")
      (libsource (lib "eagle-import") (part "30_HDR_LOCKING_RA"))
    )
    (comp (ref "D14")
      (value "L-1334SRT")
      (footprint "eagle-import:LED3MM")
      (libsource (lib "eagle-import") (part "L-1334SRT"))
    )
    (comp (ref "Q229")
      (value "2N7000")
      (footprint "eagle-import:TO92-DGS")
      (libsource (lib "eagle-import") (part "2N7000"))
    )
    (comp (ref "Q230")
      (value "2N7000")
      (footprint "eagle-import:TO92-DGS")
      (libsource (lib "eagle-import") (part "2N7000"))
    )
    (comp (ref "Q231")
      (value "2N7000")
      (footprint "eagle-import:TO92-DGS")
      (libsource (lib "eagle-import") (part "2N7000"))
    )
    (comp (ref "Q232")
      (value "2N7000")
      (footprint "eagle-import:TO92-DGS")
      (libsource (lib "eagle-import") (part "2N7000"))
    )
    (comp (ref "Q233")
      (value "2N7000")
      (footprint "eagle-import:TO92-DGS")
      (libsource (lib "eagle-import") (part "2N7000"))
    )
    (comp (ref "Q234")
      (value "2N7000")
      (footprint "eagle-import:TO92-DGS")
      (libsource (lib "eagle-import") (part "2N7000"))
    )
    (comp (ref "Q235")
      (value "2N7000")
      (footprint "eagle-import:TO92-DGS")
      (libsource (lib "eagle-import") (part "2N7000"))
    )
    (comp (ref "Q236")
      (value "2N7000")
      (footprint "eagle-import:TO92-DGS")
      (libsource (lib "eagle-import") (part "2N7000"))
    )
    (comp (ref "Q237")
      (value "2N7000")
      (footprint "eagle-import:TO92-DGS")
      (libsource (lib "eagle-import") (part "2N7000"))
    )
    (comp (ref "Q238")
      (value "2N7000")
      (footprint "eagle-import:TO92-DGS")
      (libsource (lib "eagle-import") (part "2N7000"))
    )
    (comp (ref "Q239")
      (value "2N7000")
      (footprint "eagle-import:TO92-DGS")
      (libsource (lib "eagle-import") (part "2N7000"))
    )
    (comp (ref "Q240")
      (value "2N7000")
      (footprint "eagle-import:TO92-DGS")
      (libsource (lib "eagle-import") (part "2N7000"))
    )
    (comp (ref "Q241")
      (value "2N7000")
      (footprint "eagle-import:TO92-DGS")
      (libsource (lib "eagle-import") (part "2N7000"))
    )
    (comp (ref "Q242")
      (value "2N7000")
      (footprint "eagle-import:TO92-DGS")
      (libsource (lib "eagle-import") (part "2N7000"))
    )
    (comp (ref "Q243")
      (value "2N7000")
      (footprint "eagle-import:TO92-DGS")
      (libsource (lib "eagle-import") (part "2N7000"))
    )
    (comp (ref "Q244")
      (value "2N7000")
      (footprint "eagle-import:TO92-DGS")
      (libsource (lib "eagle-import") (part "2N7000"))
    )
    (comp (ref "R156")
      (value "10k")
      (footprint "eagle-import:R_P2INCH")
      (libsource (lib "eagle-import") (part "R_P2INCH"))
    )
    (comp (ref "R157")
      (value "10k")
      (footprint "eagle-import:R_P2INCH")
      (libsource (lib "eagle-import") (part "R_P2INCH"))
    )
    (comp (ref "R158")
      (value "10k")
      (footprint "eagle-import:R_P2INCH")
      (libsource (lib "eagle-import") (part "R_P2INCH"))
    )
    (comp (ref "R159")
      (value "10k")
      (footprint "eagle-import:R_P2INCH")
      (libsource (lib "eagle-import") (part "R_P2INCH"))
    )
    (comp (ref "R160")
      (value "10k")
      (footprint "eagle-import:R_P2INCH")
      (libsource (lib "eagle-import") (part "R_P2INCH"))
    )
    (comp (ref "R161")
      (value "10k")
      (footprint "eagle-import:R_P2INCH")
      (libsource (lib "eagle-import") (part "R_P2INCH"))
    )
    (comp (ref "R162")
      (value "470")
      (footprint "eagle-import:R_P2INCH")
      (libsource (lib "eagle-import") (part "R_P2INCH"))
    )
    (comp (ref "R163")
      (value "10k")
      (footprint "eagle-import:R_P2INCH")
      (libsource (lib "eagle-import") (part "R_P2INCH"))
    )
    (comp (ref "R164")
      (value "10k")
      (footprint "eagle-import:R_P2INCH")
      (libsource (lib "eagle-import") (part "R_P2INCH"))
    )
    (comp (ref "D5")
      (value "L-1334SRT")
      (footprint "eagle-import:LED3MM")
      (libsource (lib "eagle-import") (part "L-1334SRT"))
    )
    (comp (ref "Q65")
      (value "2N7000")
      (footprint "eagle-import:TO92-DGS")
      (libsource (lib "eagle-import") (part "2N7000"))
    )
    (comp (ref "Q66")
      (value "2N7000")
      (footprint "eagle-import:TO92-DGS")
      (libsource (lib "eagle-import") (part "2N7000"))
    )
    (comp (ref "Q67")
      (value "2N7000")
      (footprint "eagle-import:TO92-DGS")
      (libsource (lib "eagle-import") (part "2N7000"))
    )
    (comp (ref "Q68")
      (value "2N7000")
      (footprint "eagle-import:TO92-DGS")
      (libsource (lib "eagle-import") (part "2N7000"))
    )
    (comp (ref "Q69")
      (value "2N7000")
      (footprint "eagle-import:TO92-DGS")
      (libsource (lib "eagle-import") (part "2N7000"))
    )
    (comp (ref "Q70")
      (value "2N7000")
      (footprint "eagle-import:TO92-DGS")
      (libsource (lib "eagle-import") (part "2N7000"))
    )
    (comp (ref "Q71")
      (value "2N7000")
      (footprint "eagle-import:TO92-DGS")
      (libsource (lib "eagle-import") (part "2N7000"))
    )
    (comp (ref "Q72")
      (value "2N7000")
      (footprint "eagle-import:TO92-DGS")
      (libsource (lib "eagle-import") (part "2N7000"))
    )
    (comp (ref "Q73")
      (value "2N7000")
      (footprint "eagle-import:TO92-DGS")
      (libsource (lib "eagle-import") (part "2N7000"))
    )
    (comp (ref "Q74")
      (value "2N7000")
      (footprint "eagle-import:TO92-DGS")
      (libsource (lib "eagle-import") (part "2N7000"))
    )
    (comp (ref "Q75")
      (value "2N7000")
      (footprint "eagle-import:TO92-DGS")
      (libsource (lib "eagle-import") (part "2N7000"))
    )
    (comp (ref "Q76")
      (value "2N7000")
      (footprint "eagle-import:TO92-DGS")
      (libsource (lib "eagle-import") (part "2N7000"))
    )
    (comp (ref "Q77")
      (value "2N7000")
      (footprint "eagle-import:TO92-DGS")
      (libsource (lib "eagle-import") (part "2N7000"))
    )
    (comp (ref "Q78")
      (value "2N7000")
      (footprint "eagle-import:TO92-DGS")
      (libsource (lib "eagle-import") (part "2N7000"))
    )
    (comp (ref "Q79")
      (value "2N7000")
      (footprint "eagle-import:TO92-DGS")
      (libsource (lib "eagle-import") (part "2N7000"))
    )
    (comp (ref "Q80")
      (value "2N7000")
      (footprint "eagle-import:TO92-DGS")
      (libsource (lib "eagle-import") (part "2N7000"))
    )
    (comp (ref "R53")
      (value "10k")
      (footprint "eagle-import:R_P2INCH")
      (libsource (lib "eagle-import") (part "R_P2INCH"))
    )
    (comp (ref "R54")
      (value "10k")
      (footprint "eagle-import:R_P2INCH")
      (libsource (lib "eagle-import") (part "R_P2INCH"))
    )
    (comp (ref "R55")
      (value "10k")
      (footprint "eagle-import:R_P2INCH")
      (libsource (lib "eagle-import") (part "R_P2INCH"))
    )
    (comp (ref "R56")
      (value "10k")
      (footprint "eagle-import:R_P2INCH")
      (libsource (lib "eagle-import") (part "R_P2INCH"))
    )
    (comp (ref "R57")
      (value "10k")
      (footprint "eagle-import:R_P2INCH")
      (libsource (lib "eagle-import") (part "R_P2INCH"))
    )
    (comp (ref "R58")
      (value "10k")
      (footprint "eagle-import:R_P2INCH")
      (libsource (lib "eagle-import") (part "R_P2INCH"))
    )
    (comp (ref "R59")
      (value "470")
      (footprint "eagle-import:R_P2INCH")
      (libsource (lib "eagle-import") (part "R_P2INCH"))
    )
    (comp (ref "R60")
      (value "10k")
      (footprint "eagle-import:R_P2INCH")
      (libsource (lib "eagle-import") (part "R_P2INCH"))
    )
    (comp (ref "R61")
      (value "10k")
      (footprint "eagle-import:R_P2INCH")
      (libsource (lib "eagle-import") (part "R_P2INCH"))
    )
  )
  (nets
    (net (code "1") (name "+5V") (class "Default")
      (node (ref "C1") (pin "1") (pinfunction "1_1") (pintype "passive"))
      (node (ref "C2") (pin "1") (pinfunction "1_1") (pintype "passive"))
      (node (ref "C3") (pin "1") (pinfunction "1_1") (pintype "passive"))
      (node (ref "C4") (pin "1") (pinfunction "1_1") (pintype "passive"))
      (node (ref "C5") (pin "A") (pinfunction "A_A") (pintype "passive"))
      (node (ref "C6") (pin "1") (pinfunction "1_1") (pintype "passive"))
      (node (ref "C7") (pin "1") (pinfunction "1_1") (pintype "passive"))
      (node (ref "C8") (pin "1") (pinfunction "1_1") (pintype "passive"))
      (node (ref "D1") (pin "A") (pinfunction "A_A") (pintype "passive"))
      (node (ref "D10") (pin "A") (pinfunction "A_A") (pintype "passive"))
      (node (ref "D11") (pin "A") (pinfunction "A_A") (pintype "passive"))
      (node (ref "D12") (pin "A") (pinfunction "A_A") (pintype "passive"))
      (node (ref "D13") (pin "A") (pinfunction "A_A") (pintype "passive"))
      (node (ref "D14") (pin "A") (pinfunction "A_A") (pintype "passive"))
      (node (ref "D15") (pin "A") (pinfunction "A_A") (pintype "passive"))
      (node (ref "D16") (pin "A") (pinfunction "A_A") (pintype "passive"))
      (node (ref "D17") (pin "A") (pinfunction "A_A") (pintype "passive"))
      (node (ref "D18") (pin "A") (pinfunction "A_A") (pintype "passive"))
      (node (ref "D19") (pin "A") (pinfunction "A_A") (pintype "passive"))
      (node (ref "D2") (pin "A") (pinfunction "A_A") (pintype "passive"))
      (node (ref "D20") (pin "A") (pinfunction "A_A") (pintype "passive"))
      (node (ref "D21") (pin "A") (pinfunction "A_A") (pintype "passive"))
      (node (ref "D22") (pin "A") (pinfunction "A_A") (pintype "passive"))
      (node (ref "D23") (pin "A") (pinfunction "A_A") (pintype "passive"))
      (node (ref "D24") (pin "A") (pinfunction "A_A") (pintype "passive"))
      (node (ref "D25") (pin "A") (pinfunction "A_A") (pintype "passive"))
      (node (ref "D26") (pin "A") (pinfunction "A_A") (pintype "passive"))
      (node (ref "D27") (pin "A") (pinfunction "A_A") (pintype "passive"))
      (node (ref "D28") (pin "A") (pinfunction "A_A") (pintype "passive"))
      (node (ref "D29") (pin "A") (pinfunction "A_A") (pintype "passive"))
      (node (ref "D3") (pin "A") (pinfunction "A_A") (pintype "passive"))
      (node (ref "D30") (pin "A") (pinfunction "A_A") (pintype "passive"))
      (node (ref "D31") (pin "A") (pinfunction "A_A") (pintype "passive"))
      (node (ref "D32") (pin "A") (pinfunction "A_A") (pintype "passive"))
      (node (ref "D33") (pin "A") (pinfunction "A_A") (pintype "passive"))
      (node (ref "D34") (pin "A") (pinfunction "A_A") (pintype "passive"))
      (node (ref "D4") (pin "A") (pinfunction "A_A") (pintype "passive"))
      (node (ref "D5") (pin "A") (pinfunction "A_A") (pintype "passive"))
      (node (ref "D6") (pin "A") (pinfunction "A_A") (pintype "passive"))
      (node (ref "D7") (pin "A") (pinfunction "A_A") (pintype "passive"))
      (node (ref "D8") (pin "A") (pinfunction "A_A") (pintype "passive"))
      (node (ref "D9") (pin "A") (pinfunction "A_A") (pintype "passive"))
      (node (ref "PP1") (pin "1") (pinfunction "P$1_1") (pintype "bidirectional"))
      (node (ref "R1") (pin "2") (pinfunction "2_2") (pintype "passive"))
      (node (ref "R100") (pin "2") (pinfunction "2_2") (pintype "passive"))
      (node (ref "R101") (pin "2") (pinfunction "2_2") (pintype "passive"))
      (node (ref "R102") (pin "2") (pinfunction "2_2") (pintype "passive"))
      (node (ref "R103") (pin "2") (pinfunction "2_2") (pintype "passive"))
      (node (ref "R105") (pin "2") (pinfunction "2_2") (pintype "passive"))
      (node (ref "R106") (pin "2") (pinfunction "2_2") (pintype "passive"))
      (node (ref "R107") (pin "2") (pinfunction "2_2") (pintype "passive"))
      (node (ref "R108") (pin "2") (pinfunction "2_2") (pintype "passive"))
      (node (ref "R109") (pin "2") (pinfunction "2_2") (pintype "passive"))
      (node (ref "R110") (pin "2") (pinfunction "2_2") (pintype "passive"))
      (node (ref "R111") (pin "2") (pinfunction "2_2") (pintype "passive"))
      (node (ref "R112") (pin "2") (pinfunction "2_2") (pintype "passive"))
      (node (ref "R113") (pin "2") (pinfunction "2_2") (pintype "passive"))
      (node (ref "R115") (pin "2") (pinfunction "2_2") (pintype "passive"))
      (node (ref "R132") (pin "2") (pinfunction "2_2") (pintype "passive"))
      (node (ref "R134") (pin "2") (pinfunction "2_2") (pintype "passive"))
      (node (ref "R136") (pin "2") (pinfunction "2_2") (pintype "passive"))
      (node (ref "R137") (pin "2") (pinfunction "2_2") (pintype "passive"))
      (node (ref "R138") (pin "2") (pinfunction "2_2") (pintype "passive"))
      (node (ref "R139") (pin "2") (pinfunction "2_2") (pintype "passive"))
      (node (ref "R140") (pin "2") (pinfunction "2_2") (pintype "passive"))
      (node (ref "R141") (pin "2") (pinfunction "2_2") (pintype "passive"))
      (node (ref "R142") (pin "2") (pinfunction "2_2") (pintype "passive"))
      (node (ref "R143") (pin "2") (pinfunction "2_2") (pintype "passive"))
      (node (ref "R145") (pin "2") (pinfunction "2_2") (pintype "passive"))
      (node (ref "R146") (pin "2") (pinfunction "2_2") (pintype "passive"))
      (node (ref "R147") (pin "2") (pinfunction "2_2") (pintype "passive"))
      (node (ref "R148") (pin "2") (pinfunction "2_2") (pintype "passive"))
      (node (ref "R149") (pin "2") (pinfunction "2_2") (pintype "passive"))
      (node (ref "R150") (pin "2") (pinfunction "2_2") (pintype "passive"))
      (node (ref "R151") (pin "2") (pinfunction "2_2") (pintype "passive"))
      (node (ref "R152") (pin "2") (pinfunction "2_2") (pintype "passive"))
      (node (ref "R154") (pin "2") (pinfunction "2_2") (pintype "passive"))
      (node (ref "R155") (pin "2") (pinfunction "2_2") (pintype "passive"))
      (node (ref "R156") (pin "2") (pinfunction "2_2") (pintype "passive"))
      (node (ref "R157") (pin "2") (pinfunction "2_2") (pintype "passive"))
      (node (ref "R158") (pin "2") (pinfunction "2_2") (pintype "passive"))
      (node (ref "R159") (pin "2") (pinfunction "2_2") (pintype "passive"))
      (node (ref "R160") (pin "2") (pinfunction "2_2") (pintype "passive"))
      (node (ref "R161") (pin "2") (pinfunction "2_2") (pintype "passive"))
      (node (ref "R163") (pin "2") (pinfunction "2_2") (pintype "passive"))
      (node (ref "R164") (pin "2") (pinfunction "2_2") (pintype "passive"))
      (node (ref "R165") (pin "2") (pinfunction "2_2") (pintype "passive"))
      (node (ref "R166") (pin "2") (pinfunction "2_2") (pintype "passive"))
      (node (ref "R167") (pin "2") (pinfunction "2_2") (pintype "passive"))
      (node (ref "R168") (pin "2") (pinfunction "2_2") (pintype "passive"))
      (node (ref "R169") (pin "2") (pinfunction "2_2") (pintype "passive"))
      (node (ref "R170") (pin "2") (pinfunction "2_2") (pintype "passive"))
      (node (ref "R172") (pin "2") (pinfunction "2_2") (pintype "passive"))
      (node (ref "R173") (pin "2") (pinfunction "2_2") (pintype "passive"))
      (node (ref "R174") (pin "2") (pinfunction "2_2") (pintype "passive"))
      (node (ref "R175") (pin "2") (pinfunction "2_2") (pintype "passive"))
      (node (ref "R176") (pin "2") (pinfunction "2_2") (pintype "passive"))
      (node (ref "R177") (pin "2") (pinfunction "2_2") (pintype "passive"))
      (node (ref "R178") (pin "2") (pinfunction "2_2") (pintype "passive"))
      (node (ref "R179") (pin "2") (pinfunction "2_2") (pintype "passive"))
      (node (ref "R181") (pin "2") (pinfunction "2_2") (pintype "passive"))
      (node (ref "R182") (pin "2") (pinfunction "2_2") (pintype "passive"))
      (node (ref "R2") (pin "2") (pinfunction "2_2") (pintype "passive"))
      (node (ref "R26") (pin "2") (pinfunction "2_2") (pintype "passive"))
      (node (ref "R27") (pin "2") (pinfunction "2_2") (pintype "passive"))
      (node (ref "R28") (pin "2") (pinfunction "2_2") (pintype "passive"))
      (node (ref "R29") (pin "2") (pinfunction "2_2") (pintype "passive"))
      (node (ref "R3") (pin "2") (pinfunction "2_2") (pintype "passive"))
      (node (ref "R30") (pin "2") (pinfunction "2_2") (pintype "passive"))
      (node (ref "R31") (pin "2") (pinfunction "2_2") (pintype "passive"))
      (node (ref "R33") (pin "2") (pinfunction "2_2") (pintype "passive"))
      (node (ref "R34") (pin "2") (pinfunction "2_2") (pintype "passive"))
      (node (ref "R35") (pin "2") (pinfunction "2_2") (pintype "passive"))
      (node (ref "R36") (pin "2") (pinfunction "2_2") (pintype "passive"))
      (node (ref "R37") (pin "2") (pinfunction "2_2") (pintype "passive"))
      (node (ref "R38") (pin "2") (pinfunction "2_2") (pintype "passive"))
      (node (ref "R39") (pin "2") (pinfunction "2_2") (pintype "passive"))
      (node (ref "R4") (pin "2") (pinfunction "2_2") (pintype "passive"))
      (node (ref "R40") (pin "2") (pinfunction "2_2") (pintype "passive"))
      (node (ref "R42") (pin "2") (pinfunction "2_2") (pintype "passive"))
      (node (ref "R43") (pin "2") (pinfunction "2_2") (pintype "passive"))
      (node (ref "R44") (pin "2") (pinfunction "2_2") (pintype "passive"))
      (node (ref "R45") (pin "2") (pinfunction "2_2") (pintype "passive"))
      (node (ref "R46") (pin "2") (pinfunction "2_2") (pintype "passive"))
      (node (ref "R47") (pin "2") (pinfunction "2_2") (pintype "passive"))
      (node (ref "R48") (pin "2") (pinfunction "2_2") (pintype "passive"))
      (node (ref "R49") (pin "2") (pinfunction "2_2") (pintype "passive"))
      (node (ref "R5") (pin "2") (pinfunction "2_2") (pintype "passive"))
      (node (ref "R51") (pin "2") (pinfunction "2_2") (pintype "passive"))
      (node (ref "R52") (pin "2") (pinfunction "2_2") (pintype "passive"))
      (node (ref "R53") (pin "2") (pinfunction "2_2") (pintype "passive"))
      (node (ref "R54") (pin "2") (pinfunction "2_2") (pintype "passive"))
      (node (ref "R55") (pin "2") (pinfunction "2_2") (pintype "passive"))
      (node (ref "R56") (pin "2") (pinfunction "2_2") (pintype "passive"))
      (node (ref "R57") (pin "2") (pinfunction "2_2") (pintype "passive"))
      (node (ref "R58") (pin "2") (pinfunction "2_2") (pintype "passive"))
      (node (ref "R6") (pin "2") (pinfunction "2_2") (pintype "passive"))
      (node (ref "R60") (pin "2") (pinfunction "2_2") (pintype "passive"))
      (node (ref "R61") (pin "2") (pinfunction "2_2") (pintype "passive"))
      (node (ref "R62") (pin "2") (pinfunction "2_2") (pintype "passive"))
      (node (ref "R63") (pin "2") (pinfunction "2_2") (pintype "passive"))
      (node (ref "R64") (pin "2") (pinfunction "2_2") (pintype "passive"))
      (node (ref "R65") (pin "2") (pinfunction "2_2") (pintype "passive"))
      (node (ref "R66") (pin "2") (pinfunction "2_2") (pintype "passive"))
      (node (ref "R67") (pin "2") (pinfunction "2_2") (pintype "passive"))
      (node (ref "R69") (pin "2") (pinfunction "2_2") (pintype "passive"))
      (node (ref "R70") (pin "2") (pinfunction "2_2") (pintype "passive"))
      (node (ref "R71") (pin "2") (pinfunction "2_2") (pintype "passive"))
      (node (ref "R72") (pin "2") (pinfunction "2_2") (pintype "passive"))
      (node (ref "R73") (pin "2") (pinfunction "2_2") (pintype "passive"))
      (node (ref "R74") (pin "2") (pinfunction "2_2") (pintype "passive"))
      (node (ref "R75") (pin "2") (pinfunction "2_2") (pintype "passive"))
      (node (ref "R76") (pin "2") (pinfunction "2_2") (pintype "passive"))
      (node (ref "R78") (pin "2") (pinfunction "2_2") (pintype "passive"))
      (node (ref "R79") (pin "2") (pinfunction "2_2") (pintype "passive"))
      (node (ref "R8") (pin "2") (pinfunction "2_2") (pintype "passive"))
      (node (ref "R80") (pin "2") (pinfunction "2_2") (pintype "passive"))
      (node (ref "R81") (pin "2") (pinfunction "2_2") (pintype "passive"))
      (node (ref "R82") (pin "2") (pinfunction "2_2") (pintype "passive"))
      (node (ref "R83") (pin "2") (pinfunction "2_2") (pintype "passive"))
      (node (ref "R84") (pin "2") (pinfunction "2_2") (pintype "passive"))
      (node (ref "R85") (pin "2") (pinfunction "2_2") (pintype "passive"))
      (node (ref "R87") (pin "2") (pinfunction "2_2") (pintype "passive"))
      (node (ref "R88") (pin "2") (pinfunction "2_2") (pintype "passive"))
      (node (ref "R89") (pin "2") (pinfunction "2_2") (pintype "passive"))
      (node (ref "R9") (pin "2") (pinfunction "2_2") (pintype "passive"))
      (node (ref "R90") (pin "2") (pinfunction "2_2") (pintype "passive"))
      (node (ref "R91") (pin "2") (pinfunction "2_2") (pintype "passive"))
      (node (ref "R92") (pin "2") (pinfunction "2_2") (pintype "passive"))
      (node (ref "R93") (pin "2") (pinfunction "2_2") (pintype "passive"))
      (node (ref "R94") (pin "2") (pinfunction "2_2") (pintype "passive"))
      (node (ref "R96") (pin "2") (pinfunction "2_2") (pintype "passive"))
      (node (ref "R97") (pin "2") (pinfunction "2_2") (pintype "passive"))
      (node (ref "R98") (pin "2") (pinfunction "2_2") (pintype "passive"))
      (node (ref "R99") (pin "2") (pinfunction "2_2") (pintype "passive"))
    )
    (net (code "2") (name "CK1") (class "Default")
      (node (ref "Q1") (pin "G") (pinfunction "G_G") (pintype "passive"))
      (node (ref "Q113") (pin "G") (pinfunction "G_G") (pintype "passive"))
      (node (ref "Q115") (pin "G") (pinfunction "G_G") (pintype "passive"))
      (node (ref "Q129") (pin "G") (pinfunction "G_G") (pintype "passive"))
      (node (ref "Q131") (pin "G") (pinfunction "G_G") (pintype "passive"))
      (node (ref "Q145") (pin "G") (pinfunction "G_G") (pintype "passive"))
      (node (ref "Q147") (pin "G") (pinfunction "G_G") (pintype "passive"))
      (node (ref "Q161") (pin "G") (pinfunction "G_G") (pintype "passive"))
      (node (ref "Q163") (pin "G") (pinfunction "G_G") (pintype "passive"))
      (node (ref "Q17") (pin "G") (pinfunction "G_G") (pintype "passive"))
      (node (ref "Q177") (pin "G") (pinfunction "G_G") (pintype "passive"))
      (node (ref "Q179") (pin "G") (pinfunction "G_G") (pintype "passive"))
      (node (ref "Q19") (pin "G") (pinfunction "G_G") (pintype "passive"))
      (node (ref "Q193") (pin "G") (pinfunction "G_G") (pintype "passive"))
      (node (ref "Q195") (pin "G") (pinfunction "G_G") (pintype "passive"))
      (node (ref "Q210") (pin "D") (pinfunction "D_D") (pintype "passive"))
      (node (ref "Q229") (pin "G") (pinfunction "G_G") (pintype "passive"))
      (node (ref "Q231") (pin "G") (pinfunction "G_G") (pintype "passive"))
      (node (ref "Q245") (pin "G") (pinfunction "G_G") (pintype "passive"))
      (node (ref "Q247") (pin "G") (pinfunction "G_G") (pintype "passive"))
      (node (ref "Q261") (pin "G") (pinfunction "G_G") (pintype "passive"))
      (node (ref "Q263") (pin "G") (pinfunction "G_G") (pintype "passive"))
      (node (ref "Q3") (pin "G") (pinfunction "G_G") (pintype "passive"))
      (node (ref "Q33") (pin "G") (pinfunction "G_G") (pintype "passive"))
      (node (ref "Q35") (pin "G") (pinfunction "G_G") (pintype "passive"))
      (node (ref "Q49") (pin "G") (pinfunction "G_G") (pintype "passive"))
      (node (ref "Q51") (pin "G") (pinfunction "G_G") (pintype "passive"))
      (node (ref "Q65") (pin "G") (pinfunction "G_G") (pintype "passive"))
      (node (ref "Q67") (pin "G") (pinfunction "G_G") (pintype "passive"))
      (node (ref "Q81") (pin "G") (pinfunction "G_G") (pintype "passive"))
      (node (ref "Q83") (pin "G") (pinfunction "G_G") (pintype "passive"))
      (node (ref "Q97") (pin "G") (pinfunction "G_G") (pintype "passive"))
      (node (ref "Q99") (pin "G") (pinfunction "G_G") (pintype "passive"))
      (node (ref "R115") (pin "1") (pinfunction "1_1") (pintype "passive"))
    )
    (net (code "3") (name "CK2") (class "Default")
      (node (ref "Q109") (pin "G") (pinfunction "G_G") (pintype "passive"))
      (node (ref "Q111") (pin "G") (pinfunction "G_G") (pintype "passive"))
      (node (ref "Q125") (pin "G") (pinfunction "G_G") (pintype "passive"))
      (node (ref "Q127") (pin "G") (pinfunction "G_G") (pintype "passive"))
      (node (ref "Q141") (pin "G") (pinfunction "G_G") (pintype "passive"))
      (node (ref "Q143") (pin "G") (pinfunction "G_G") (pintype "passive"))
      (node (ref "Q15") (pin "G") (pinfunction "G_G") (pintype "passive"))
      (node (ref "Q157") (pin "G") (pinfunction "G_G") (pintype "passive"))
      (node (ref "Q159") (pin "G") (pinfunction "G_G") (pintype "passive"))
      (node (ref "Q173") (pin "G") (pinfunction "G_G") (pintype "passive"))
      (node (ref "Q175") (pin "G") (pinfunction "G_G") (pintype "passive"))
      (node (ref "Q189") (pin "G") (pinfunction "G_G") (pintype "passive"))
      (node (ref "Q191") (pin "G") (pinfunction "G_G") (pintype "passive"))
      (node (ref "Q205") (pin "G") (pinfunction "G_G") (pintype "passive"))
      (node (ref "Q207") (pin "G") (pinfunction "G_G") (pintype "passive"))
      (node (ref "Q228") (pin "D") (pinfunction "D_D") (pintype "passive"))
      (node (ref "Q241") (pin "G") (pinfunction "G_G") (pintype "passive"))
      (node (ref "Q243") (pin "G") (pinfunction "G_G") (pintype "passive"))
      (node (ref "Q257") (pin "G") (pinfunction "G_G") (pintype "passive"))
      (node (ref "Q259") (pin "G") (pinfunction "G_G") (pintype "passive"))
      (node (ref "Q273") (pin "G") (pinfunction "G_G") (pintype "passive"))
      (node (ref "Q275") (pin "G") (pinfunction "G_G") (pintype "passive"))
      (node (ref "Q29") (pin "G") (pinfunction "G_G") (pintype "passive"))
      (node (ref "Q31") (pin "G") (pinfunction "G_G") (pintype "passive"))
      (node (ref "Q45") (pin "G") (pinfunction "G_G") (pintype "passive"))
      (node (ref "Q47") (pin "G") (pinfunction "G_G") (pintype "passive"))
      (node (ref "Q61") (pin "G") (pinfunction "G_G") (pintype "passive"))
      (node (ref "Q63") (pin "G") (pinfunction "G_G") (pintype "passive"))
      (node (ref "Q7") (pin "G") (pinfunction "G_G") (pintype "passive"))
      (node (ref "Q77") (pin "G") (pinfunction "G_G") (pintype "passive"))
      (node (ref "Q79") (pin "G") (pinfunction "G_G") (pintype "passive"))
      (node (ref "Q93") (pin "G") (pinfunction "G_G") (pintype "passive"))
      (node (ref "Q95") (pin "G") (pinfunction "G_G") (pintype "passive"))
      (node (ref "R134") (pin "1") (pinfunction "1_1") (pintype "passive"))
    )
    (net (code "4") (name "D0") (class "Default")
      (node (ref "J1") (pin "2") (pinfunction "2_2") (pintype "bidirectional"))
      (node (ref "Q2") (pin "G") (pinfunction "G_G") (pintype "passive"))
      (node (ref "Q211") (pin "G") (pinfunction "G_G") (pintype "passive"))
    )
    (net (code "5") (name "D0_N") (class "Default")
      (node (ref "Q211") (pin "D") (pinfunction "D_D") (pintype "passive"))
      (node (ref "R117") (pin "1") (pinfunction "1_1") (pintype "passive"))
    )
    (net (code "6") (name "D1") (class "Default")
      (node (ref "J1") (pin "3") (pinfunction "3_3") (pintype "bidirectional"))
      (node (ref "Q18") (pin "G") (pinfunction "G_G") (pintype "passive"))
      (node (ref "Q212") (pin "G") (pinfunction "G_G") (pintype "passive"))
    )
    (net (code "7") (name "D1_N") (class "Default")
      (node (ref "Q212") (pin "D") (pinfunction "D_D") (pintype "passive"))
      (node (ref "R119") (pin "1") (pinfunction "1_1") (pintype "passive"))
    )
    (net (code "8") (name "D2") (class "Default")
      (node (ref "J1") (pin "4") (pinfunction "4_4") (pintype "bidirectional"))
      (node (ref "Q213") (pin "G") (pinfunction "G_G") (pintype "passive"))
      (node (ref "Q34") (pin "G") (pinfunction "G_G") (pintype "passive"))
    )
    (net (code "9") (name "D2_N") (class "Default")
      (node (ref "Q213") (pin "D") (pinfunction "D_D") (pintype "passive"))
      (node (ref "R121") (pin "1") (pinfunction "1_1") (pintype "passive"))
    )
    (net (code "10") (name "D3") (class "Default")
      (node (ref "J1") (pin "5") (pinfunction "5_5") (pintype "bidirectional"))
      (node (ref "Q214") (pin "G") (pinfunction "G_G") (pintype "passive"))
      (node (ref "Q50") (pin "G") (pinfunction "G_G") (pintype "passive"))
    )
    (net (code "11") (name "D3_N") (class "Default")
      (node (ref "Q214") (pin "D") (pinfunction "D_D") (pintype "passive"))
      (node (ref "R123") (pin "1") (pinfunction "1_1") (pintype "passive"))
    )
    (net (code "12") (name "D4") (class "Default")
      (node (ref "J1") (pin "6") (pinfunction "6_6") (pintype "bidirectional"))
      (node (ref "Q215") (pin "G") (pinfunction "G_G") (pintype "passive"))
      (node (ref "Q66") (pin "G") (pinfunction "G_G") (pintype "passive"))
    )
    (net (code "13") (name "D4_N") (class "Default")
      (node (ref "Q215") (pin "D") (pinfunction "D_D") (pintype "passive"))
      (node (ref "R125") (pin "1") (pinfunction "1_1") (pintype "passive"))
    )
    (net (code "14") (name "D5") (class "Default")
      (node (ref "J1") (pin "7") (pinfunction "7_7") (pintype "bidirectional"))
      (node (ref "Q216") (pin "G") (pinfunction "G_G") (pintype "passive"))
      (node (ref "Q82") (pin "G") (pinfunction "G_G") (pintype "passive"))
    )
    (net (code "15") (name "D5_N") (class "Default")
      (node (ref "Q216") (pin "D") (pinfunction "D_D") (pintype "passive"))
      (node (ref "R127") (pin "1") (pinfunction "1_1") (pintype "passive"))
    )
    (net (code "16") (name "D6") (class "Default")
      (node (ref "J1") (pin "8") (pinfunction "8_8") (pintype "bidirectional"))
      (node (ref "Q217") (pin "G") (pinfunction "G_G") (pintype "passive"))
      (node (ref "Q98") (pin "G") (pinfunction "G_G") (pintype "passive"))
    )
    (net (code "17") (name "D6_N") (class "Default")
      (node (ref "Q217") (pin "D") (pinfunction "D_D") (pintype "passive"))
      (node (ref "R129") (pin "1") (pinfunction "1_1") (pintype "passive"))
    )
    (net (code "18") (name "D7") (class "Default")
      (node (ref "J1") (pin "9") (pinfunction "9_9") (pintype "bidirectional"))
      (node (ref "Q114") (pin "G") (pinfunction "G_G") (pintype "passive"))
      (node (ref "Q218") (pin "G") (pinfunction "G_G") (pintype "passive"))
    )
    (net (code "19") (name "D7_N") (class "Default")
      (node (ref "Q218") (pin "D") (pinfunction "D_D") (pintype "passive"))
      (node (ref "R131") (pin "1") (pinfunction "1_1") (pintype "passive"))
    )
    (net (code "20") (name "D8") (class "Default")
      (node (ref "J1") (pin "12") (pinfunction "12_12") (pintype "bidirectional"))
      (node (ref "Q130") (pin "G") (pinfunction "G_G") (pintype "passive"))
      (node (ref "Q219") (pin "G") (pinfunction "G_G") (pintype "passive"))
    )
    (net (code "21") (name "D8_N") (class "Default")
      (node (ref "Q219") (pin "D") (pinfunction "D_D") (pintype "passive"))
      (node (ref "R116") (pin "1") (pinfunction "1_1") (pintype "passive"))
    )
    (net (code "22") (name "D9") (class "Default")
      (node (ref "J1") (pin "13") (pinfunction "13_13") (pintype "bidirectional"))
      (node (ref "Q146") (pin "G") (pinfunction "G_G") (pintype "passive"))
      (node (ref "Q220") (pin "G") (pinfunction "G_G") (pintype "passive"))
    )
    (net (code "23") (name "D9_N") (class "Default")
      (node (ref "Q220") (pin "D") (pinfunction "D_D") (pintype "passive"))
      (node (ref "R118") (pin "1") (pinfunction "1_1") (pintype "passive"))
    )
    (net (code "24") (name "D10") (class "Default")
      (node (ref "J1") (pin "14") (pinfunction "14_14") (pintype "bidirectional"))
      (node (ref "Q162") (pin "G") (pinfunction "G_G") (pintype "passive"))
      (node (ref "Q221") (pin "G") (pinfunction "G_G") (pintype "passive"))
    )
    (net (code "25") (name "D10_N") (class "Default")
      (node (ref "Q221") (pin "D") (pinfunction "D_D") (pintype "passive"))
      (node (ref "R120") (pin "1") (pinfunction "1_1") (pintype "passive"))
    )
    (net (code "26") (name "D11") (class "Default")
      (node (ref "J1") (pin "15") (pinfunction "15_15") (pintype "bidirectional"))
      (node (ref "Q178") (pin "G") (pinfunction "G_G") (pintype "passive"))
      (node (ref "Q222") (pin "G") (pinfunction "G_G") (pintype "passive"))
    )
    (net (code "27") (name "D11_N") (class "Default")
      (node (ref "Q222") (pin "D") (pinfunction "D_D") (pintype "passive"))
      (node (ref "R122") (pin "1") (pinfunction "1_1") (pintype "passive"))
    )
    (net (code "28") (name "D12") (class "Default")
      (node (ref "J1") (pin "16") (pinfunction "16_16") (pintype "bidirectional"))
      (node (ref "Q194") (pin "G") (pinfunction "G_G") (pintype "passive"))
      (node (ref "Q223") (pin "G") (pinfunction "G_G") (pintype "passive"))
    )
    (net (code "29") (name "D12_N") (class "Default")
      (node (ref "Q223") (pin "D") (pinfunction "D_D") (pintype "passive"))
      (node (ref "R124") (pin "1") (pinfunction "1_1") (pintype "passive"))
    )
    (net (code "30") (name "D13") (class "Default")
      (node (ref "J1") (pin "17") (pinfunction "17_17") (pintype "bidirectional"))
      (node (ref "Q224") (pin "G") (pinfunction "G_G") (pintype "passive"))
      (node (ref "Q230") (pin "G") (pinfunction "G_G") (pintype "passive"))
    )
    (net (code "31") (name "D13_N") (class "Default")
      (node (ref "Q224") (pin "D") (pinfunction "D_D") (pintype "passive"))
      (node (ref "R126") (pin "1") (pinfunction "1_1") (pintype "passive"))
    )
    (net (code "32") (name "D14") (class "Default")
      (node (ref "J1") (pin "18") (pinfunction "18_18") (pintype "bidirectional"))
      (node (ref "Q225") (pin "G") (pinfunction "G_G") (pintype "passive"))
      (node (ref "Q246") (pin "G") (pinfunction "G_G") (pintype "passive"))
    )
    (net (code "33") (name "D14_N") (class "Default")
      (node (ref "Q225") (pin "D") (pinfunction "D_D") (pintype "passive"))
      (node (ref "R128") (pin "1") (pinfunction "1_1") (pintype "passive"))
    )
    (net (code "34") (name "D15") (class "Default")
      (node (ref "J1") (pin "19") (pinfunction "19_19") (pintype "bidirectional"))
      (node (ref "Q226") (pin "G") (pinfunction "G_G") (pintype "passive"))
      (node (ref "Q262") (pin "G") (pinfunction "G_G") (pintype "passive"))
    )
    (net (code "35") (name "D15_N") (class "Default")
      (node (ref "Q226") (pin "D") (pinfunction "D_D") (pintype "passive"))
      (node (ref "R130") (pin "1") (pinfunction "1_1") (pintype "passive"))
    )
    (net (code "36") (name "GND") (class "Default")
      (node (ref "C1") (pin "2") (pinfunction "2_2") (pintype "passive"))
      (node (ref "C2") (pin "2") (pinfunction "2_2") (pintype "passive"))
      (node (ref "C3") (pin "2") (pinfunction "2_2") (pintype "passive"))
      (node (ref "C4") (pin "2") (pinfunction "2_2") (pintype "passive"))
      (node (ref "C5") (pin "K") (pinfunction "K_K") (pintype "passive"))
      (node (ref "C6") (pin "2") (pinfunction "2_2") (pintype "passive"))
      (node (ref "C7") (pin "2") (pinfunction "2_2") (pintype "passive"))
      (node (ref "C8") (pin "2") (pinfunction "2_2") (pintype "passive"))
      (node (ref "J1") (pin "1") (pinfunction "1_1") (pintype "bidirectional"))
      (node (ref "J1") (pin "10") (pinfunction "10_10") (pintype "bidirectional"))
      (node (ref "J1") (pin "11") (pinfunction "11_11") (pintype "bidirectional"))
      (node (ref "J1") (pin "20") (pinfunction "20_20") (pintype "bidirectional"))
      (node (ref "J2") (pin "1") (pinfunction "1_1") (pintype "bidirectional"))
      (node (ref "J2") (pin "10") (pinfunction "10_10") (pintype "bidirectional"))
      (node (ref "J2") (pin "11") (pinfunction "11_11") (pintype "bidirectional"))
      (node (ref "J2") (pin "20") (pinfunction "20_20") (pintype "bidirectional"))
      (node (ref "J3") (pin "1") (pinfunction "1_1") (pintype "bidirectional"))
      (node (ref "J3") (pin "10") (pinfunction "10_10") (pintype "bidirectional"))
      (node (ref "J3") (pin "19") (pinfunction "19_19") (pintype "bidirectional"))
      (node (ref "J3") (pin "28") (pinfunction "28_28") (pintype "bidirectional"))
      (node (ref "PP2") (pin "1") (pinfunction "P$1_1") (pintype "bidirectional"))
      (node (ref "Q1") (pin "S") (pinfunction "S_S") (pintype "passive"))
      (node (ref "Q10") (pin "S") (pinfunction "S_S") (pintype "passive"))
      (node (ref "Q101") (pin "S") (pinfunction "S_S") (pintype "passive"))
      (node (ref "Q103") (pin "S") (pinfunction "S_S") (pintype "passive"))
      (node (ref "Q105") (pin "S") (pinfunction "S_S") (pintype "passive"))
      (node (ref "Q107") (pin "S") (pinfunction "S_S") (pintype "passive"))
      (node (ref "Q109") (pin "S") (pinfunction "S_S") (pintype "passive"))
      (node (ref "Q111") (pin "S") (pinfunction "S_S") (pintype "passive"))
      (node (ref "Q113") (pin "S") (pinfunction "S_S") (pintype "passive"))
      (node (ref "Q115") (pin "S") (pinfunction "S_S") (pintype "passive"))
      (node (ref "Q117") (pin "S") (pinfunction "S_S") (pintype "passive"))
      (node (ref "Q119") (pin "S") (pinfunction "S_S") (pintype "passive"))
      (node (ref "Q12") (pin "S") (pinfunction "S_S") (pintype "passive"))
      (node (ref "Q121") (pin "S") (pinfunction "S_S") (pintype "passive"))
      (node (ref "Q123") (pin "S") (pinfunction "S_S") (pintype "passive"))
      (node (ref "Q125") (pin "S") (pinfunction "S_S") (pintype "passive"))
      (node (ref "Q127") (pin "S") (pinfunction "S_S") (pintype "passive"))
      (node (ref "Q129") (pin "S") (pinfunction "S_S") (pintype "passive"))
      (node (ref "Q131") (pin "S") (pinfunction "S_S") (pintype "passive"))
      (node (ref "Q133") (pin "S") (pinfunction "S_S") (pintype "passive"))
      (node (ref "Q135") (pin "S") (pinfunction "S_S") (pintype "passive"))
      (node (ref "Q137") (pin "S") (pinfunction "S_S") (pintype "passive"))
      (node (ref "Q139") (pin "S") (pinfunction "S_S") (pintype "passive"))
      (node (ref "Q141") (pin "S") (pinfunction "S_S") (pintype "passive"))
      (node (ref "Q143") (pin "S") (pinfunction "S_S") (pintype "passive"))
      (node (ref "Q145") (pin "S") (pinfunction "S_S") (pintype "passive"))
      (node (ref "Q147") (pin "S") (pinfunction "S_S") (pintype "passive"))
      (node (ref "Q149") (pin "S") (pinfunction "S_S") (pintype "passive"))
      (node (ref "Q15") (pin "S") (pinfunction "S_S") (pintype "passive"))
      (node (ref "Q151") (pin "S") (pinfunction "S_S") (pintype "passive"))
      (node (ref "Q153") (pin "S") (pinfunction "S_S") (pintype "passive"))
      (node (ref "Q155") (pin "S") (pinfunction "S_S") (pintype "passive"))
      (node (ref "Q157") (pin "S") (pinfunction "S_S") (pintype "passive"))
      (node (ref "Q159") (pin "S") (pinfunction "S_S") (pintype "passive"))
      (node (ref "Q161") (pin "S") (pinfunction "S_S") (pintype "passive"))
      (node (ref "Q163") (pin "S") (pinfunction "S_S") (pintype "passive"))
      (node (ref "Q165") (pin "S") (pinfunction "S_S") (pintype "passive"))
      (node (ref "Q167") (pin "S") (pinfunction "S_S") (pintype "passive"))
      (node (ref "Q169") (pin "S") (pinfunction "S_S") (pintype "passive"))
      (node (ref "Q17") (pin "S") (pinfunction "S_S") (pintype "passive"))
      (node (ref "Q171") (pin "S") (pinfunction "S_S") (pintype "passive"))
      (node (ref "Q173") (pin "S") (pinfunction "S_S") (pintype "passive"))
      (node (ref "Q175") (pin "S") (pinfunction "S_S") (pintype "passive"))
      (node (ref "Q177") (pin "S") (pinfunction "S_S") (pintype "passive"))
      (node (ref "Q179") (pin "S") (pinfunction "S_S") (pintype "passive"))
      (node (ref "Q181") (pin "S") (pinfunction "S_S") (pintype "passive"))
      (node (ref "Q183") (pin "S") (pinfunction "S_S") (pintype "passive"))
      (node (ref "Q185") (pin "S") (pinfunction "S_S") (pintype "passive"))
      (node (ref "Q187") (pin "S") (pinfunction "S_S") (pintype "passive"))
      (node (ref "Q189") (pin "S") (pinfunction "S_S") (pintype "passive"))
      (node (ref "Q19") (pin "S") (pinfunction "S_S") (pintype "passive"))
      (node (ref "Q191") (pin "S") (pinfunction "S_S") (pintype "passive"))
      (node (ref "Q193") (pin "S") (pinfunction "S_S") (pintype "passive"))
      (node (ref "Q195") (pin "S") (pinfunction "S_S") (pintype "passive"))
      (node (ref "Q197") (pin "S") (pinfunction "S_S") (pintype "passive"))
      (node (ref "Q199") (pin "S") (pinfunction "S_S") (pintype "passive"))
      (node (ref "Q201") (pin "S") (pinfunction "S_S") (pintype "passive"))
      (node (ref "Q203") (pin "S") (pinfunction "S_S") (pintype "passive"))
      (node (ref "Q205") (pin "S") (pinfunction "S_S") (pintype "passive"))
      (node (ref "Q207") (pin "S") (pinfunction "S_S") (pintype "passive"))
      (node (ref "Q209") (pin "S") (pinfunction "S_S") (pintype "passive"))
      (node (ref "Q21") (pin "S") (pinfunction "S_S") (pintype "passive"))
      (node (ref "Q210") (pin "S") (pinfunction "S_S") (pintype "passive"))
      (node (ref "Q211") (pin "S") (pinfunction "S_S") (pintype "passive"))
      (node (ref "Q212") (pin "S") (pinfunction "S_S") (pintype "passive"))
      (node (ref "Q213") (pin "S") (pinfunction "S_S") (pintype "passive"))
      (node (ref "Q214") (pin "S") (pinfunction "S_S") (pintype "passive"))
      (node (ref "Q215") (pin "S") (pinfunction "S_S") (pintype "passive"))
      (node (ref "Q216") (pin "S") (pinfunction "S_S") (pintype "passive"))
      (node (ref "Q217") (pin "S") (pinfunction "S_S") (pintype "passive"))
      (node (ref "Q218") (pin "S") (pinfunction "S_S") (pintype "passive"))
      (node (ref "Q219") (pin "S") (pinfunction "S_S") (pintype "passive"))
      (node (ref "Q220") (pin "S") (pinfunction "S_S") (pintype "passive"))
      (node (ref "Q221") (pin "S") (pinfunction "S_S") (pintype "passive"))
      (node (ref "Q222") (pin "S") (pinfunction "S_S") (pintype "passive"))
      (node (ref "Q223") (pin "S") (pinfunction "S_S") (pintype "passive"))
      (node (ref "Q224") (pin "S") (pinfunction "S_S") (pintype "passive"))
      (node (ref "Q225") (pin "S") (pinfunction "S_S") (pintype "passive"))
      (node (ref "Q226") (pin "S") (pinfunction "S_S") (pintype "passive"))
      (node (ref "Q227") (pin "S") (pinfunction "S_S") (pintype "passive"))
      (node (ref "Q228") (pin "S") (pinfunction "S_S") (pintype "passive"))
      (node (ref "Q229") (pin "S") (pinfunction "S_S") (pintype "passive"))
      (node (ref "Q23") (pin "S") (pinfunction "S_S") (pintype "passive"))
      (node (ref "Q231") (pin "S") (pinfunction "S_S") (pintype "passive"))
      (node (ref "Q233") (pin "S") (pinfunction "S_S") (pintype "passive"))
      (node (ref "Q235") (pin "S") (pinfunction "S_S") (pintype "passive"))
      (node (ref "Q237") (pin "S") (pinfunction "S_S") (pintype "passive"))
      (node (ref "Q239") (pin "S") (pinfunction "S_S") (pintype "passive"))
      (node (ref "Q241") (pin "S") (pinfunction "S_S") (pintype "passive"))
      (node (ref "Q243") (pin "S") (pinfunction "S_S") (pintype "passive"))
      (node (ref "Q245") (pin "S") (pinfunction "S_S") (pintype "passive"))
      (node (ref "Q247") (pin "S") (pinfunction "S_S") (pintype "passive"))
      (node (ref "Q249") (pin "S") (pinfunction "S_S") (pintype "passive"))
      (node (ref "Q25") (pin "S") (pinfunction "S_S") (pintype "passive"))
      (node (ref "Q251") (pin "S") (pinfunction "S_S") (pintype "passive"))
      (node (ref "Q253") (pin "S") (pinfunction "S_S") (pintype "passive"))
      (node (ref "Q255") (pin "S") (pinfunction "S_S") (pintype "passive"))
      (node (ref "Q257") (pin "S") (pinfunction "S_S") (pintype "passive"))
      (node (ref "Q259") (pin "S") (pinfunction "S_S") (pintype "passive"))
      (node (ref "Q261") (pin "S") (pinfunction "S_S") (pintype "passive"))
      (node (ref "Q263") (pin "S") (pinfunction "S_S") (pintype "passive"))
      (node (ref "Q265") (pin "S") (pinfunction "S_S") (pintype "passive"))
      (node (ref "Q267") (pin "S") (pinfunction "S_S") (pintype "passive"))
      (node (ref "Q269") (pin "S") (pinfunction "S_S") (pintype "passive"))
      (node (ref "Q27") (pin "S") (pinfunction "S_S") (pintype "passive"))
      (node (ref "Q271") (pin "S") (pinfunction "S_S") (pintype "passive"))
      (node (ref "Q273") (pin "S") (pinfunction "S_S") (pintype "passive"))
      (node (ref "Q275") (pin "S") (pinfunction "S_S") (pintype "passive"))
      (node (ref "Q29") (pin "S") (pinfunction "S_S") (pintype "passive"))
      (node (ref "Q3") (pin "S") (pinfunction "S_S") (pintype "passive"))
      (node (ref "Q31") (pin "S") (pinfunction "S_S") (pintype "passive"))
      (node (ref "Q33") (pin "S") (pinfunction "S_S") (pintype "passive"))
      (node (ref "Q35") (pin "S") (pinfunction "S_S") (pintype "passive"))
      (node (ref "Q37") (pin "S") (pinfunction "S_S") (pintype "passive"))
      (node (ref "Q39") (pin "S") (pinfunction "S_S") (pintype "passive"))
      (node (ref "Q41") (pin "S") (pinfunction "S_S") (pintype "passive"))
      (node (ref "Q43") (pin "S") (pinfunction "S_S") (pintype "passive"))
      (node (ref "Q45") (pin "S") (pinfunction "S_S") (pintype "passive"))
      (node (ref "Q47") (pin "S") (pinfunction "S_S") (pintype "passive"))
      (node (ref "Q49") (pin "S") (pinfunction "S_S") (pintype "passive"))
      (node (ref "Q5") (pin "S") (pinfunction "S_S") (pintype "passive"))
      (node (ref "Q51") (pin "S") (pinfunction "S_S") (pintype "passive"))
      (node (ref "Q53") (pin "S") (pinfunction "S_S") (pintype "passive"))
      (node (ref "Q55") (pin "S") (pinfunction "S_S") (pintype "passive"))
      (node (ref "Q57") (pin "S") (pinfunction "S_S") (pintype "passive"))
      (node (ref "Q59") (pin "S") (pinfunction "S_S") (pintype "passive"))
      (node (ref "Q61") (pin "S") (pinfunction "S_S") (pintype "passive"))
      (node (ref "Q63") (pin "S") (pinfunction "S_S") (pintype "passive"))
      (node (ref "Q65") (pin "S") (pinfunction "S_S") (pintype "passive"))
      (node (ref "Q67") (pin "S") (pinfunction "S_S") (pintype "passive"))
      (node (ref "Q69") (pin "S") (pinfunction "S_S") (pintype "passive"))
      (node (ref "Q7") (pin "S") (pinfunction "S_S") (pintype "passive"))
      (node (ref "Q71") (pin "S") (pinfunction "S_S") (pintype "passive"))
      (node (ref "Q73") (pin "S") (pinfunction "S_S") (pintype "passive"))
      (node (ref "Q75") (pin "S") (pinfunction "S_S") (pintype "passive"))
      (node (ref "Q77") (pin "S") (pinfunction "S_S") (pintype "passive"))
      (node (ref "Q79") (pin "S") (pinfunction "S_S") (pintype "passive"))
      (node (ref "Q8") (pin "S") (pinfunction "S_S") (pintype "passive"))
      (node (ref "Q81") (pin "S") (pinfunction "S_S") (pintype "passive"))
      (node (ref "Q83") (pin "S") (pinfunction "S_S") (pintype "passive"))
      (node (ref "Q85") (pin "S") (pinfunction "S_S") (pintype "passive"))
      (node (ref "Q87") (pin "S") (pinfunction "S_S") (pintype "passive"))
      (node (ref "Q89") (pin "S") (pinfunction "S_S") (pintype "passive"))
      (node (ref "Q91") (pin "S") (pinfunction "S_S") (pintype "passive"))
      (node (ref "Q93") (pin "S") (pinfunction "S_S") (pintype "passive"))
      (node (ref "Q95") (pin "S") (pinfunction "S_S") (pintype "passive"))
      (node (ref "Q97") (pin "S") (pinfunction "S_S") (pintype "passive"))
      (node (ref "Q99") (pin "S") (pinfunction "S_S") (pintype "passive"))
    )
    (net (code "37") (name "Net-(D1-C)") (class "Default")
      (node (ref "D1") (pin "K") (pinfunction "C_K") (pintype "passive"))
      (node (ref "R7") (pin "2") (pinfunction "2_2") (pintype "passive"))
    )
    (net (code "38") (name "Net-(D2-C)") (class "Default")
      (node (ref "D2") (pin "K") (pinfunction "C_K") (pintype "passive"))
      (node (ref "R32") (pin "2") (pinfunction "2_2") (pintype "passive"))
    )
    (net (code "39") (name "Net-(D3-C)") (class "Default")
      (node (ref "D3") (pin "K") (pinfunction "C_K") (pintype "passive"))
      (node (ref "R41") (pin "2") (pinfunction "2_2") (pintype "passive"))
    )
    (net (code "40") (name "Net-(D4-C)") (class "Default")
      (node (ref "D4") (pin "K") (pinfunction "C_K") (pintype "passive"))
      (node (ref "R50") (pin "2") (pinfunction "2_2") (pintype "passive"))
    )
    (net (code "41") (name "Net-(D5-C)") (class "Default")
      (node (ref "D5") (pin "K") (pinfunction "C_K") (pintype "passive"))
      (node (ref "R59") (pin "2") (pinfunction "2_2") (pintype "passive"))
    )
    (net (code "42") (name "Net-(D6-C)") (class "Default")
      (node (ref "D6") (pin "K") (pinfunction "C_K") (pintype "passive"))
      (node (ref "R68") (pin "2") (pinfunction "2_2") (pintype "passive"))
    )
    (net (code "43") (name "Net-(D7-C)") (class "Default")
      (node (ref "D7") (pin "K") (pinfunction "C_K") (pintype "passive"))
      (node (ref "R77") (pin "2") (pinfunction "2_2") (pintype "passive"))
    )
    (net (code "44") (name "Net-(D8-C)") (class "Default")
      (node (ref "D8") (pin "K") (pinfunction "C_K") (pintype "passive"))
      (node (ref "R86") (pin "2") (pinfunction "2_2") (pintype "passive"))
    )
    (net (code "45") (name "Net-(D9-C)") (class "Default")
      (node (ref "D9") (pin "K") (pinfunction "C_K") (pintype "passive"))
      (node (ref "R95") (pin "2") (pinfunction "2_2") (pintype "passive"))
    )
    (net (code "46") (name "Net-(D10-C)") (class "Default")
      (node (ref "D10") (pin "K") (pinfunction "C_K") (pintype "passive"))
      (node (ref "R104") (pin "2") (pinfunction "2_2") (pintype "passive"))
    )
    (net (code "47") (name "Net-(D11-C)") (class "Default")
      (node (ref "D11") (pin "K") (pinfunction "C_K") (pintype "passive"))
      (node (ref "R135") (pin "2") (pinfunction "2_2") (pintype "passive"))
    )
    (net (code "48") (name "Net-(D12-C)") (class "Default")
      (node (ref "D12") (pin "K") (pinfunction "C_K") (pintype "passive"))
      (node (ref "R144") (pin "2") (pinfunction "2_2") (pintype "passive"))
    )
    (net (code "49") (name "Net-(D13-C)") (class "Default")
      (node (ref "D13") (pin "K") (pinfunction "C_K") (pintype "passive"))
      (node (ref "R153") (pin "2") (pinfunction "2_2") (pintype "passive"))
    )
    (net (code "50") (name "Net-(D14-C)") (class "Default")
      (node (ref "D14") (pin "K") (pinfunction "C_K") (pintype "passive"))
      (node (ref "R162") (pin "2") (pinfunction "2_2") (pintype "passive"))
    )
    (net (code "51") (name "Net-(D15-C)") (class "Default")
      (node (ref "D15") (pin "K") (pinfunction "C_K") (pintype "passive"))
      (node (ref "R171") (pin "2") (pinfunction "2_2") (pintype "passive"))
    )
    (net (code "52") (name "Net-(D16-C)") (class "Default")
      (node (ref "D16") (pin "K") (pinfunction "C_K") (pintype "passive"))
      (node (ref "R180") (pin "2") (pinfunction "2_2") (pintype "passive"))
    )
    (net (code "53") (name "Net-(D17-C)") (class "Default")
      (node (ref "D17") (pin "K") (pinfunction "C_K") (pintype "passive"))
      (node (ref "R114") (pin "2") (pinfunction "2_2") (pintype "passive"))
    )
    (net (code "54") (name "Net-(D18-C)") (class "Default")
      (node (ref "D18") (pin "K") (pinfunction "C_K") (pintype "passive"))
      (node (ref "R117") (pin "2") (pinfunction "2_2") (pintype "passive"))
    )
    (net (code "55") (name "Net-(D19-C)") (class "Default")
      (node (ref "D19") (pin "K") (pinfunction "C_K") (pintype "passive"))
      (node (ref "R119") (pin "2") (pinfunction "2_2") (pintype "passive"))
    )
    (net (code "56") (name "Net-(D20-C)") (class "Default")
      (node (ref "D20") (pin "K") (pinfunction "C_K") (pintype "passive"))
      (node (ref "R121") (pin "2") (pinfunction "2_2") (pintype "passive"))
    )
    (net (code "57") (name "Net-(D21-C)") (class "Default")
      (node (ref "D21") (pin "K") (pinfunction "C_K") (pintype "passive"))
      (node (ref "R123") (pin "2") (pinfunction "2_2") (pintype "passive"))
    )
    (net (code "58") (name "Net-(D22-C)") (class "Default")
      (node (ref "D22") (pin "K") (pinfunction "C_K") (pintype "passive"))
      (node (ref "R125") (pin "2") (pinfunction "2_2") (pintype "passive"))
    )
    (net (code "59") (name "Net-(D23-C)") (class "Default")
      (node (ref "D23") (pin "K") (pinfunction "C_K") (pintype "passive"))
      (node (ref "R127") (pin "2") (pinfunction "2_2") (pintype "passive"))
    )
    (net (code "60") (name "Net-(D24-C)") (class "Default")
      (node (ref "D24") (pin "K") (pinfunction "C_K") (pintype "passive"))
      (node (ref "R129") (pin "2") (pinfunction "2_2") (pintype "passive"))
    )
    (net (code "61") (name "Net-(D25-C)") (class "Default")
      (node (ref "D25") (pin "K") (pinfunction "C_K") (pintype "passive"))
      (node (ref "R131") (pin "2") (pinfunction "2_2") (pintype "passive"))
    )
    (net (code "62") (name "Net-(D26-C)") (class "Default")
      (node (ref "D26") (pin "K") (pinfunction "C_K") (pintype "passive"))
      (node (ref "R116") (pin "2") (pinfunction "2_2") (pintype "passive"))
    )
    (net (code "63") (name "Net-(D27-C)") (class "Default")
      (node (ref "D27") (pin "K") (pinfunction "C_K") (pintype "passive"))
      (node (ref "R118") (pin "2") (pinfunction "2_2") (pintype "passive"))
    )
    (net (code "64") (name "Net-(D28-C)") (class "Default")
      (node (ref "D28") (pin "K") (pinfunction "C_K") (pintype "passive"))
      (node (ref "R120") (pin "2") (pinfunction "2_2") (pintype "passive"))
    )
    (net (code "65") (name "Net-(D29-C)") (class "Default")
      (node (ref "D29") (pin "K") (pinfunction "C_K") (pintype "passive"))
      (node (ref "R122") (pin "2") (pinfunction "2_2") (pintype "passive"))
    )
    (net (code "66") (name "Net-(D30-C)") (class "Default")
      (node (ref "D30") (pin "K") (pinfunction "C_K") (pintype "passive"))
      (node (ref "R124") (pin "2") (pinfunction "2_2") (pintype "passive"))
    )
    (net (code "67") (name "Net-(D31-C)") (class "Default")
      (node (ref "D31") (pin "K") (pinfunction "C_K") (pintype "passive"))
      (node (ref "R126") (pin "2") (pinfunction "2_2") (pintype "passive"))
    )
    (net (code "68") (name "Net-(D32-C)") (class "Default")
      (node (ref "D32") (pin "K") (pinfunction "C_K") (pintype "passive"))
      (node (ref "R128") (pin "2") (pinfunction "2_2") (pintype "passive"))
    )
    (net (code "69") (name "Net-(D33-C)") (class "Default")
      (node (ref "D33") (pin "K") (pinfunction "C_K") (pintype "passive"))
      (node (ref "R130") (pin "2") (pinfunction "2_2") (pintype "passive"))
    )
    (net (code "70") (name "Net-(D34-C)") (class "Default")
      (node (ref "D34") (pin "K") (pinfunction "C_K") (pintype "passive"))
      (node (ref "R133") (pin "2") (pinfunction "2_2") (pintype "passive"))
    )
    (net (code "71") (name "Net-(Q1-PadD)") (class "Default")
      (node (ref "Q1") (pin "D") (pinfunction "D_D") (pintype "passive"))
      (node (ref "Q2") (pin "S") (pinfunction "S_S") (pintype "passive"))
    )
    (net (code "72") (name "Net-(Q2-PadD)") (class "Default")
      (node (ref "Q2") (pin "D") (pinfunction "D_D") (pintype "passive"))
      (node (ref "Q4") (pin "G") (pinfunction "G_G") (pintype "passive"))
      (node (ref "Q6") (pin "G") (pinfunction "G_G") (pintype "passive"))
      (node (ref "R1") (pin "1") (pinfunction "1_1") (pintype "passive"))
    )
    (net (code "73") (name "Net-(Q3-PadD)") (class "Default")
      (node (ref "Q3") (pin "D") (pinfunction "D_D") (pintype "passive"))
      (node (ref "Q4") (pin "S") (pinfunction "S_S") (pintype "passive"))
    )
    (net (code "74") (name "Net-(Q4-PadD)") (class "Default")
      (node (ref "Q4") (pin "D") (pinfunction "D_D") (pintype "passive"))
      (node (ref "Q8") (pin "G") (pinfunction "G_G") (pintype "passive"))
      (node (ref "R2") (pin "1") (pinfunction "1_1") (pintype "passive"))
    )
    (net (code "75") (name "Net-(Q5-PadD)") (class "Default")
      (node (ref "Q5") (pin "D") (pinfunction "D_D") (pintype "passive"))
      (node (ref "Q6") (pin "S") (pinfunction "S_S") (pintype "passive"))
    )
    (net (code "76") (name "Net-(Q8-PadD)") (class "Default")
      (node (ref "Q8") (pin "D") (pinfunction "D_D") (pintype "passive"))
      (node (ref "Q9") (pin "S") (pinfunction "S_S") (pintype "passive"))
    )
    (net (code "77") (name "Net-(Q10-PadD)") (class "Default")
      (node (ref "Q10") (pin "D") (pinfunction "D_D") (pintype "passive"))
      (node (ref "Q11") (pin "S") (pinfunction "S_S") (pintype "passive"))
    )
    (net (code "78") (name "Net-(Q11-PadG)") (class "Default")
      (node (ref "Q11") (pin "G") (pinfunction "G_G") (pintype "passive"))
      (node (ref "Q14") (pin "D") (pinfunction "D_D") (pintype "passive"))
      (node (ref "R5") (pin "1") (pinfunction "1_1") (pintype "passive"))
    )
    (net (code "79") (name "Net-(Q12-PadD)") (class "Default")
      (node (ref "Q12") (pin "D") (pinfunction "D_D") (pintype "passive"))
      (node (ref "Q13") (pin "S") (pinfunction "S_S") (pintype "passive"))
    )
    (net (code "80") (name "Net-(Q12-PadG)") (class "Default")
      (node (ref "Q12") (pin "G") (pinfunction "G_G") (pintype "passive"))
      (node (ref "Q16") (pin "D") (pinfunction "D_D") (pintype "passive"))
      (node (ref "R6") (pin "1") (pinfunction "1_1") (pintype "passive"))
    )
    (net (code "81") (name "Net-(Q14-PadG)") (class "Default")
      (node (ref "Q14") (pin "G") (pinfunction "G_G") (pintype "passive"))
      (node (ref "Q6") (pin "D") (pinfunction "D_D") (pintype "passive"))
      (node (ref "Q9") (pin "G") (pinfunction "G_G") (pintype "passive"))
      (node (ref "R3") (pin "1") (pinfunction "1_1") (pintype "passive"))
    )
    (net (code "82") (name "Net-(Q14-PadS)") (class "Default")
      (node (ref "Q14") (pin "S") (pinfunction "S_S") (pintype "passive"))
      (node (ref "Q7") (pin "D") (pinfunction "D_D") (pintype "passive"))
    )
    (net (code "83") (name "Net-(Q15-PadD)") (class "Default")
      (node (ref "Q15") (pin "D") (pinfunction "D_D") (pintype "passive"))
      (node (ref "Q16") (pin "S") (pinfunction "S_S") (pintype "passive"))
    )
    (net (code "84") (name "Net-(Q16-PadG)") (class "Default")
      (node (ref "Q16") (pin "G") (pinfunction "G_G") (pintype "passive"))
      (node (ref "Q5") (pin "G") (pinfunction "G_G") (pintype "passive"))
      (node (ref "Q9") (pin "D") (pinfunction "D_D") (pintype "passive"))
      (node (ref "R4") (pin "1") (pinfunction "1_1") (pintype "passive"))
    )
    (net (code "85") (name "Net-(Q17-PadD)") (class "Default")
      (node (ref "Q17") (pin "D") (pinfunction "D_D") (pintype "passive"))
      (node (ref "Q18") (pin "S") (pinfunction "S_S") (pintype "passive"))
    )
    (net (code "86") (name "Net-(Q18-PadD)") (class "Default")
      (node (ref "Q18") (pin "D") (pinfunction "D_D") (pintype "passive"))
      (node (ref "Q20") (pin "G") (pinfunction "G_G") (pintype "passive"))
      (node (ref "Q22") (pin "G") (pinfunction "G_G") (pintype "passive"))
      (node (ref "R26") (pin "1") (pinfunction "1_1") (pintype "passive"))
    )
    (net (code "87") (name "Net-(Q19-PadD)") (class "Default")
      (node (ref "Q19") (pin "D") (pinfunction "D_D") (pintype "passive"))
      (node (ref "Q20") (pin "S") (pinfunction "S_S") (pintype "passive"))
    )
    (net (code "88") (name "Net-(Q20-PadD)") (class "Default")
      (node (ref "Q20") (pin "D") (pinfunction "D_D") (pintype "passive"))
      (node (ref "Q23") (pin "G") (pinfunction "G_G") (pintype "passive"))
      (node (ref "R27") (pin "1") (pinfunction "1_1") (pintype "passive"))
    )
    (net (code "89") (name "Net-(Q21-PadD)") (class "Default")
      (node (ref "Q21") (pin "D") (pinfunction "D_D") (pintype "passive"))
      (node (ref "Q22") (pin "S") (pinfunction "S_S") (pintype "passive"))
    )
    (net (code "90") (name "Net-(Q21-PadG)") (class "Default")
      (node (ref "Q21") (pin "G") (pinfunction "G_G") (pintype "passive"))
      (node (ref "Q24") (pin "D") (pinfunction "D_D") (pintype "passive"))
      (node (ref "Q32") (pin "G") (pinfunction "G_G") (pintype "passive"))
      (node (ref "R29") (pin "1") (pinfunction "1_1") (pintype "passive"))
    )
    (net (code "91") (name "Net-(Q22-PadD)") (class "Default")
      (node (ref "Q22") (pin "D") (pinfunction "D_D") (pintype "passive"))
      (node (ref "Q24") (pin "G") (pinfunction "G_G") (pintype "passive"))
      (node (ref "Q30") (pin "G") (pinfunction "G_G") (pintype "passive"))
      (node (ref "R28") (pin "1") (pinfunction "1_1") (pintype "passive"))
    )
    (net (code "92") (name "Net-(Q23-PadD)") (class "Default")
      (node (ref "Q23") (pin "D") (pinfunction "D_D") (pintype "passive"))
      (node (ref "Q24") (pin "S") (pinfunction "S_S") (pintype "passive"))
    )
    (net (code "93") (name "Net-(Q25-PadD)") (class "Default")
      (node (ref "Q25") (pin "D") (pinfunction "D_D") (pintype "passive"))
      (node (ref "Q26") (pin "S") (pinfunction "S_S") (pintype "passive"))
    )
    (net (code "94") (name "Net-(Q26-PadG)") (class "Default")
      (node (ref "Q26") (pin "G") (pinfunction "G_G") (pintype "passive"))
      (node (ref "Q30") (pin "D") (pinfunction "D_D") (pintype "passive"))
      (node (ref "R30") (pin "1") (pinfunction "1_1") (pintype "passive"))
    )
    (net (code "95") (name "Net-(Q27-PadD)") (class "Default")
      (node (ref "Q27") (pin "D") (pinfunction "D_D") (pintype "passive"))
      (node (ref "Q28") (pin "S") (pinfunction "S_S") (pintype "passive"))
    )
    (net (code "96") (name "Net-(Q27-PadG)") (class "Default")
      (node (ref "Q27") (pin "G") (pinfunction "G_G") (pintype "passive"))
      (node (ref "Q32") (pin "D") (pinfunction "D_D") (pintype "passive"))
      (node (ref "R31") (pin "1") (pinfunction "1_1") (pintype "passive"))
    )
    (net (code "97") (name "Net-(Q29-PadD)") (class "Default")
      (node (ref "Q29") (pin "D") (pinfunction "D_D") (pintype "passive"))
      (node (ref "Q30") (pin "S") (pinfunction "S_S") (pintype "passive"))
    )
    (net (code "98") (name "Net-(Q31-PadD)") (class "Default")
      (node (ref "Q31") (pin "D") (pinfunction "D_D") (pintype "passive"))
      (node (ref "Q32") (pin "S") (pinfunction "S_S") (pintype "passive"))
    )
    (net (code "99") (name "Net-(Q33-PadD)") (class "Default")
      (node (ref "Q33") (pin "D") (pinfunction "D_D") (pintype "passive"))
      (node (ref "Q34") (pin "S") (pinfunction "S_S") (pintype "passive"))
    )
    (net (code "100") (name "Net-(Q34-PadD)") (class "Default")
      (node (ref "Q34") (pin "D") (pinfunction "D_D") (pintype "passive"))
      (node (ref "Q36") (pin "G") (pinfunction "G_G") (pintype "passive"))
      (node (ref "Q38") (pin "G") (pinfunction "G_G") (pintype "passive"))
      (node (ref "R35") (pin "1") (pinfunction "1_1") (pintype "passive"))
    )
    (net (code "101") (name "Net-(Q35-PadD)") (class "Default")
      (node (ref "Q35") (pin "D") (pinfunction "D_D") (pintype "passive"))
      (node (ref "Q36") (pin "S") (pinfunction "S_S") (pintype "passive"))
    )
    (net (code "102") (name "Net-(Q36-PadD)") (class "Default")
      (node (ref "Q36") (pin "D") (pinfunction "D_D") (pintype "passive"))
      (node (ref "Q39") (pin "G") (pinfunction "G_G") (pintype "passive"))
      (node (ref "R36") (pin "1") (pinfunction "1_1") (pintype "passive"))
    )
    (net (code "103") (name "Net-(Q37-PadD)") (class "Default")
      (node (ref "Q37") (pin "D") (pinfunction "D_D") (pintype "passive"))
      (node (ref "Q38") (pin "S") (pinfunction "S_S") (pintype "passive"))
    )
    (net (code "104") (name "Net-(Q37-PadG)") (class "Default")
      (node (ref "Q37") (pin "G") (pinfunction "G_G") (pintype "passive"))
      (node (ref "Q40") (pin "D") (pinfunction "D_D") (pintype "passive"))
      (node (ref "Q48") (pin "G") (pinfunction "G_G") (pintype "passive"))
      (node (ref "R38") (pin "1") (pinfunction "1_1") (pintype "passive"))
    )
    (net (code "105") (name "Net-(Q38-PadD)") (class "Default")
      (node (ref "Q38") (pin "D") (pinfunction "D_D") (pintype "passive"))
      (node (ref "Q40") (pin "G") (pinfunction "G_G") (pintype "passive"))
      (node (ref "Q46") (pin "G") (pinfunction "G_G") (pintype "passive"))
      (node (ref "R37") (pin "1") (pinfunction "1_1") (pintype "passive"))
    )
    (net (code "106") (name "Net-(Q39-PadD)") (class "Default")
      (node (ref "Q39") (pin "D") (pinfunction "D_D") (pintype "passive"))
      (node (ref "Q40") (pin "S") (pinfunction "S_S") (pintype "passive"))
    )
    (net (code "107") (name "Net-(Q41-PadD)") (class "Default")
      (node (ref "Q41") (pin "D") (pinfunction "D_D") (pintype "passive"))
      (node (ref "Q42") (pin "S") (pinfunction "S_S") (pintype "passive"))
    )
    (net (code "108") (name "Net-(Q42-PadG)") (class "Default")
      (node (ref "Q42") (pin "G") (pinfunction "G_G") (pintype "passive"))
      (node (ref "Q46") (pin "D") (pinfunction "D_D") (pintype "passive"))
      (node (ref "R39") (pin "1") (pinfunction "1_1") (pintype "passive"))
    )
    (net (code "109") (name "Net-(Q43-PadD)") (class "Default")
      (node (ref "Q43") (pin "D") (pinfunction "D_D") (pintype "passive"))
      (node (ref "Q44") (pin "S") (pinfunction "S_S") (pintype "passive"))
    )
    (net (code "110") (name "Net-(Q43-PadG)") (class "Default")
      (node (ref "Q43") (pin "G") (pinfunction "G_G") (pintype "passive"))
      (node (ref "Q48") (pin "D") (pinfunction "D_D") (pintype "passive"))
      (node (ref "R40") (pin "1") (pinfunction "1_1") (pintype "passive"))
    )
    (net (code "111") (name "Net-(Q45-PadD)") (class "Default")
      (node (ref "Q45") (pin "D") (pinfunction "D_D") (pintype "passive"))
      (node (ref "Q46") (pin "S") (pinfunction "S_S") (pintype "passive"))
    )
    (net (code "112") (name "Net-(Q47-PadD)") (class "Default")
      (node (ref "Q47") (pin "D") (pinfunction "D_D") (pintype "passive"))
      (node (ref "Q48") (pin "S") (pinfunction "S_S") (pintype "passive"))
    )
    (net (code "113") (name "Net-(Q49-PadD)") (class "Default")
      (node (ref "Q49") (pin "D") (pinfunction "D_D") (pintype "passive"))
      (node (ref "Q50") (pin "S") (pinfunction "S_S") (pintype "passive"))
    )
    (net (code "114") (name "Net-(Q50-PadD)") (class "Default")
      (node (ref "Q50") (pin "D") (pinfunction "D_D") (pintype "passive"))
      (node (ref "Q52") (pin "G") (pinfunction "G_G") (pintype "passive"))
      (node (ref "Q54") (pin "G") (pinfunction "G_G") (pintype "passive"))
      (node (ref "R44") (pin "1") (pinfunction "1_1") (pintype "passive"))
    )
    (net (code "115") (name "Net-(Q51-PadD)") (class "Default")
      (node (ref "Q51") (pin "D") (pinfunction "D_D") (pintype "passive"))
      (node (ref "Q52") (pin "S") (pinfunction "S_S") (pintype "passive"))
    )
    (net (code "116") (name "Net-(Q52-PadD)") (class "Default")
      (node (ref "Q52") (pin "D") (pinfunction "D_D") (pintype "passive"))
      (node (ref "Q55") (pin "G") (pinfunction "G_G") (pintype "passive"))
      (node (ref "R45") (pin "1") (pinfunction "1_1") (pintype "passive"))
    )
    (net (code "117") (name "Net-(Q53-PadD)") (class "Default")
      (node (ref "Q53") (pin "D") (pinfunction "D_D") (pintype "passive"))
      (node (ref "Q54") (pin "S") (pinfunction "S_S") (pintype "passive"))
    )
    (net (code "118") (name "Net-(Q53-PadG)") (class "Default")
      (node (ref "Q53") (pin "G") (pinfunction "G_G") (pintype "passive"))
      (node (ref "Q56") (pin "D") (pinfunction "D_D") (pintype "passive"))
      (node (ref "Q64") (pin "G") (pinfunction "G_G") (pintype "passive"))
      (node (ref "R47") (pin "1") (pinfunction "1_1") (pintype "passive"))
    )
    (net (code "119") (name "Net-(Q54-PadD)") (class "Default")
      (node (ref "Q54") (pin "D") (pinfunction "D_D") (pintype "passive"))
      (node (ref "Q56") (pin "G") (pinfunction "G_G") (pintype "passive"))
      (node (ref "Q62") (pin "G") (pinfunction "G_G") (pintype "passive"))
      (node (ref "R46") (pin "1") (pinfunction "1_1") (pintype "passive"))
    )
    (net (code "120") (name "Net-(Q55-PadD)") (class "Default")
      (node (ref "Q55") (pin "D") (pinfunction "D_D") (pintype "passive"))
      (node (ref "Q56") (pin "S") (pinfunction "S_S") (pintype "passive"))
    )
    (net (code "121") (name "Net-(Q57-PadD)") (class "Default")
      (node (ref "Q57") (pin "D") (pinfunction "D_D") (pintype "passive"))
      (node (ref "Q58") (pin "S") (pinfunction "S_S") (pintype "passive"))
    )
    (net (code "122") (name "Net-(Q58-PadG)") (class "Default")
      (node (ref "Q58") (pin "G") (pinfunction "G_G") (pintype "passive"))
      (node (ref "Q62") (pin "D") (pinfunction "D_D") (pintype "passive"))
      (node (ref "R48") (pin "1") (pinfunction "1_1") (pintype "passive"))
    )
    (net (code "123") (name "Net-(Q59-PadD)") (class "Default")
      (node (ref "Q59") (pin "D") (pinfunction "D_D") (pintype "passive"))
      (node (ref "Q60") (pin "S") (pinfunction "S_S") (pintype "passive"))
    )
    (net (code "124") (name "Net-(Q59-PadG)") (class "Default")
      (node (ref "Q59") (pin "G") (pinfunction "G_G") (pintype "passive"))
      (node (ref "Q64") (pin "D") (pinfunction "D_D") (pintype "passive"))
      (node (ref "R49") (pin "1") (pinfunction "1_1") (pintype "passive"))
    )
    (net (code "125") (name "Net-(Q61-PadD)") (class "Default")
      (node (ref "Q61") (pin "D") (pinfunction "D_D") (pintype "passive"))
      (node (ref "Q62") (pin "S") (pinfunction "S_S") (pintype "passive"))
    )
    (net (code "126") (name "Net-(Q63-PadD)") (class "Default")
      (node (ref "Q63") (pin "D") (pinfunction "D_D") (pintype "passive"))
      (node (ref "Q64") (pin "S") (pinfunction "S_S") (pintype "passive"))
    )
    (net (code "127") (name "Net-(Q65-PadD)") (class "Default")
      (node (ref "Q65") (pin "D") (pinfunction "D_D") (pintype "passive"))
      (node (ref "Q66") (pin "S") (pinfunction "S_S") (pintype "passive"))
    )
    (net (code "128") (name "Net-(Q66-PadD)") (class "Default")
      (node (ref "Q66") (pin "D") (pinfunction "D_D") (pintype "passive"))
      (node (ref "Q68") (pin "G") (pinfunction "G_G") (pintype "passive"))
      (node (ref "Q70") (pin "G") (pinfunction "G_G") (pintype "passive"))
      (node (ref "R53") (pin "1") (pinfunction "1_1") (pintype "passive"))
    )
    (net (code "129") (name "Net-(Q67-PadD)") (class "Default")
      (node (ref "Q67") (pin "D") (pinfunction "D_D") (pintype "passive"))
      (node (ref "Q68") (pin "S") (pinfunction "S_S") (pintype "passive"))
    )
    (net (code "130") (name "Net-(Q68-PadD)") (class "Default")
      (node (ref "Q68") (pin "D") (pinfunction "D_D") (pintype "passive"))
      (node (ref "Q71") (pin "G") (pinfunction "G_G") (pintype "passive"))
      (node (ref "R54") (pin "1") (pinfunction "1_1") (pintype "passive"))
    )
    (net (code "131") (name "Net-(Q69-PadD)") (class "Default")
      (node (ref "Q69") (pin "D") (pinfunction "D_D") (pintype "passive"))
      (node (ref "Q70") (pin "S") (pinfunction "S_S") (pintype "passive"))
    )
    (net (code "132") (name "Net-(Q69-PadG)") (class "Default")
      (node (ref "Q69") (pin "G") (pinfunction "G_G") (pintype "passive"))
      (node (ref "Q72") (pin "D") (pinfunction "D_D") (pintype "passive"))
      (node (ref "Q80") (pin "G") (pinfunction "G_G") (pintype "passive"))
      (node (ref "R56") (pin "1") (pinfunction "1_1") (pintype "passive"))
    )
    (net (code "133") (name "Net-(Q70-PadD)") (class "Default")
      (node (ref "Q70") (pin "D") (pinfunction "D_D") (pintype "passive"))
      (node (ref "Q72") (pin "G") (pinfunction "G_G") (pintype "passive"))
      (node (ref "Q78") (pin "G") (pinfunction "G_G") (pintype "passive"))
      (node (ref "R55") (pin "1") (pinfunction "1_1") (pintype "passive"))
    )
    (net (code "134") (name "Net-(Q71-PadD)") (class "Default")
      (node (ref "Q71") (pin "D") (pinfunction "D_D") (pintype "passive"))
      (node (ref "Q72") (pin "S") (pinfunction "S_S") (pintype "passive"))
    )
    (net (code "135") (name "Net-(Q73-PadD)") (class "Default")
      (node (ref "Q73") (pin "D") (pinfunction "D_D") (pintype "passive"))
      (node (ref "Q74") (pin "S") (pinfunction "S_S") (pintype "passive"))
    )
    (net (code "136") (name "Net-(Q74-PadG)") (class "Default")
      (node (ref "Q74") (pin "G") (pinfunction "G_G") (pintype "passive"))
      (node (ref "Q78") (pin "D") (pinfunction "D_D") (pintype "passive"))
      (node (ref "R57") (pin "1") (pinfunction "1_1") (pintype "passive"))
    )
    (net (code "137") (name "Net-(Q75-PadD)") (class "Default")
      (node (ref "Q75") (pin "D") (pinfunction "D_D") (pintype "passive"))
      (node (ref "Q76") (pin "S") (pinfunction "S_S") (pintype "passive"))
    )
    (net (code "138") (name "Net-(Q75-PadG)") (class "Default")
      (node (ref "Q75") (pin "G") (pinfunction "G_G") (pintype "passive"))
      (node (ref "Q80") (pin "D") (pinfunction "D_D") (pintype "passive"))
      (node (ref "R58") (pin "1") (pinfunction "1_1") (pintype "passive"))
    )
    (net (code "139") (name "Net-(Q77-PadD)") (class "Default")
      (node (ref "Q77") (pin "D") (pinfunction "D_D") (pintype "passive"))
      (node (ref "Q78") (pin "S") (pinfunction "S_S") (pintype "passive"))
    )
    (net (code "140") (name "Net-(Q79-PadD)") (class "Default")
      (node (ref "Q79") (pin "D") (pinfunction "D_D") (pintype "passive"))
      (node (ref "Q80") (pin "S") (pinfunction "S_S") (pintype "passive"))
    )
    (net (code "141") (name "Net-(Q81-PadD)") (class "Default")
      (node (ref "Q81") (pin "D") (pinfunction "D_D") (pintype "passive"))
      (node (ref "Q82") (pin "S") (pinfunction "S_S") (pintype "passive"))
    )
    (net (code "142") (name "Net-(Q82-PadD)") (class "Default")
      (node (ref "Q82") (pin "D") (pinfunction "D_D") (pintype "passive"))
      (node (ref "Q84") (pin "G") (pinfunction "G_G") (pintype "passive"))
      (node (ref "Q86") (pin "G") (pinfunction "G_G") (pintype "passive"))
      (node (ref "R62") (pin "1") (pinfunction "1_1") (pintype "passive"))
    )
    (net (code "143") (name "Net-(Q83-PadD)") (class "Default")
      (node (ref "Q83") (pin "D") (pinfunction "D_D") (pintype "passive"))
      (node (ref "Q84") (pin "S") (pinfunction "S_S") (pintype "passive"))
    )
    (net (code "144") (name "Net-(Q84-PadD)") (class "Default")
      (node (ref "Q84") (pin "D") (pinfunction "D_D") (pintype "passive"))
      (node (ref "Q87") (pin "G") (pinfunction "G_G") (pintype "passive"))
      (node (ref "R63") (pin "1") (pinfunction "1_1") (pintype "passive"))
    )
    (net (code "145") (name "Net-(Q85-PadD)") (class "Default")
      (node (ref "Q85") (pin "D") (pinfunction "D_D") (pintype "passive"))
      (node (ref "Q86") (pin "S") (pinfunction "S_S") (pintype "passive"))
    )
    (net (code "146") (name "Net-(Q85-PadG)") (class "Default")
      (node (ref "Q85") (pin "G") (pinfunction "G_G") (pintype "passive"))
      (node (ref "Q88") (pin "D") (pinfunction "D_D") (pintype "passive"))
      (node (ref "Q96") (pin "G") (pinfunction "G_G") (pintype "passive"))
      (node (ref "R65") (pin "1") (pinfunction "1_1") (pintype "passive"))
    )
    (net (code "147") (name "Net-(Q86-PadD)") (class "Default")
      (node (ref "Q86") (pin "D") (pinfunction "D_D") (pintype "passive"))
      (node (ref "Q88") (pin "G") (pinfunction "G_G") (pintype "passive"))
      (node (ref "Q94") (pin "G") (pinfunction "G_G") (pintype "passive"))
      (node (ref "R64") (pin "1") (pinfunction "1_1") (pintype "passive"))
    )
    (net (code "148") (name "Net-(Q87-PadD)") (class "Default")
      (node (ref "Q87") (pin "D") (pinfunction "D_D") (pintype "passive"))
      (node (ref "Q88") (pin "S") (pinfunction "S_S") (pintype "passive"))
    )
    (net (code "149") (name "Net-(Q89-PadD)") (class "Default")
      (node (ref "Q89") (pin "D") (pinfunction "D_D") (pintype "passive"))
      (node (ref "Q90") (pin "S") (pinfunction "S_S") (pintype "passive"))
    )
    (net (code "150") (name "Net-(Q90-PadG)") (class "Default")
      (node (ref "Q90") (pin "G") (pinfunction "G_G") (pintype "passive"))
      (node (ref "Q94") (pin "D") (pinfunction "D_D") (pintype "passive"))
      (node (ref "R66") (pin "1") (pinfunction "1_1") (pintype "passive"))
    )
    (net (code "151") (name "Net-(Q91-PadD)") (class "Default")
      (node (ref "Q91") (pin "D") (pinfunction "D_D") (pintype "passive"))
      (node (ref "Q92") (pin "S") (pinfunction "S_S") (pintype "passive"))
    )
    (net (code "152") (name "Net-(Q91-PadG)") (class "Default")
      (node (ref "Q91") (pin "G") (pinfunction "G_G") (pintype "passive"))
      (node (ref "Q96") (pin "D") (pinfunction "D_D") (pintype "passive"))
      (node (ref "R67") (pin "1") (pinfunction "1_1") (pintype "passive"))
    )
    (net (code "153") (name "Net-(Q93-PadD)") (class "Default")
      (node (ref "Q93") (pin "D") (pinfunction "D_D") (pintype "passive"))
      (node (ref "Q94") (pin "S") (pinfunction "S_S") (pintype "passive"))
    )
    (net (code "154") (name "Net-(Q95-PadD)") (class "Default")
      (node (ref "Q95") (pin "D") (pinfunction "D_D") (pintype "passive"))
      (node (ref "Q96") (pin "S") (pinfunction "S_S") (pintype "passive"))
    )
    (net (code "155") (name "Net-(Q97-PadD)") (class "Default")
      (node (ref "Q97") (pin "D") (pinfunction "D_D") (pintype "passive"))
      (node (ref "Q98") (pin "S") (pinfunction "S_S") (pintype "passive"))
    )
    (net (code "156") (name "Net-(Q100-PadD)") (class "Default")
      (node (ref "Q100") (pin "D") (pinfunction "D_D") (pintype "passive"))
      (node (ref "Q103") (pin "G") (pinfunction "G_G") (pintype "passive"))
      (node (ref "R72") (pin "1") (pinfunction "1_1") (pintype "passive"))
    )
    (net (code "157") (name "Net-(Q100-PadG)") (class "Default")
      (node (ref "Q100") (pin "G") (pinfunction "G_G") (pintype "passive"))
      (node (ref "Q102") (pin "G") (pinfunction "G_G") (pintype "passive"))
      (node (ref "Q98") (pin "D") (pinfunction "D_D") (pintype "passive"))
      (node (ref "R71") (pin "1") (pinfunction "1_1") (pintype "passive"))
    )
    (net (code "158") (name "Net-(Q100-PadS)") (class "Default")
      (node (ref "Q100") (pin "S") (pinfunction "S_S") (pintype "passive"))
      (node (ref "Q99") (pin "D") (pinfunction "D_D") (pintype "passive"))
    )
    (net (code "159") (name "Net-(Q101-PadD)") (class "Default")
      (node (ref "Q101") (pin "D") (pinfunction "D_D") (pintype "passive"))
      (node (ref "Q102") (pin "S") (pinfunction "S_S") (pintype "passive"))
    )
    (net (code "160") (name "Net-(Q101-PadG)") (class "Default")
      (node (ref "Q101") (pin "G") (pinfunction "G_G") (pintype "passive"))
      (node (ref "Q104") (pin "D") (pinfunction "D_D") (pintype "passive"))
      (node (ref "Q112") (pin "G") (pinfunction "G_G") (pintype "passive"))
      (node (ref "R74") (pin "1") (pinfunction "1_1") (pintype "passive"))
    )
    (net (code "161") (name "Net-(Q102-PadD)") (class "Default")
      (node (ref "Q102") (pin "D") (pinfunction "D_D") (pintype "passive"))
      (node (ref "Q104") (pin "G") (pinfunction "G_G") (pintype "passive"))
      (node (ref "Q110") (pin "G") (pinfunction "G_G") (pintype "passive"))
      (node (ref "R73") (pin "1") (pinfunction "1_1") (pintype "passive"))
    )
    (net (code "162") (name "Net-(Q103-PadD)") (class "Default")
      (node (ref "Q103") (pin "D") (pinfunction "D_D") (pintype "passive"))
      (node (ref "Q104") (pin "S") (pinfunction "S_S") (pintype "passive"))
    )
    (net (code "163") (name "Net-(Q105-PadD)") (class "Default")
      (node (ref "Q105") (pin "D") (pinfunction "D_D") (pintype "passive"))
      (node (ref "Q106") (pin "S") (pinfunction "S_S") (pintype "passive"))
    )
    (net (code "164") (name "Net-(Q106-PadG)") (class "Default")
      (node (ref "Q106") (pin "G") (pinfunction "G_G") (pintype "passive"))
      (node (ref "Q110") (pin "D") (pinfunction "D_D") (pintype "passive"))
      (node (ref "R75") (pin "1") (pinfunction "1_1") (pintype "passive"))
    )
    (net (code "165") (name "Net-(Q107-PadD)") (class "Default")
      (node (ref "Q107") (pin "D") (pinfunction "D_D") (pintype "passive"))
      (node (ref "Q108") (pin "S") (pinfunction "S_S") (pintype "passive"))
    )
    (net (code "166") (name "Net-(Q107-PadG)") (class "Default")
      (node (ref "Q107") (pin "G") (pinfunction "G_G") (pintype "passive"))
      (node (ref "Q112") (pin "D") (pinfunction "D_D") (pintype "passive"))
      (node (ref "R76") (pin "1") (pinfunction "1_1") (pintype "passive"))
    )
    (net (code "167") (name "Net-(Q109-PadD)") (class "Default")
      (node (ref "Q109") (pin "D") (pinfunction "D_D") (pintype "passive"))
      (node (ref "Q110") (pin "S") (pinfunction "S_S") (pintype "passive"))
    )
    (net (code "168") (name "Net-(Q111-PadD)") (class "Default")
      (node (ref "Q111") (pin "D") (pinfunction "D_D") (pintype "passive"))
      (node (ref "Q112") (pin "S") (pinfunction "S_S") (pintype "passive"))
    )
    (net (code "169") (name "Net-(Q113-PadD)") (class "Default")
      (node (ref "Q113") (pin "D") (pinfunction "D_D") (pintype "passive"))
      (node (ref "Q114") (pin "S") (pinfunction "S_S") (pintype "passive"))
    )
    (net (code "170") (name "Net-(Q114-PadD)") (class "Default")
      (node (ref "Q114") (pin "D") (pinfunction "D_D") (pintype "passive"))
      (node (ref "Q116") (pin "G") (pinfunction "G_G") (pintype "passive"))
      (node (ref "Q118") (pin "G") (pinfunction "G_G") (pintype "passive"))
      (node (ref "R80") (pin "1") (pinfunction "1_1") (pintype "passive"))
    )
    (net (code "171") (name "Net-(Q115-PadD)") (class "Default")
      (node (ref "Q115") (pin "D") (pinfunction "D_D") (pintype "passive"))
      (node (ref "Q116") (pin "S") (pinfunction "S_S") (pintype "passive"))
    )
    (net (code "172") (name "Net-(Q116-PadD)") (class "Default")
      (node (ref "Q116") (pin "D") (pinfunction "D_D") (pintype "passive"))
      (node (ref "Q119") (pin "G") (pinfunction "G_G") (pintype "passive"))
      (node (ref "R81") (pin "1") (pinfunction "1_1") (pintype "passive"))
    )
    (net (code "173") (name "Net-(Q117-PadD)") (class "Default")
      (node (ref "Q117") (pin "D") (pinfunction "D_D") (pintype "passive"))
      (node (ref "Q118") (pin "S") (pinfunction "S_S") (pintype "passive"))
    )
    (net (code "174") (name "Net-(Q117-PadG)") (class "Default")
      (node (ref "Q117") (pin "G") (pinfunction "G_G") (pintype "passive"))
      (node (ref "Q120") (pin "D") (pinfunction "D_D") (pintype "passive"))
      (node (ref "Q128") (pin "G") (pinfunction "G_G") (pintype "passive"))
      (node (ref "R83") (pin "1") (pinfunction "1_1") (pintype "passive"))
    )
    (net (code "175") (name "Net-(Q118-PadD)") (class "Default")
      (node (ref "Q118") (pin "D") (pinfunction "D_D") (pintype "passive"))
      (node (ref "Q120") (pin "G") (pinfunction "G_G") (pintype "passive"))
      (node (ref "Q126") (pin "G") (pinfunction "G_G") (pintype "passive"))
      (node (ref "R82") (pin "1") (pinfunction "1_1") (pintype "passive"))
    )
    (net (code "176") (name "Net-(Q119-PadD)") (class "Default")
      (node (ref "Q119") (pin "D") (pinfunction "D_D") (pintype "passive"))
      (node (ref "Q120") (pin "S") (pinfunction "S_S") (pintype "passive"))
    )
    (net (code "177") (name "Net-(Q121-PadD)") (class "Default")
      (node (ref "Q121") (pin "D") (pinfunction "D_D") (pintype "passive"))
      (node (ref "Q122") (pin "S") (pinfunction "S_S") (pintype "passive"))
    )
    (net (code "178") (name "Net-(Q122-PadG)") (class "Default")
      (node (ref "Q122") (pin "G") (pinfunction "G_G") (pintype "passive"))
      (node (ref "Q126") (pin "D") (pinfunction "D_D") (pintype "passive"))
      (node (ref "R84") (pin "1") (pinfunction "1_1") (pintype "passive"))
    )
    (net (code "179") (name "Net-(Q123-PadD)") (class "Default")
      (node (ref "Q123") (pin "D") (pinfunction "D_D") (pintype "passive"))
      (node (ref "Q124") (pin "S") (pinfunction "S_S") (pintype "passive"))
    )
    (net (code "180") (name "Net-(Q123-PadG)") (class "Default")
      (node (ref "Q123") (pin "G") (pinfunction "G_G") (pintype "passive"))
      (node (ref "Q128") (pin "D") (pinfunction "D_D") (pintype "passive"))
      (node (ref "R85") (pin "1") (pinfunction "1_1") (pintype "passive"))
    )
    (net (code "181") (name "Net-(Q125-PadD)") (class "Default")
      (node (ref "Q125") (pin "D") (pinfunction "D_D") (pintype "passive"))
      (node (ref "Q126") (pin "S") (pinfunction "S_S") (pintype "passive"))
    )
    (net (code "182") (name "Net-(Q127-PadD)") (class "Default")
      (node (ref "Q127") (pin "D") (pinfunction "D_D") (pintype "passive"))
      (node (ref "Q128") (pin "S") (pinfunction "S_S") (pintype "passive"))
    )
    (net (code "183") (name "Net-(Q129-PadD)") (class "Default")
      (node (ref "Q129") (pin "D") (pinfunction "D_D") (pintype "passive"))
      (node (ref "Q130") (pin "S") (pinfunction "S_S") (pintype "passive"))
    )
    (net (code "184") (name "Net-(Q130-PadD)") (class "Default")
      (node (ref "Q130") (pin "D") (pinfunction "D_D") (pintype "passive"))
      (node (ref "Q132") (pin "G") (pinfunction "G_G") (pintype "passive"))
      (node (ref "Q134") (pin "G") (pinfunction "G_G") (pintype "passive"))
      (node (ref "R89") (pin "1") (pinfunction "1_1") (pintype "passive"))
    )
    (net (code "185") (name "Net-(Q131-PadD)") (class "Default")
      (node (ref "Q131") (pin "D") (pinfunction "D_D") (pintype "passive"))
      (node (ref "Q132") (pin "S") (pinfunction "S_S") (pintype "passive"))
    )
    (net (code "186") (name "Net-(Q132-PadD)") (class "Default")
      (node (ref "Q132") (pin "D") (pinfunction "D_D") (pintype "passive"))
      (node (ref "Q135") (pin "G") (pinfunction "G_G") (pintype "passive"))
      (node (ref "R90") (pin "1") (pinfunction "1_1") (pintype "passive"))
    )
    (net (code "187") (name "Net-(Q133-PadD)") (class "Default")
      (node (ref "Q133") (pin "D") (pinfunction "D_D") (pintype "passive"))
      (node (ref "Q134") (pin "S") (pinfunction "S_S") (pintype "passive"))
    )
    (net (code "188") (name "Net-(Q133-PadG)") (class "Default")
      (node (ref "Q133") (pin "G") (pinfunction "G_G") (pintype "passive"))
      (node (ref "Q136") (pin "D") (pinfunction "D_D") (pintype "passive"))
      (node (ref "Q144") (pin "G") (pinfunction "G_G") (pintype "passive"))
      (node (ref "R92") (pin "1") (pinfunction "1_1") (pintype "passive"))
    )
    (net (code "189") (name "Net-(Q134-PadD)") (class "Default")
      (node (ref "Q134") (pin "D") (pinfunction "D_D") (pintype "passive"))
      (node (ref "Q136") (pin "G") (pinfunction "G_G") (pintype "passive"))
      (node (ref "Q142") (pin "G") (pinfunction "G_G") (pintype "passive"))
      (node (ref "R91") (pin "1") (pinfunction "1_1") (pintype "passive"))
    )
    (net (code "190") (name "Net-(Q135-PadD)") (class "Default")
      (node (ref "Q135") (pin "D") (pinfunction "D_D") (pintype "passive"))
      (node (ref "Q136") (pin "S") (pinfunction "S_S") (pintype "passive"))
    )
    (net (code "191") (name "Net-(Q137-PadD)") (class "Default")
      (node (ref "Q137") (pin "D") (pinfunction "D_D") (pintype "passive"))
      (node (ref "Q138") (pin "S") (pinfunction "S_S") (pintype "passive"))
    )
    (net (code "192") (name "Net-(Q138-PadG)") (class "Default")
      (node (ref "Q138") (pin "G") (pinfunction "G_G") (pintype "passive"))
      (node (ref "Q142") (pin "D") (pinfunction "D_D") (pintype "passive"))
      (node (ref "R93") (pin "1") (pinfunction "1_1") (pintype "passive"))
    )
    (net (code "193") (name "Net-(Q139-PadD)") (class "Default")
      (node (ref "Q139") (pin "D") (pinfunction "D_D") (pintype "passive"))
      (node (ref "Q140") (pin "S") (pinfunction "S_S") (pintype "passive"))
    )
    (net (code "194") (name "Net-(Q139-PadG)") (class "Default")
      (node (ref "Q139") (pin "G") (pinfunction "G_G") (pintype "passive"))
      (node (ref "Q144") (pin "D") (pinfunction "D_D") (pintype "passive"))
      (node (ref "R94") (pin "1") (pinfunction "1_1") (pintype "passive"))
    )
    (net (code "195") (name "Net-(Q141-PadD)") (class "Default")
      (node (ref "Q141") (pin "D") (pinfunction "D_D") (pintype "passive"))
      (node (ref "Q142") (pin "S") (pinfunction "S_S") (pintype "passive"))
    )
    (net (code "196") (name "Net-(Q143-PadD)") (class "Default")
      (node (ref "Q143") (pin "D") (pinfunction "D_D") (pintype "passive"))
      (node (ref "Q144") (pin "S") (pinfunction "S_S") (pintype "passive"))
    )
    (net (code "197") (name "Net-(Q145-PadD)") (class "Default")
      (node (ref "Q145") (pin "D") (pinfunction "D_D") (pintype "passive"))
      (node (ref "Q146") (pin "S") (pinfunction "S_S") (pintype "passive"))
    )
    (net (code "198") (name "Net-(Q146-PadD)") (class "Default")
      (node (ref "Q146") (pin "D") (pinfunction "D_D") (pintype "passive"))
      (node (ref "Q148") (pin "G") (pinfunction "G_G") (pintype "passive"))
      (node (ref "Q150") (pin "G") (pinfunction "G_G") (pintype "passive"))
      (node (ref "R98") (pin "1") (pinfunction "1_1") (pintype "passive"))
    )
    (net (code "199") (name "Net-(Q147-PadD)") (class "Default")
      (node (ref "Q147") (pin "D") (pinfunction "D_D") (pintype "passive"))
      (node (ref "Q148") (pin "S") (pinfunction "S_S") (pintype "passive"))
    )
    (net (code "200") (name "Net-(Q148-PadD)") (class "Default")
      (node (ref "Q148") (pin "D") (pinfunction "D_D") (pintype "passive"))
      (node (ref "Q151") (pin "G") (pinfunction "G_G") (pintype "passive"))
      (node (ref "R99") (pin "1") (pinfunction "1_1") (pintype "passive"))
    )
    (net (code "201") (name "Net-(Q149-PadD)") (class "Default")
      (node (ref "Q149") (pin "D") (pinfunction "D_D") (pintype "passive"))
      (node (ref "Q150") (pin "S") (pinfunction "S_S") (pintype "passive"))
    )
    (net (code "202") (name "Net-(Q149-PadG)") (class "Default")
      (node (ref "Q149") (pin "G") (pinfunction "G_G") (pintype "passive"))
      (node (ref "Q152") (pin "D") (pinfunction "D_D") (pintype "passive"))
      (node (ref "Q160") (pin "G") (pinfunction "G_G") (pintype "passive"))
      (node (ref "R101") (pin "1") (pinfunction "1_1") (pintype "passive"))
    )
    (net (code "203") (name "Net-(Q150-PadD)") (class "Default")
      (node (ref "Q150") (pin "D") (pinfunction "D_D") (pintype "passive"))
      (node (ref "Q152") (pin "G") (pinfunction "G_G") (pintype "passive"))
      (node (ref "Q158") (pin "G") (pinfunction "G_G") (pintype "passive"))
      (node (ref "R100") (pin "1") (pinfunction "1_1") (pintype "passive"))
    )
    (net (code "204") (name "Net-(Q151-PadD)") (class "Default")
      (node (ref "Q151") (pin "D") (pinfunction "D_D") (pintype "passive"))
      (node (ref "Q152") (pin "S") (pinfunction "S_S") (pintype "passive"))
    )
    (net (code "205") (name "Net-(Q153-PadD)") (class "Default")
      (node (ref "Q153") (pin "D") (pinfunction "D_D") (pintype "passive"))
      (node (ref "Q154") (pin "S") (pinfunction "S_S") (pintype "passive"))
    )
    (net (code "206") (name "Net-(Q154-PadG)") (class "Default")
      (node (ref "Q154") (pin "G") (pinfunction "G_G") (pintype "passive"))
      (node (ref "Q158") (pin "D") (pinfunction "D_D") (pintype "passive"))
      (node (ref "R102") (pin "1") (pinfunction "1_1") (pintype "passive"))
    )
    (net (code "207") (name "Net-(Q155-PadD)") (class "Default")
      (node (ref "Q155") (pin "D") (pinfunction "D_D") (pintype "passive"))
      (node (ref "Q156") (pin "S") (pinfunction "S_S") (pintype "passive"))
    )
    (net (code "208") (name "Net-(Q155-PadG)") (class "Default")
      (node (ref "Q155") (pin "G") (pinfunction "G_G") (pintype "passive"))
      (node (ref "Q160") (pin "D") (pinfunction "D_D") (pintype "passive"))
      (node (ref "R103") (pin "1") (pinfunction "1_1") (pintype "passive"))
    )
    (net (code "209") (name "Net-(Q157-PadD)") (class "Default")
      (node (ref "Q157") (pin "D") (pinfunction "D_D") (pintype "passive"))
      (node (ref "Q158") (pin "S") (pinfunction "S_S") (pintype "passive"))
    )
    (net (code "210") (name "Net-(Q159-PadD)") (class "Default")
      (node (ref "Q159") (pin "D") (pinfunction "D_D") (pintype "passive"))
      (node (ref "Q160") (pin "S") (pinfunction "S_S") (pintype "passive"))
    )
    (net (code "211") (name "Net-(Q161-PadD)") (class "Default")
      (node (ref "Q161") (pin "D") (pinfunction "D_D") (pintype "passive"))
      (node (ref "Q162") (pin "S") (pinfunction "S_S") (pintype "passive"))
    )
    (net (code "212") (name "Net-(Q162-PadD)") (class "Default")
      (node (ref "Q162") (pin "D") (pinfunction "D_D") (pintype "passive"))
      (node (ref "Q164") (pin "G") (pinfunction "G_G") (pintype "passive"))
      (node (ref "Q166") (pin "G") (pinfunction "G_G") (pintype "passive"))
      (node (ref "R107") (pin "1") (pinfunction "1_1") (pintype "passive"))
    )
    (net (code "213") (name "Net-(Q163-PadD)") (class "Default")
      (node (ref "Q163") (pin "D") (pinfunction "D_D") (pintype "passive"))
      (node (ref "Q164") (pin "S") (pinfunction "S_S") (pintype "passive"))
    )
    (net (code "214") (name "Net-(Q164-PadD)") (class "Default")
      (node (ref "Q164") (pin "D") (pinfunction "D_D") (pintype "passive"))
      (node (ref "Q167") (pin "G") (pinfunction "G_G") (pintype "passive"))
      (node (ref "R108") (pin "1") (pinfunction "1_1") (pintype "passive"))
    )
    (net (code "215") (name "Net-(Q165-PadD)") (class "Default")
      (node (ref "Q165") (pin "D") (pinfunction "D_D") (pintype "passive"))
      (node (ref "Q166") (pin "S") (pinfunction "S_S") (pintype "passive"))
    )
    (net (code "216") (name "Net-(Q165-PadG)") (class "Default")
      (node (ref "Q165") (pin "G") (pinfunction "G_G") (pintype "passive"))
      (node (ref "Q168") (pin "D") (pinfunction "D_D") (pintype "passive"))
      (node (ref "Q176") (pin "G") (pinfunction "G_G") (pintype "passive"))
      (node (ref "R110") (pin "1") (pinfunction "1_1") (pintype "passive"))
    )
    (net (code "217") (name "Net-(Q166-PadD)") (class "Default")
      (node (ref "Q166") (pin "D") (pinfunction "D_D") (pintype "passive"))
      (node (ref "Q168") (pin "G") (pinfunction "G_G") (pintype "passive"))
      (node (ref "Q174") (pin "G") (pinfunction "G_G") (pintype "passive"))
      (node (ref "R109") (pin "1") (pinfunction "1_1") (pintype "passive"))
    )
    (net (code "218") (name "Net-(Q167-PadD)") (class "Default")
      (node (ref "Q167") (pin "D") (pinfunction "D_D") (pintype "passive"))
      (node (ref "Q168") (pin "S") (pinfunction "S_S") (pintype "passive"))
    )
    (net (code "219") (name "Net-(Q169-PadD)") (class "Default")
      (node (ref "Q169") (pin "D") (pinfunction "D_D") (pintype "passive"))
      (node (ref "Q170") (pin "S") (pinfunction "S_S") (pintype "passive"))
    )
    (net (code "220") (name "Net-(Q170-PadG)") (class "Default")
      (node (ref "Q170") (pin "G") (pinfunction "G_G") (pintype "passive"))
      (node (ref "Q174") (pin "D") (pinfunction "D_D") (pintype "passive"))
      (node (ref "R111") (pin "1") (pinfunction "1_1") (pintype "passive"))
    )
    (net (code "221") (name "Net-(Q171-PadD)") (class "Default")
      (node (ref "Q171") (pin "D") (pinfunction "D_D") (pintype "passive"))
      (node (ref "Q172") (pin "S") (pinfunction "S_S") (pintype "passive"))
    )
    (net (code "222") (name "Net-(Q171-PadG)") (class "Default")
      (node (ref "Q171") (pin "G") (pinfunction "G_G") (pintype "passive"))
      (node (ref "Q176") (pin "D") (pinfunction "D_D") (pintype "passive"))
      (node (ref "R112") (pin "1") (pinfunction "1_1") (pintype "passive"))
    )
    (net (code "223") (name "Net-(Q173-PadD)") (class "Default")
      (node (ref "Q173") (pin "D") (pinfunction "D_D") (pintype "passive"))
      (node (ref "Q174") (pin "S") (pinfunction "S_S") (pintype "passive"))
    )
    (net (code "224") (name "Net-(Q175-PadD)") (class "Default")
      (node (ref "Q175") (pin "D") (pinfunction "D_D") (pintype "passive"))
      (node (ref "Q176") (pin "S") (pinfunction "S_S") (pintype "passive"))
    )
    (net (code "225") (name "Net-(Q177-PadD)") (class "Default")
      (node (ref "Q177") (pin "D") (pinfunction "D_D") (pintype "passive"))
      (node (ref "Q178") (pin "S") (pinfunction "S_S") (pintype "passive"))
    )
    (net (code "226") (name "Net-(Q178-PadD)") (class "Default")
      (node (ref "Q178") (pin "D") (pinfunction "D_D") (pintype "passive"))
      (node (ref "Q180") (pin "G") (pinfunction "G_G") (pintype "passive"))
      (node (ref "Q182") (pin "G") (pinfunction "G_G") (pintype "passive"))
      (node (ref "R138") (pin "1") (pinfunction "1_1") (pintype "passive"))
    )
    (net (code "227") (name "Net-(Q179-PadD)") (class "Default")
      (node (ref "Q179") (pin "D") (pinfunction "D_D") (pintype "passive"))
      (node (ref "Q180") (pin "S") (pinfunction "S_S") (pintype "passive"))
    )
    (net (code "228") (name "Net-(Q180-PadD)") (class "Default")
      (node (ref "Q180") (pin "D") (pinfunction "D_D") (pintype "passive"))
      (node (ref "Q183") (pin "G") (pinfunction "G_G") (pintype "passive"))
      (node (ref "R139") (pin "1") (pinfunction "1_1") (pintype "passive"))
    )
    (net (code "229") (name "Net-(Q181-PadD)") (class "Default")
      (node (ref "Q181") (pin "D") (pinfunction "D_D") (pintype "passive"))
      (node (ref "Q182") (pin "S") (pinfunction "S_S") (pintype "passive"))
    )
    (net (code "230") (name "Net-(Q181-PadG)") (class "Default")
      (node (ref "Q181") (pin "G") (pinfunction "G_G") (pintype "passive"))
      (node (ref "Q184") (pin "D") (pinfunction "D_D") (pintype "passive"))
      (node (ref "Q192") (pin "G") (pinfunction "G_G") (pintype "passive"))
      (node (ref "R141") (pin "1") (pinfunction "1_1") (pintype "passive"))
    )
    (net (code "231") (name "Net-(Q182-PadD)") (class "Default")
      (node (ref "Q182") (pin "D") (pinfunction "D_D") (pintype "passive"))
      (node (ref "Q184") (pin "G") (pinfunction "G_G") (pintype "passive"))
      (node (ref "Q190") (pin "G") (pinfunction "G_G") (pintype "passive"))
      (node (ref "R140") (pin "1") (pinfunction "1_1") (pintype "passive"))
    )
    (net (code "232") (name "Net-(Q183-PadD)") (class "Default")
      (node (ref "Q183") (pin "D") (pinfunction "D_D") (pintype "passive"))
      (node (ref "Q184") (pin "S") (pinfunction "S_S") (pintype "passive"))
    )
    (net (code "233") (name "Net-(Q185-PadD)") (class "Default")
      (node (ref "Q185") (pin "D") (pinfunction "D_D") (pintype "passive"))
      (node (ref "Q186") (pin "S") (pinfunction "S_S") (pintype "passive"))
    )
    (net (code "234") (name "Net-(Q186-PadG)") (class "Default")
      (node (ref "Q186") (pin "G") (pinfunction "G_G") (pintype "passive"))
      (node (ref "Q190") (pin "D") (pinfunction "D_D") (pintype "passive"))
      (node (ref "R142") (pin "1") (pinfunction "1_1") (pintype "passive"))
    )
    (net (code "235") (name "Net-(Q187-PadD)") (class "Default")
      (node (ref "Q187") (pin "D") (pinfunction "D_D") (pintype "passive"))
      (node (ref "Q188") (pin "S") (pinfunction "S_S") (pintype "passive"))
    )
    (net (code "236") (name "Net-(Q187-PadG)") (class "Default")
      (node (ref "Q187") (pin "G") (pinfunction "G_G") (pintype "passive"))
      (node (ref "Q192") (pin "D") (pinfunction "D_D") (pintype "passive"))
      (node (ref "R143") (pin "1") (pinfunction "1_1") (pintype "passive"))
    )
    (net (code "237") (name "Net-(Q189-PadD)") (class "Default")
      (node (ref "Q189") (pin "D") (pinfunction "D_D") (pintype "passive"))
      (node (ref "Q190") (pin "S") (pinfunction "S_S") (pintype "passive"))
    )
    (net (code "238") (name "Net-(Q191-PadD)") (class "Default")
      (node (ref "Q191") (pin "D") (pinfunction "D_D") (pintype "passive"))
      (node (ref "Q192") (pin "S") (pinfunction "S_S") (pintype "passive"))
    )
    (net (code "239") (name "Net-(Q193-PadD)") (class "Default")
      (node (ref "Q193") (pin "D") (pinfunction "D_D") (pintype "passive"))
      (node (ref "Q194") (pin "S") (pinfunction "S_S") (pintype "passive"))
    )
    (net (code "240") (name "Net-(Q194-PadD)") (class "Default")
      (node (ref "Q194") (pin "D") (pinfunction "D_D") (pintype "passive"))
      (node (ref "Q196") (pin "G") (pinfunction "G_G") (pintype "passive"))
      (node (ref "Q198") (pin "G") (pinfunction "G_G") (pintype "passive"))
      (node (ref "R147") (pin "1") (pinfunction "1_1") (pintype "passive"))
    )
    (net (code "241") (name "Net-(Q195-PadD)") (class "Default")
      (node (ref "Q195") (pin "D") (pinfunction "D_D") (pintype "passive"))
      (node (ref "Q196") (pin "S") (pinfunction "S_S") (pintype "passive"))
    )
    (net (code "242") (name "Net-(Q196-PadD)") (class "Default")
      (node (ref "Q196") (pin "D") (pinfunction "D_D") (pintype "passive"))
      (node (ref "Q199") (pin "G") (pinfunction "G_G") (pintype "passive"))
      (node (ref "R148") (pin "1") (pinfunction "1_1") (pintype "passive"))
    )
    (net (code "243") (name "Net-(Q197-PadD)") (class "Default")
      (node (ref "Q197") (pin "D") (pinfunction "D_D") (pintype "passive"))
      (node (ref "Q198") (pin "S") (pinfunction "S_S") (pintype "passive"))
    )
    (net (code "244") (name "Net-(Q197-PadG)") (class "Default")
      (node (ref "Q197") (pin "G") (pinfunction "G_G") (pintype "passive"))
      (node (ref "Q200") (pin "D") (pinfunction "D_D") (pintype "passive"))
      (node (ref "Q208") (pin "G") (pinfunction "G_G") (pintype "passive"))
      (node (ref "R150") (pin "1") (pinfunction "1_1") (pintype "passive"))
    )
    (net (code "245") (name "Net-(Q198-PadD)") (class "Default")
      (node (ref "Q198") (pin "D") (pinfunction "D_D") (pintype "passive"))
      (node (ref "Q200") (pin "G") (pinfunction "G_G") (pintype "passive"))
      (node (ref "Q206") (pin "G") (pinfunction "G_G") (pintype "passive"))
      (node (ref "R149") (pin "1") (pinfunction "1_1") (pintype "passive"))
    )
    (net (code "246") (name "Net-(Q199-PadD)") (class "Default")
      (node (ref "Q199") (pin "D") (pinfunction "D_D") (pintype "passive"))
      (node (ref "Q200") (pin "S") (pinfunction "S_S") (pintype "passive"))
    )
    (net (code "247") (name "Net-(Q201-PadD)") (class "Default")
      (node (ref "Q201") (pin "D") (pinfunction "D_D") (pintype "passive"))
      (node (ref "Q202") (pin "S") (pinfunction "S_S") (pintype "passive"))
    )
    (net (code "248") (name "Net-(Q202-PadG)") (class "Default")
      (node (ref "Q202") (pin "G") (pinfunction "G_G") (pintype "passive"))
      (node (ref "Q206") (pin "D") (pinfunction "D_D") (pintype "passive"))
      (node (ref "R151") (pin "1") (pinfunction "1_1") (pintype "passive"))
    )
    (net (code "249") (name "Net-(Q203-PadD)") (class "Default")
      (node (ref "Q203") (pin "D") (pinfunction "D_D") (pintype "passive"))
      (node (ref "Q204") (pin "S") (pinfunction "S_S") (pintype "passive"))
    )
    (net (code "250") (name "Net-(Q203-PadG)") (class "Default")
      (node (ref "Q203") (pin "G") (pinfunction "G_G") (pintype "passive"))
      (node (ref "Q208") (pin "D") (pinfunction "D_D") (pintype "passive"))
      (node (ref "R152") (pin "1") (pinfunction "1_1") (pintype "passive"))
    )
    (net (code "251") (name "Net-(Q205-PadD)") (class "Default")
      (node (ref "Q205") (pin "D") (pinfunction "D_D") (pintype "passive"))
      (node (ref "Q206") (pin "S") (pinfunction "S_S") (pintype "passive"))
    )
    (net (code "252") (name "Net-(Q207-PadD)") (class "Default")
      (node (ref "Q207") (pin "D") (pinfunction "D_D") (pintype "passive"))
      (node (ref "Q208") (pin "S") (pinfunction "S_S") (pintype "passive"))
    )
    (net (code "253") (name "Net-(Q209-PadD)") (class "Default")
      (node (ref "Q209") (pin "D") (pinfunction "D_D") (pintype "passive"))
      (node (ref "Q210") (pin "G") (pinfunction "G_G") (pintype "passive"))
      (node (ref "R113") (pin "1") (pinfunction "1_1") (pintype "passive"))
      (node (ref "R114") (pin "1") (pinfunction "1_1") (pintype "passive"))
    )
    (net (code "254") (name "Net-(Q209-PadG)") (class "Default")
      (node (ref "Q209") (pin "G") (pinfunction "G_G") (pintype "passive"))
      (node (ref "TP1") (pin "P$1") (pinfunction "P$1_P$1") (pintype "bidirectional"))
    )
    (net (code "255") (name "Net-(Q227-PadD)") (class "Default")
      (node (ref "Q227") (pin "D") (pinfunction "D_D") (pintype "passive"))
      (node (ref "Q228") (pin "G") (pinfunction "G_G") (pintype "passive"))
      (node (ref "R132") (pin "1") (pinfunction "1_1") (pintype "passive"))
      (node (ref "R133") (pin "1") (pinfunction "1_1") (pintype "passive"))
    )
    (net (code "256") (name "Net-(Q227-PadG)") (class "Default")
      (node (ref "Q227") (pin "G") (pinfunction "G_G") (pintype "passive"))
      (node (ref "TP2") (pin "P$1") (pinfunction "P$1_P$1") (pintype "bidirectional"))
    )
    (net (code "257") (name "Net-(Q229-PadD)") (class "Default")
      (node (ref "Q229") (pin "D") (pinfunction "D_D") (pintype "passive"))
      (node (ref "Q230") (pin "S") (pinfunction "S_S") (pintype "passive"))
    )
    (net (code "258") (name "Net-(Q230-PadD)") (class "Default")
      (node (ref "Q230") (pin "D") (pinfunction "D_D") (pintype "passive"))
      (node (ref "Q232") (pin "G") (pinfunction "G_G") (pintype "passive"))
      (node (ref "Q234") (pin "G") (pinfunction "G_G") (pintype "passive"))
      (node (ref "R156") (pin "1") (pinfunction "1_1") (pintype "passive"))
    )
    (net (code "259") (name "Net-(Q231-PadD)") (class "Default")
      (node (ref "Q231") (pin "D") (pinfunction "D_D") (pintype "passive"))
      (node (ref "Q232") (pin "S") (pinfunction "S_S") (pintype "passive"))
    )
    (net (code "260") (name "Net-(Q232-PadD)") (class "Default")
      (node (ref "Q232") (pin "D") (pinfunction "D_D") (pintype "passive"))
      (node (ref "Q235") (pin "G") (pinfunction "G_G") (pintype "passive"))
      (node (ref "R157") (pin "1") (pinfunction "1_1") (pintype "passive"))
    )
    (net (code "261") (name "Net-(Q233-PadD)") (class "Default")
      (node (ref "Q233") (pin "D") (pinfunction "D_D") (pintype "passive"))
      (node (ref "Q234") (pin "S") (pinfunction "S_S") (pintype "passive"))
    )
    (net (code "262") (name "Net-(Q233-PadG)") (class "Default")
      (node (ref "Q233") (pin "G") (pinfunction "G_G") (pintype "passive"))
      (node (ref "Q236") (pin "D") (pinfunction "D_D") (pintype "passive"))
      (node (ref "Q244") (pin "G") (pinfunction "G_G") (pintype "passive"))
      (node (ref "R159") (pin "1") (pinfunction "1_1") (pintype "passive"))
    )
    (net (code "263") (name "Net-(Q234-PadD)") (class "Default")
      (node (ref "Q234") (pin "D") (pinfunction "D_D") (pintype "passive"))
      (node (ref "Q236") (pin "G") (pinfunction "G_G") (pintype "passive"))
      (node (ref "Q242") (pin "G") (pinfunction "G_G") (pintype "passive"))
      (node (ref "R158") (pin "1") (pinfunction "1_1") (pintype "passive"))
    )
    (net (code "264") (name "Net-(Q235-PadD)") (class "Default")
      (node (ref "Q235") (pin "D") (pinfunction "D_D") (pintype "passive"))
      (node (ref "Q236") (pin "S") (pinfunction "S_S") (pintype "passive"))
    )
    (net (code "265") (name "Net-(Q237-PadD)") (class "Default")
      (node (ref "Q237") (pin "D") (pinfunction "D_D") (pintype "passive"))
      (node (ref "Q238") (pin "S") (pinfunction "S_S") (pintype "passive"))
    )
    (net (code "266") (name "Net-(Q238-PadG)") (class "Default")
      (node (ref "Q238") (pin "G") (pinfunction "G_G") (pintype "passive"))
      (node (ref "Q242") (pin "D") (pinfunction "D_D") (pintype "passive"))
      (node (ref "R160") (pin "1") (pinfunction "1_1") (pintype "passive"))
    )
    (net (code "267") (name "Net-(Q239-PadD)") (class "Default")
      (node (ref "Q239") (pin "D") (pinfunction "D_D") (pintype "passive"))
      (node (ref "Q240") (pin "S") (pinfunction "S_S") (pintype "passive"))
    )
    (net (code "268") (name "Net-(Q239-PadG)") (class "Default")
      (node (ref "Q239") (pin "G") (pinfunction "G_G") (pintype "passive"))
      (node (ref "Q244") (pin "D") (pinfunction "D_D") (pintype "passive"))
      (node (ref "R161") (pin "1") (pinfunction "1_1") (pintype "passive"))
    )
    (net (code "269") (name "Net-(Q241-PadD)") (class "Default")
      (node (ref "Q241") (pin "D") (pinfunction "D_D") (pintype "passive"))
      (node (ref "Q242") (pin "S") (pinfunction "S_S") (pintype "passive"))
    )
    (net (code "270") (name "Net-(Q243-PadD)") (class "Default")
      (node (ref "Q243") (pin "D") (pinfunction "D_D") (pintype "passive"))
      (node (ref "Q244") (pin "S") (pinfunction "S_S") (pintype "passive"))
    )
    (net (code "271") (name "Net-(Q245-PadD)") (class "Default")
      (node (ref "Q245") (pin "D") (pinfunction "D_D") (pintype "passive"))
      (node (ref "Q246") (pin "S") (pinfunction "S_S") (pintype "passive"))
    )
    (net (code "272") (name "Net-(Q246-PadD)") (class "Default")
      (node (ref "Q246") (pin "D") (pinfunction "D_D") (pintype "passive"))
      (node (ref "Q248") (pin "G") (pinfunction "G_G") (pintype "passive"))
      (node (ref "Q250") (pin "G") (pinfunction "G_G") (pintype "passive"))
      (node (ref "R165") (pin "1") (pinfunction "1_1") (pintype "passive"))
    )
    (net (code "273") (name "Net-(Q247-PadD)") (class "Default")
      (node (ref "Q247") (pin "D") (pinfunction "D_D") (pintype "passive"))
      (node (ref "Q248") (pin "S") (pinfunction "S_S") (pintype "passive"))
    )
    (net (code "274") (name "Net-(Q248-PadD)") (class "Default")
      (node (ref "Q248") (pin "D") (pinfunction "D_D") (pintype "passive"))
      (node (ref "Q251") (pin "G") (pinfunction "G_G") (pintype "passive"))
      (node (ref "R166") (pin "1") (pinfunction "1_1") (pintype "passive"))
    )
    (net (code "275") (name "Net-(Q249-PadD)") (class "Default")
      (node (ref "Q249") (pin "D") (pinfunction "D_D") (pintype "passive"))
      (node (ref "Q250") (pin "S") (pinfunction "S_S") (pintype "passive"))
    )
    (net (code "276") (name "Net-(Q249-PadG)") (class "Default")
      (node (ref "Q249") (pin "G") (pinfunction "G_G") (pintype "passive"))
      (node (ref "Q252") (pin "D") (pinfunction "D_D") (pintype "passive"))
      (node (ref "Q260") (pin "G") (pinfunction "G_G") (pintype "passive"))
      (node (ref "R168") (pin "1") (pinfunction "1_1") (pintype "passive"))
    )
    (net (code "277") (name "Net-(Q250-PadD)") (class "Default")
      (node (ref "Q250") (pin "D") (pinfunction "D_D") (pintype "passive"))
      (node (ref "Q252") (pin "G") (pinfunction "G_G") (pintype "passive"))
      (node (ref "Q258") (pin "G") (pinfunction "G_G") (pintype "passive"))
      (node (ref "R167") (pin "1") (pinfunction "1_1") (pintype "passive"))
    )
    (net (code "278") (name "Net-(Q251-PadD)") (class "Default")
      (node (ref "Q251") (pin "D") (pinfunction "D_D") (pintype "passive"))
      (node (ref "Q252") (pin "S") (pinfunction "S_S") (pintype "passive"))
    )
    (net (code "279") (name "Net-(Q253-PadD)") (class "Default")
      (node (ref "Q253") (pin "D") (pinfunction "D_D") (pintype "passive"))
      (node (ref "Q254") (pin "S") (pinfunction "S_S") (pintype "passive"))
    )
    (net (code "280") (name "Net-(Q254-PadG)") (class "Default")
      (node (ref "Q254") (pin "G") (pinfunction "G_G") (pintype "passive"))
      (node (ref "Q258") (pin "D") (pinfunction "D_D") (pintype "passive"))
      (node (ref "R169") (pin "1") (pinfunction "1_1") (pintype "passive"))
    )
    (net (code "281") (name "Net-(Q255-PadD)") (class "Default")
      (node (ref "Q255") (pin "D") (pinfunction "D_D") (pintype "passive"))
      (node (ref "Q256") (pin "S") (pinfunction "S_S") (pintype "passive"))
    )
    (net (code "282") (name "Net-(Q255-PadG)") (class "Default")
      (node (ref "Q255") (pin "G") (pinfunction "G_G") (pintype "passive"))
      (node (ref "Q260") (pin "D") (pinfunction "D_D") (pintype "passive"))
      (node (ref "R170") (pin "1") (pinfunction "1_1") (pintype "passive"))
    )
    (net (code "283") (name "Net-(Q257-PadD)") (class "Default")
      (node (ref "Q257") (pin "D") (pinfunction "D_D") (pintype "passive"))
      (node (ref "Q258") (pin "S") (pinfunction "S_S") (pintype "passive"))
    )
    (net (code "284") (name "Net-(Q259-PadD)") (class "Default")
      (node (ref "Q259") (pin "D") (pinfunction "D_D") (pintype "passive"))
      (node (ref "Q260") (pin "S") (pinfunction "S_S") (pintype "passive"))
    )
    (net (code "285") (name "Net-(Q261-PadD)") (class "Default")
      (node (ref "Q261") (pin "D") (pinfunction "D_D") (pintype "passive"))
      (node (ref "Q262") (pin "S") (pinfunction "S_S") (pintype "passive"))
    )
    (net (code "286") (name "Net-(Q262-PadD)") (class "Default")
      (node (ref "Q262") (pin "D") (pinfunction "D_D") (pintype "passive"))
      (node (ref "Q264") (pin "G") (pinfunction "G_G") (pintype "passive"))
      (node (ref "Q266") (pin "G") (pinfunction "G_G") (pintype "passive"))
      (node (ref "R174") (pin "1") (pinfunction "1_1") (pintype "passive"))
    )
    (net (code "287") (name "Net-(Q263-PadD)") (class "Default")
      (node (ref "Q263") (pin "D") (pinfunction "D_D") (pintype "passive"))
      (node (ref "Q264") (pin "S") (pinfunction "S_S") (pintype "passive"))
    )
    (net (code "288") (name "Net-(Q264-PadD)") (class "Default")
      (node (ref "Q264") (pin "D") (pinfunction "D_D") (pintype "passive"))
      (node (ref "Q267") (pin "G") (pinfunction "G_G") (pintype "passive"))
      (node (ref "R175") (pin "1") (pinfunction "1_1") (pintype "passive"))
    )
    (net (code "289") (name "Net-(Q265-PadD)") (class "Default")
      (node (ref "Q265") (pin "D") (pinfunction "D_D") (pintype "passive"))
      (node (ref "Q266") (pin "S") (pinfunction "S_S") (pintype "passive"))
    )
    (net (code "290") (name "Net-(Q265-PadG)") (class "Default")
      (node (ref "Q265") (pin "G") (pinfunction "G_G") (pintype "passive"))
      (node (ref "Q268") (pin "D") (pinfunction "D_D") (pintype "passive"))
      (node (ref "Q276") (pin "G") (pinfunction "G_G") (pintype "passive"))
      (node (ref "R177") (pin "1") (pinfunction "1_1") (pintype "passive"))
    )
    (net (code "291") (name "Net-(Q266-PadD)") (class "Default")
      (node (ref "Q266") (pin "D") (pinfunction "D_D") (pintype "passive"))
      (node (ref "Q268") (pin "G") (pinfunction "G_G") (pintype "passive"))
      (node (ref "Q274") (pin "G") (pinfunction "G_G") (pintype "passive"))
      (node (ref "R176") (pin "1") (pinfunction "1_1") (pintype "passive"))
    )
    (net (code "292") (name "Net-(Q267-PadD)") (class "Default")
      (node (ref "Q267") (pin "D") (pinfunction "D_D") (pintype "passive"))
      (node (ref "Q268") (pin "S") (pinfunction "S_S") (pintype "passive"))
    )
    (net (code "293") (name "Net-(Q269-PadD)") (class "Default")
      (node (ref "Q269") (pin "D") (pinfunction "D_D") (pintype "passive"))
      (node (ref "Q270") (pin "S") (pinfunction "S_S") (pintype "passive"))
    )
    (net (code "294") (name "Net-(Q270-PadG)") (class "Default")
      (node (ref "Q270") (pin "G") (pinfunction "G_G") (pintype "passive"))
      (node (ref "Q274") (pin "D") (pinfunction "D_D") (pintype "passive"))
      (node (ref "R178") (pin "1") (pinfunction "1_1") (pintype "passive"))
    )
    (net (code "295") (name "Net-(Q271-PadD)") (class "Default")
      (node (ref "Q271") (pin "D") (pinfunction "D_D") (pintype "passive"))
      (node (ref "Q272") (pin "S") (pinfunction "S_S") (pintype "passive"))
    )
    (net (code "296") (name "Net-(Q271-PadG)") (class "Default")
      (node (ref "Q271") (pin "G") (pinfunction "G_G") (pintype "passive"))
      (node (ref "Q276") (pin "D") (pinfunction "D_D") (pintype "passive"))
      (node (ref "R179") (pin "1") (pinfunction "1_1") (pintype "passive"))
    )
    (net (code "297") (name "Net-(Q273-PadD)") (class "Default")
      (node (ref "Q273") (pin "D") (pinfunction "D_D") (pintype "passive"))
      (node (ref "Q274") (pin "S") (pinfunction "S_S") (pintype "passive"))
    )
    (net (code "298") (name "Net-(Q275-PadD)") (class "Default")
      (node (ref "Q275") (pin "D") (pinfunction "D_D") (pintype "passive"))
      (node (ref "Q276") (pin "S") (pinfunction "S_S") (pintype "passive"))
    )
    (net (code "299") (name "Q0") (class "Default")
      (node (ref "J2") (pin "2") (pinfunction "2_2") (pintype "bidirectional"))
      (node (ref "J3") (pin "2") (pinfunction "2_2") (pintype "bidirectional"))
      (node (ref "Q11") (pin "D") (pinfunction "D_D") (pintype "passive"))
      (node (ref "Q13") (pin "G") (pinfunction "G_G") (pintype "passive"))
      (node (ref "R8") (pin "1") (pinfunction "1_1") (pintype "passive"))
    )
    (net (code "300") (name "Q0_N") (class "Default")
      (node (ref "Q10") (pin "G") (pinfunction "G_G") (pintype "passive"))
      (node (ref "Q13") (pin "D") (pinfunction "D_D") (pintype "passive"))
      (node (ref "R7") (pin "1") (pinfunction "1_1") (pintype "passive"))
      (node (ref "R9") (pin "1") (pinfunction "1_1") (pintype "passive"))
    )
    (net (code "301") (name "Q1") (class "Default")
      (node (ref "J2") (pin "3") (pinfunction "3_3") (pintype "bidirectional"))
      (node (ref "J3") (pin "3") (pinfunction "3_3") (pintype "bidirectional"))
      (node (ref "Q26") (pin "D") (pinfunction "D_D") (pintype "passive"))
      (node (ref "Q28") (pin "G") (pinfunction "G_G") (pintype "passive"))
      (node (ref "R33") (pin "1") (pinfunction "1_1") (pintype "passive"))
    )
    (net (code "302") (name "Q1_N") (class "Default")
      (node (ref "Q25") (pin "G") (pinfunction "G_G") (pintype "passive"))
      (node (ref "Q28") (pin "D") (pinfunction "D_D") (pintype "passive"))
      (node (ref "R32") (pin "1") (pinfunction "1_1") (pintype "passive"))
      (node (ref "R34") (pin "1") (pinfunction "1_1") (pintype "passive"))
    )
    (net (code "303") (name "Q2") (class "Default")
      (node (ref "J2") (pin "4") (pinfunction "4_4") (pintype "bidirectional"))
      (node (ref "J3") (pin "4") (pinfunction "4_4") (pintype "bidirectional"))
      (node (ref "Q42") (pin "D") (pinfunction "D_D") (pintype "passive"))
      (node (ref "Q44") (pin "G") (pinfunction "G_G") (pintype "passive"))
      (node (ref "R42") (pin "1") (pinfunction "1_1") (pintype "passive"))
    )
    (net (code "304") (name "Q2_N") (class "Default")
      (node (ref "Q41") (pin "G") (pinfunction "G_G") (pintype "passive"))
      (node (ref "Q44") (pin "D") (pinfunction "D_D") (pintype "passive"))
      (node (ref "R41") (pin "1") (pinfunction "1_1") (pintype "passive"))
      (node (ref "R43") (pin "1") (pinfunction "1_1") (pintype "passive"))
    )
    (net (code "305") (name "Q3") (class "Default")
      (node (ref "J2") (pin "5") (pinfunction "5_5") (pintype "bidirectional"))
      (node (ref "J3") (pin "5") (pinfunction "5_5") (pintype "bidirectional"))
      (node (ref "Q58") (pin "D") (pinfunction "D_D") (pintype "passive"))
      (node (ref "Q60") (pin "G") (pinfunction "G_G") (pintype "passive"))
      (node (ref "R51") (pin "1") (pinfunction "1_1") (pintype "passive"))
    )
    (net (code "306") (name "Q3_N") (class "Default")
      (node (ref "Q57") (pin "G") (pinfunction "G_G") (pintype "passive"))
      (node (ref "Q60") (pin "D") (pinfunction "D_D") (pintype "passive"))
      (node (ref "R50") (pin "1") (pinfunction "1_1") (pintype "passive"))
      (node (ref "R52") (pin "1") (pinfunction "1_1") (pintype "passive"))
    )
    (net (code "307") (name "Q4") (class "Default")
      (node (ref "J2") (pin "6") (pinfunction "6_6") (pintype "bidirectional"))
      (node (ref "J3") (pin "6") (pinfunction "6_6") (pintype "bidirectional"))
      (node (ref "Q74") (pin "D") (pinfunction "D_D") (pintype "passive"))
      (node (ref "Q76") (pin "G") (pinfunction "G_G") (pintype "passive"))
      (node (ref "R60") (pin "1") (pinfunction "1_1") (pintype "passive"))
    )
    (net (code "308") (name "Q4_N") (class "Default")
      (node (ref "Q73") (pin "G") (pinfunction "G_G") (pintype "passive"))
      (node (ref "Q76") (pin "D") (pinfunction "D_D") (pintype "passive"))
      (node (ref "R59") (pin "1") (pinfunction "1_1") (pintype "passive"))
      (node (ref "R61") (pin "1") (pinfunction "1_1") (pintype "passive"))
    )
    (net (code "309") (name "Q5") (class "Default")
      (node (ref "J2") (pin "7") (pinfunction "7_7") (pintype "bidirectional"))
      (node (ref "J3") (pin "7") (pinfunction "7_7") (pintype "bidirectional"))
      (node (ref "Q90") (pin "D") (pinfunction "D_D") (pintype "passive"))
      (node (ref "Q92") (pin "G") (pinfunction "G_G") (pintype "passive"))
      (node (ref "R69") (pin "1") (pinfunction "1_1") (pintype "passive"))
    )
    (net (code "310") (name "Q5_N") (class "Default")
      (node (ref "Q89") (pin "G") (pinfunction "G_G") (pintype "passive"))
      (node (ref "Q92") (pin "D") (pinfunction "D_D") (pintype "passive"))
      (node (ref "R68") (pin "1") (pinfunction "1_1") (pintype "passive"))
      (node (ref "R70") (pin "1") (pinfunction "1_1") (pintype "passive"))
    )
    (net (code "311") (name "Q6") (class "Default")
      (node (ref "J2") (pin "8") (pinfunction "8_8") (pintype "bidirectional"))
      (node (ref "J3") (pin "8") (pinfunction "8_8") (pintype "bidirectional"))
      (node (ref "Q106") (pin "D") (pinfunction "D_D") (pintype "passive"))
      (node (ref "Q108") (pin "G") (pinfunction "G_G") (pintype "passive"))
      (node (ref "R78") (pin "1") (pinfunction "1_1") (pintype "passive"))
    )
    (net (code "312") (name "Q6_N") (class "Default")
      (node (ref "Q105") (pin "G") (pinfunction "G_G") (pintype "passive"))
      (node (ref "Q108") (pin "D") (pinfunction "D_D") (pintype "passive"))
      (node (ref "R77") (pin "1") (pinfunction "1_1") (pintype "passive"))
      (node (ref "R79") (pin "1") (pinfunction "1_1") (pintype "passive"))
    )
    (net (code "313") (name "Q7") (class "Default")
      (node (ref "J2") (pin "9") (pinfunction "9_9") (pintype "bidirectional"))
      (node (ref "J3") (pin "9") (pinfunction "9_9") (pintype "bidirectional"))
      (node (ref "Q122") (pin "D") (pinfunction "D_D") (pintype "passive"))
      (node (ref "Q124") (pin "G") (pinfunction "G_G") (pintype "passive"))
      (node (ref "R87") (pin "1") (pinfunction "1_1") (pintype "passive"))
    )
    (net (code "314") (name "Q7_N") (class "Default")
      (node (ref "Q121") (pin "G") (pinfunction "G_G") (pintype "passive"))
      (node (ref "Q124") (pin "D") (pinfunction "D_D") (pintype "passive"))
      (node (ref "R86") (pin "1") (pinfunction "1_1") (pintype "passive"))
      (node (ref "R88") (pin "1") (pinfunction "1_1") (pintype "passive"))
    )
    (net (code "315") (name "Q8") (class "Default")
      (node (ref "J2") (pin "12") (pinfunction "12_12") (pintype "bidirectional"))
      (node (ref "J3") (pin "11") (pinfunction "11_11") (pintype "bidirectional"))
      (node (ref "Q138") (pin "D") (pinfunction "D_D") (pintype "passive"))
      (node (ref "Q140") (pin "G") (pinfunction "G_G") (pintype "passive"))
      (node (ref "R96") (pin "1") (pinfunction "1_1") (pintype "passive"))
    )
    (net (code "316") (name "Q8_N") (class "Default")
      (node (ref "Q137") (pin "G") (pinfunction "G_G") (pintype "passive"))
      (node (ref "Q140") (pin "D") (pinfunction "D_D") (pintype "passive"))
      (node (ref "R95") (pin "1") (pinfunction "1_1") (pintype "passive"))
      (node (ref "R97") (pin "1") (pinfunction "1_1") (pintype "passive"))
    )
    (net (code "317") (name "Q9") (class "Default")
      (node (ref "J2") (pin "13") (pinfunction "13_13") (pintype "bidirectional"))
      (node (ref "J3") (pin "12") (pinfunction "12_12") (pintype "bidirectional"))
      (node (ref "Q154") (pin "D") (pinfunction "D_D") (pintype "passive"))
      (node (ref "Q156") (pin "G") (pinfunction "G_G") (pintype "passive"))
      (node (ref "R105") (pin "1") (pinfunction "1_1") (pintype "passive"))
    )
    (net (code "318") (name "Q9_N") (class "Default")
      (node (ref "Q153") (pin "G") (pinfunction "G_G") (pintype "passive"))
      (node (ref "Q156") (pin "D") (pinfunction "D_D") (pintype "passive"))
      (node (ref "R104") (pin "1") (pinfunction "1_1") (pintype "passive"))
      (node (ref "R106") (pin "1") (pinfunction "1_1") (pintype "passive"))
    )
    (net (code "319") (name "Q10") (class "Default")
      (node (ref "J2") (pin "14") (pinfunction "14_14") (pintype "bidirectional"))
      (node (ref "J3") (pin "13") (pinfunction "13_13") (pintype "bidirectional"))
      (node (ref "Q170") (pin "D") (pinfunction "D_D") (pintype "passive"))
      (node (ref "Q172") (pin "G") (pinfunction "G_G") (pintype "passive"))
      (node (ref "R136") (pin "1") (pinfunction "1_1") (pintype "passive"))
    )
    (net (code "320") (name "Q10_N") (class "Default")
      (node (ref "Q169") (pin "G") (pinfunction "G_G") (pintype "passive"))
      (node (ref "Q172") (pin "D") (pinfunction "D_D") (pintype "passive"))
      (node (ref "R135") (pin "1") (pinfunction "1_1") (pintype "passive"))
      (node (ref "R137") (pin "1") (pinfunction "1_1") (pintype "passive"))
    )
    (net (code "321") (name "Q11") (class "Default")
      (node (ref "J2") (pin "15") (pinfunction "15_15") (pintype "bidirectional"))
      (node (ref "J3") (pin "14") (pinfunction "14_14") (pintype "bidirectional"))
      (node (ref "Q186") (pin "D") (pinfunction "D_D") (pintype "passive"))
      (node (ref "Q188") (pin "G") (pinfunction "G_G") (pintype "passive"))
      (node (ref "R145") (pin "1") (pinfunction "1_1") (pintype "passive"))
    )
    (net (code "322") (name "Q11_N") (class "Default")
      (node (ref "Q185") (pin "G") (pinfunction "G_G") (pintype "passive"))
      (node (ref "Q188") (pin "D") (pinfunction "D_D") (pintype "passive"))
      (node (ref "R144") (pin "1") (pinfunction "1_1") (pintype "passive"))
      (node (ref "R146") (pin "1") (pinfunction "1_1") (pintype "passive"))
    )
    (net (code "323") (name "Q12") (class "Default")
      (node (ref "J2") (pin "16") (pinfunction "16_16") (pintype "bidirectional"))
      (node (ref "J3") (pin "15") (pinfunction "15_15") (pintype "bidirectional"))
      (node (ref "Q202") (pin "D") (pinfunction "D_D") (pintype "passive"))
      (node (ref "Q204") (pin "G") (pinfunction "G_G") (pintype "passive"))
      (node (ref "R154") (pin "1") (pinfunction "1_1") (pintype "passive"))
    )
    (net (code "324") (name "Q12_N") (class "Default")
      (node (ref "Q201") (pin "G") (pinfunction "G_G") (pintype "passive"))
      (node (ref "Q204") (pin "D") (pinfunction "D_D") (pintype "passive"))
      (node (ref "R153") (pin "1") (pinfunction "1_1") (pintype "passive"))
      (node (ref "R155") (pin "1") (pinfunction "1_1") (pintype "passive"))
    )
    (net (code "325") (name "Q13") (class "Default")
      (node (ref "J2") (pin "17") (pinfunction "17_17") (pintype "bidirectional"))
      (node (ref "J3") (pin "16") (pinfunction "16_16") (pintype "bidirectional"))
      (node (ref "Q238") (pin "D") (pinfunction "D_D") (pintype "passive"))
      (node (ref "Q240") (pin "G") (pinfunction "G_G") (pintype "passive"))
      (node (ref "R163") (pin "1") (pinfunction "1_1") (pintype "passive"))
    )
    (net (code "326") (name "Q13_N") (class "Default")
      (node (ref "Q237") (pin "G") (pinfunction "G_G") (pintype "passive"))
      (node (ref "Q240") (pin "D") (pinfunction "D_D") (pintype "passive"))
      (node (ref "R162") (pin "1") (pinfunction "1_1") (pintype "passive"))
      (node (ref "R164") (pin "1") (pinfunction "1_1") (pintype "passive"))
    )
    (net (code "327") (name "Q14") (class "Default")
      (node (ref "J2") (pin "18") (pinfunction "18_18") (pintype "bidirectional"))
      (node (ref "J3") (pin "17") (pinfunction "17_17") (pintype "bidirectional"))
      (node (ref "Q254") (pin "D") (pinfunction "D_D") (pintype "passive"))
      (node (ref "Q256") (pin "G") (pinfunction "G_G") (pintype "passive"))
      (node (ref "R172") (pin "1") (pinfunction "1_1") (pintype "passive"))
    )
    (net (code "328") (name "Q14_N") (class "Default")
      (node (ref "Q253") (pin "G") (pinfunction "G_G") (pintype "passive"))
      (node (ref "Q256") (pin "D") (pinfunction "D_D") (pintype "passive"))
      (node (ref "R171") (pin "1") (pinfunction "1_1") (pintype "passive"))
      (node (ref "R173") (pin "1") (pinfunction "1_1") (pintype "passive"))
    )
    (net (code "329") (name "Q15") (class "Default")
      (node (ref "J2") (pin "19") (pinfunction "19_19") (pintype "bidirectional"))
      (node (ref "J3") (pin "18") (pinfunction "18_18") (pintype "bidirectional"))
      (node (ref "Q270") (pin "D") (pinfunction "D_D") (pintype "passive"))
      (node (ref "Q272") (pin "G") (pinfunction "G_G") (pintype "passive"))
      (node (ref "R181") (pin "1") (pinfunction "1_1") (pintype "passive"))
    )
    (net (code "330") (name "Q15_N") (class "Default")
      (node (ref "Q269") (pin "G") (pinfunction "G_G") (pintype "passive"))
      (node (ref "Q272") (pin "D") (pinfunction "D_D") (pintype "passive"))
      (node (ref "R180") (pin "1") (pinfunction "1_1") (pintype "passive"))
      (node (ref "R182") (pin "1") (pinfunction "1_1") (pintype "passive"))
    )
    (net (code "331") (name "unconnected-(J3-Pad20)") (class "Default")
      (node (ref "J3") (pin "20") (pinfunction "20_20") (pintype "bidirectional"))
    )
    (net (code "332") (name "unconnected-(J3-Pad21)") (class "Default")
      (node (ref "J3") (pin "21") (pinfunction "21_21") (pintype "bidirectional"))
    )
    (net (code "333") (name "unconnected-(J3-Pad22)") (class "Default")
      (node (ref "J3") (pin "22") (pinfunction "22_22") (pintype "bidirectional"))
    )
    (net (code "334") (name "unconnected-(J3-Pad23)") (class "Default")
      (node (ref "J3") (pin "23") (pinfunction "23_23") (pintype "bidirectional"))
    )
    (net (code "335") (name "unconnected-(J3-Pad24)") (class "Default")
      (node (ref "J3") (pin "24") (pinfunction "24_24") (pintype "bidirectional"))
    )
    (net (code "336") (name "unconnected-(J3-Pad25)") (class "Default")
      (node (ref "J3") (pin "25") (pinfunction "25_25") (pintype "bidirectional"))
    )
    (net (code "337") (name "unconnected-(J3-Pad26)") (class "Default")
      (node (ref "J3") (pin "26") (pinfunction "26_26") (pintype "bidirectional"))
    )
    (net (code "338") (name "unconnected-(J3-Pad27)") (class "Default")
      (node (ref "J3") (pin "27") (pinfunction "27_27") (pintype "bidirectional"))
    )
    (net (code "339") (name "unconnected-(J3-Pad29)") (class "Default")
      (node (ref "J3") (pin "29") (pinfunction "29_29") (pintype "bidirectional"))
    )
    (net (code "340") (name "unconnected-(J3-Pad30)") (class "Default")
      (node (ref "J3") (pin "30") (pinfunction "30_30") (pintype "bidirectional"))
    )
  )
)
